# ReA4091_Rev4_2023-04-22_SCH.net
KiCad netlist of a schematic drawn in EasyEDA
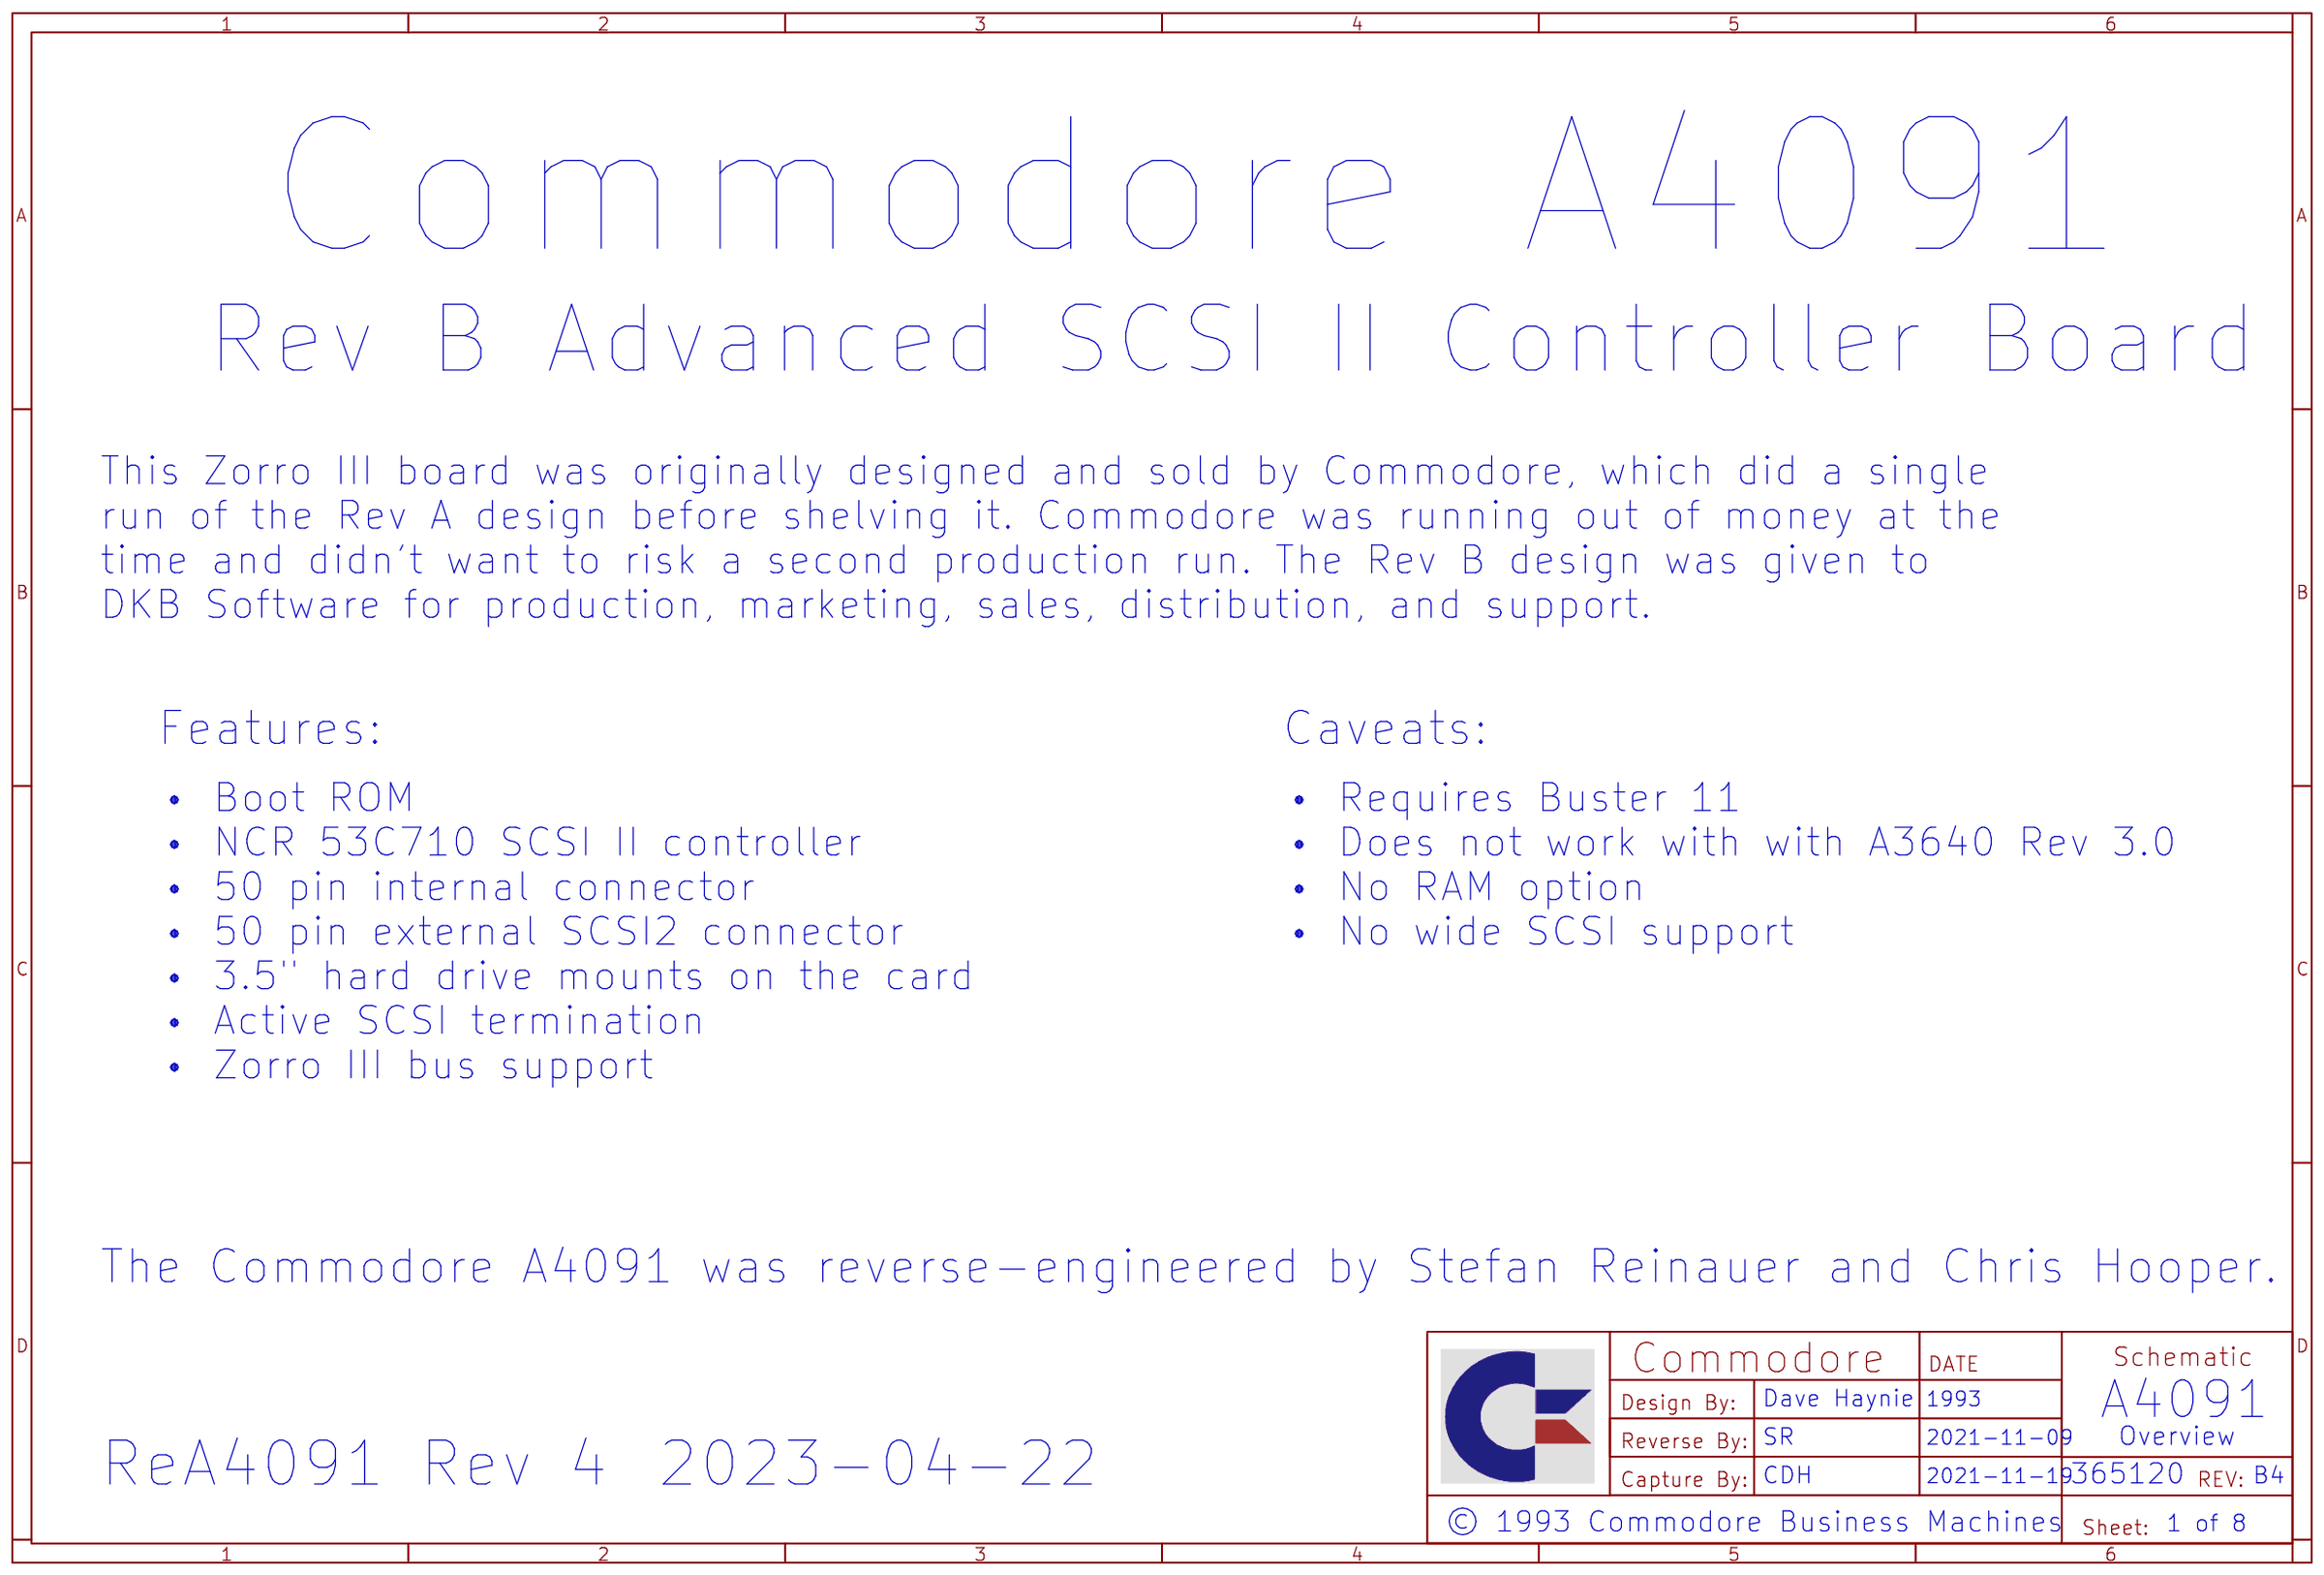
[diagram p0: Overview]
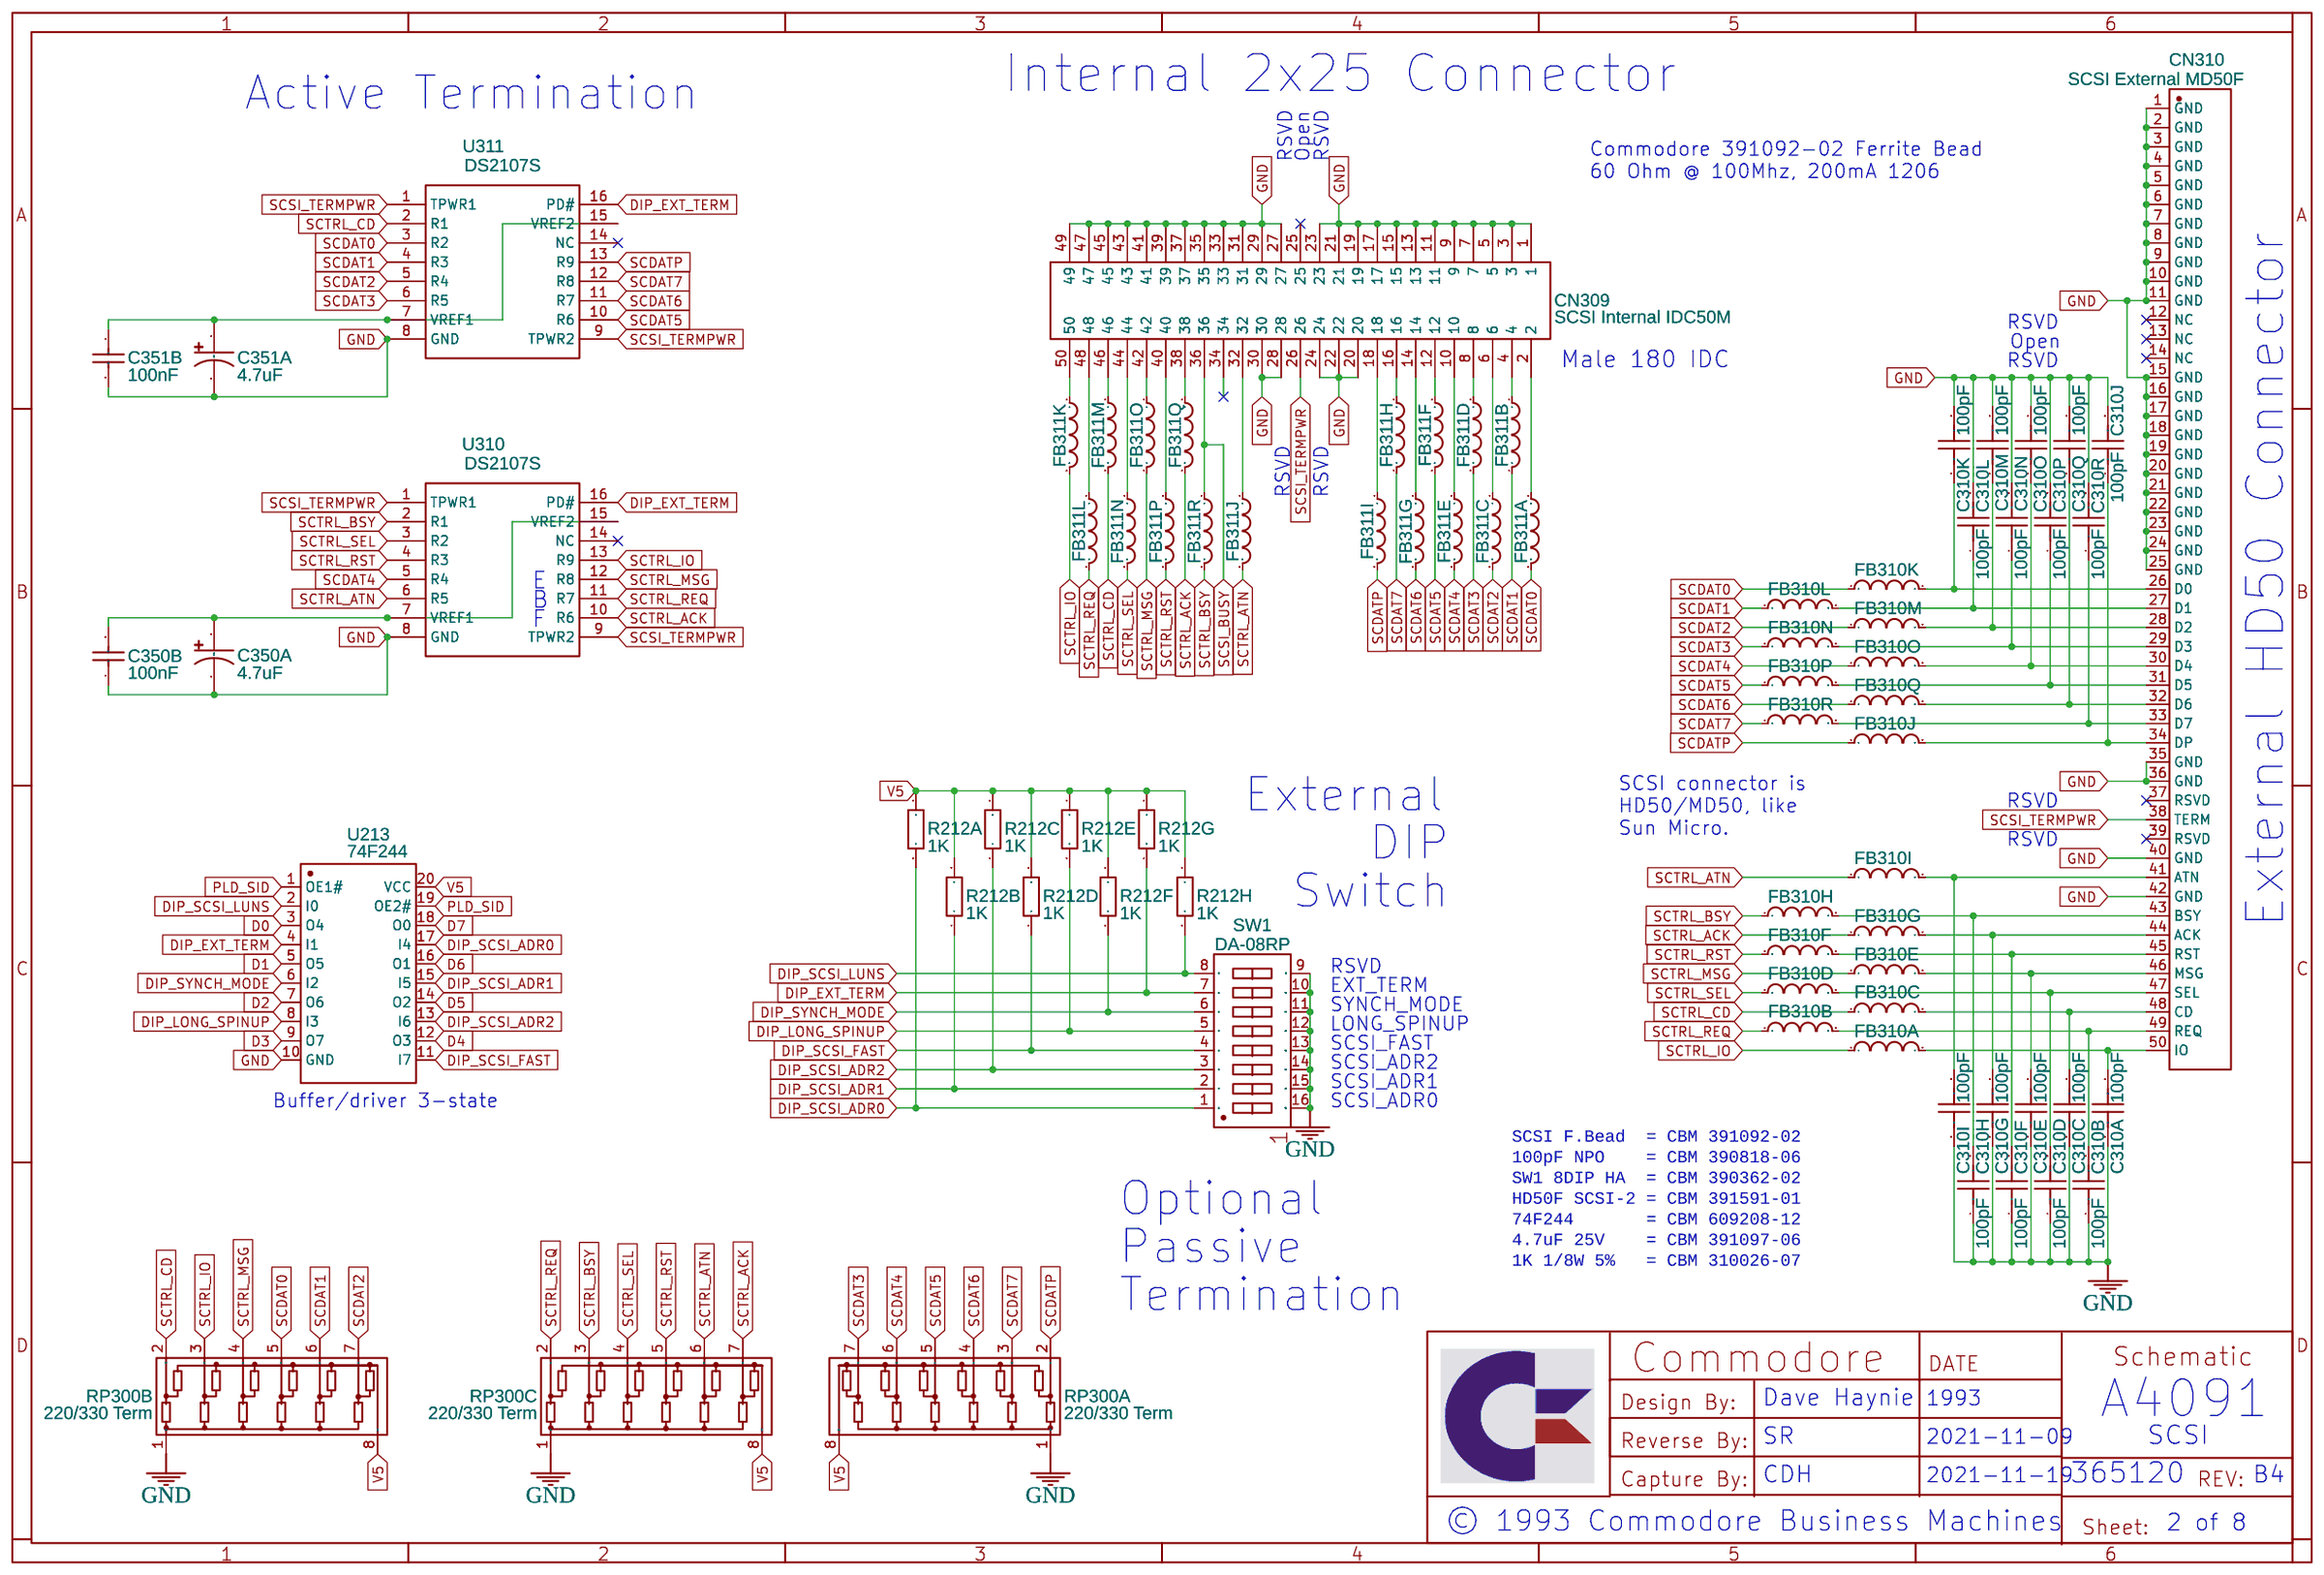
[diagram p1: SCSI]
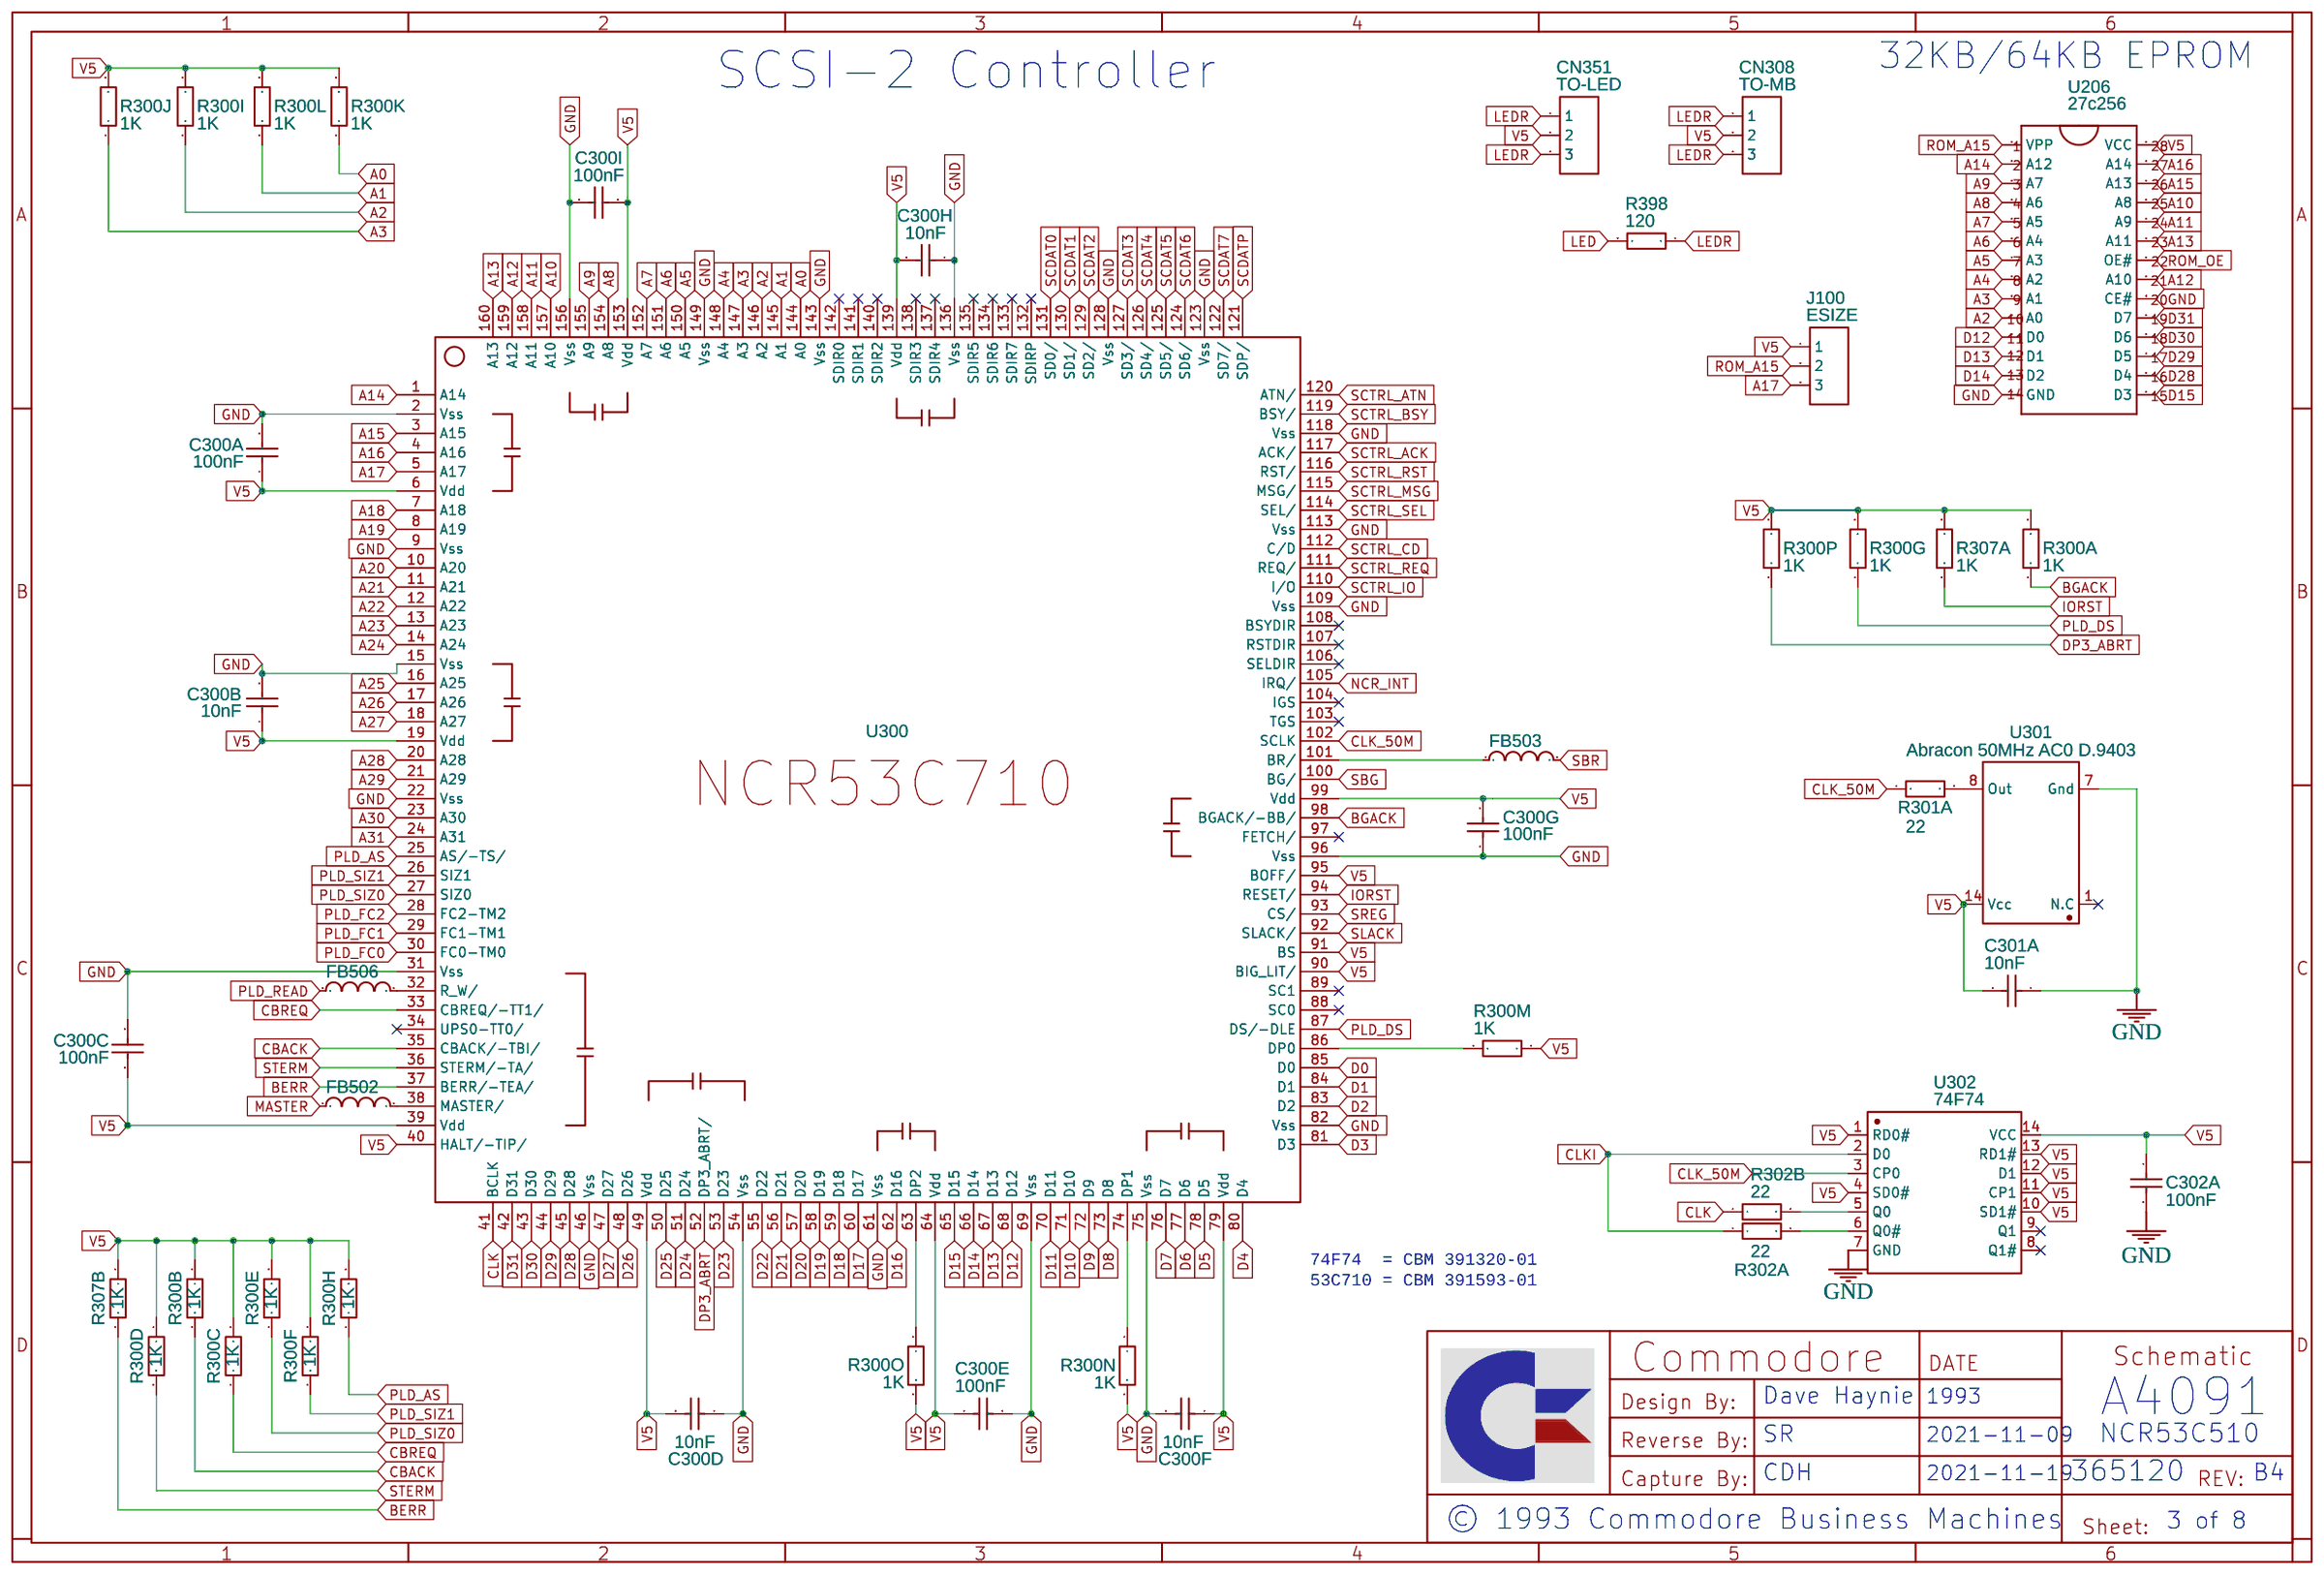
[diagram p2: NCR53C710]
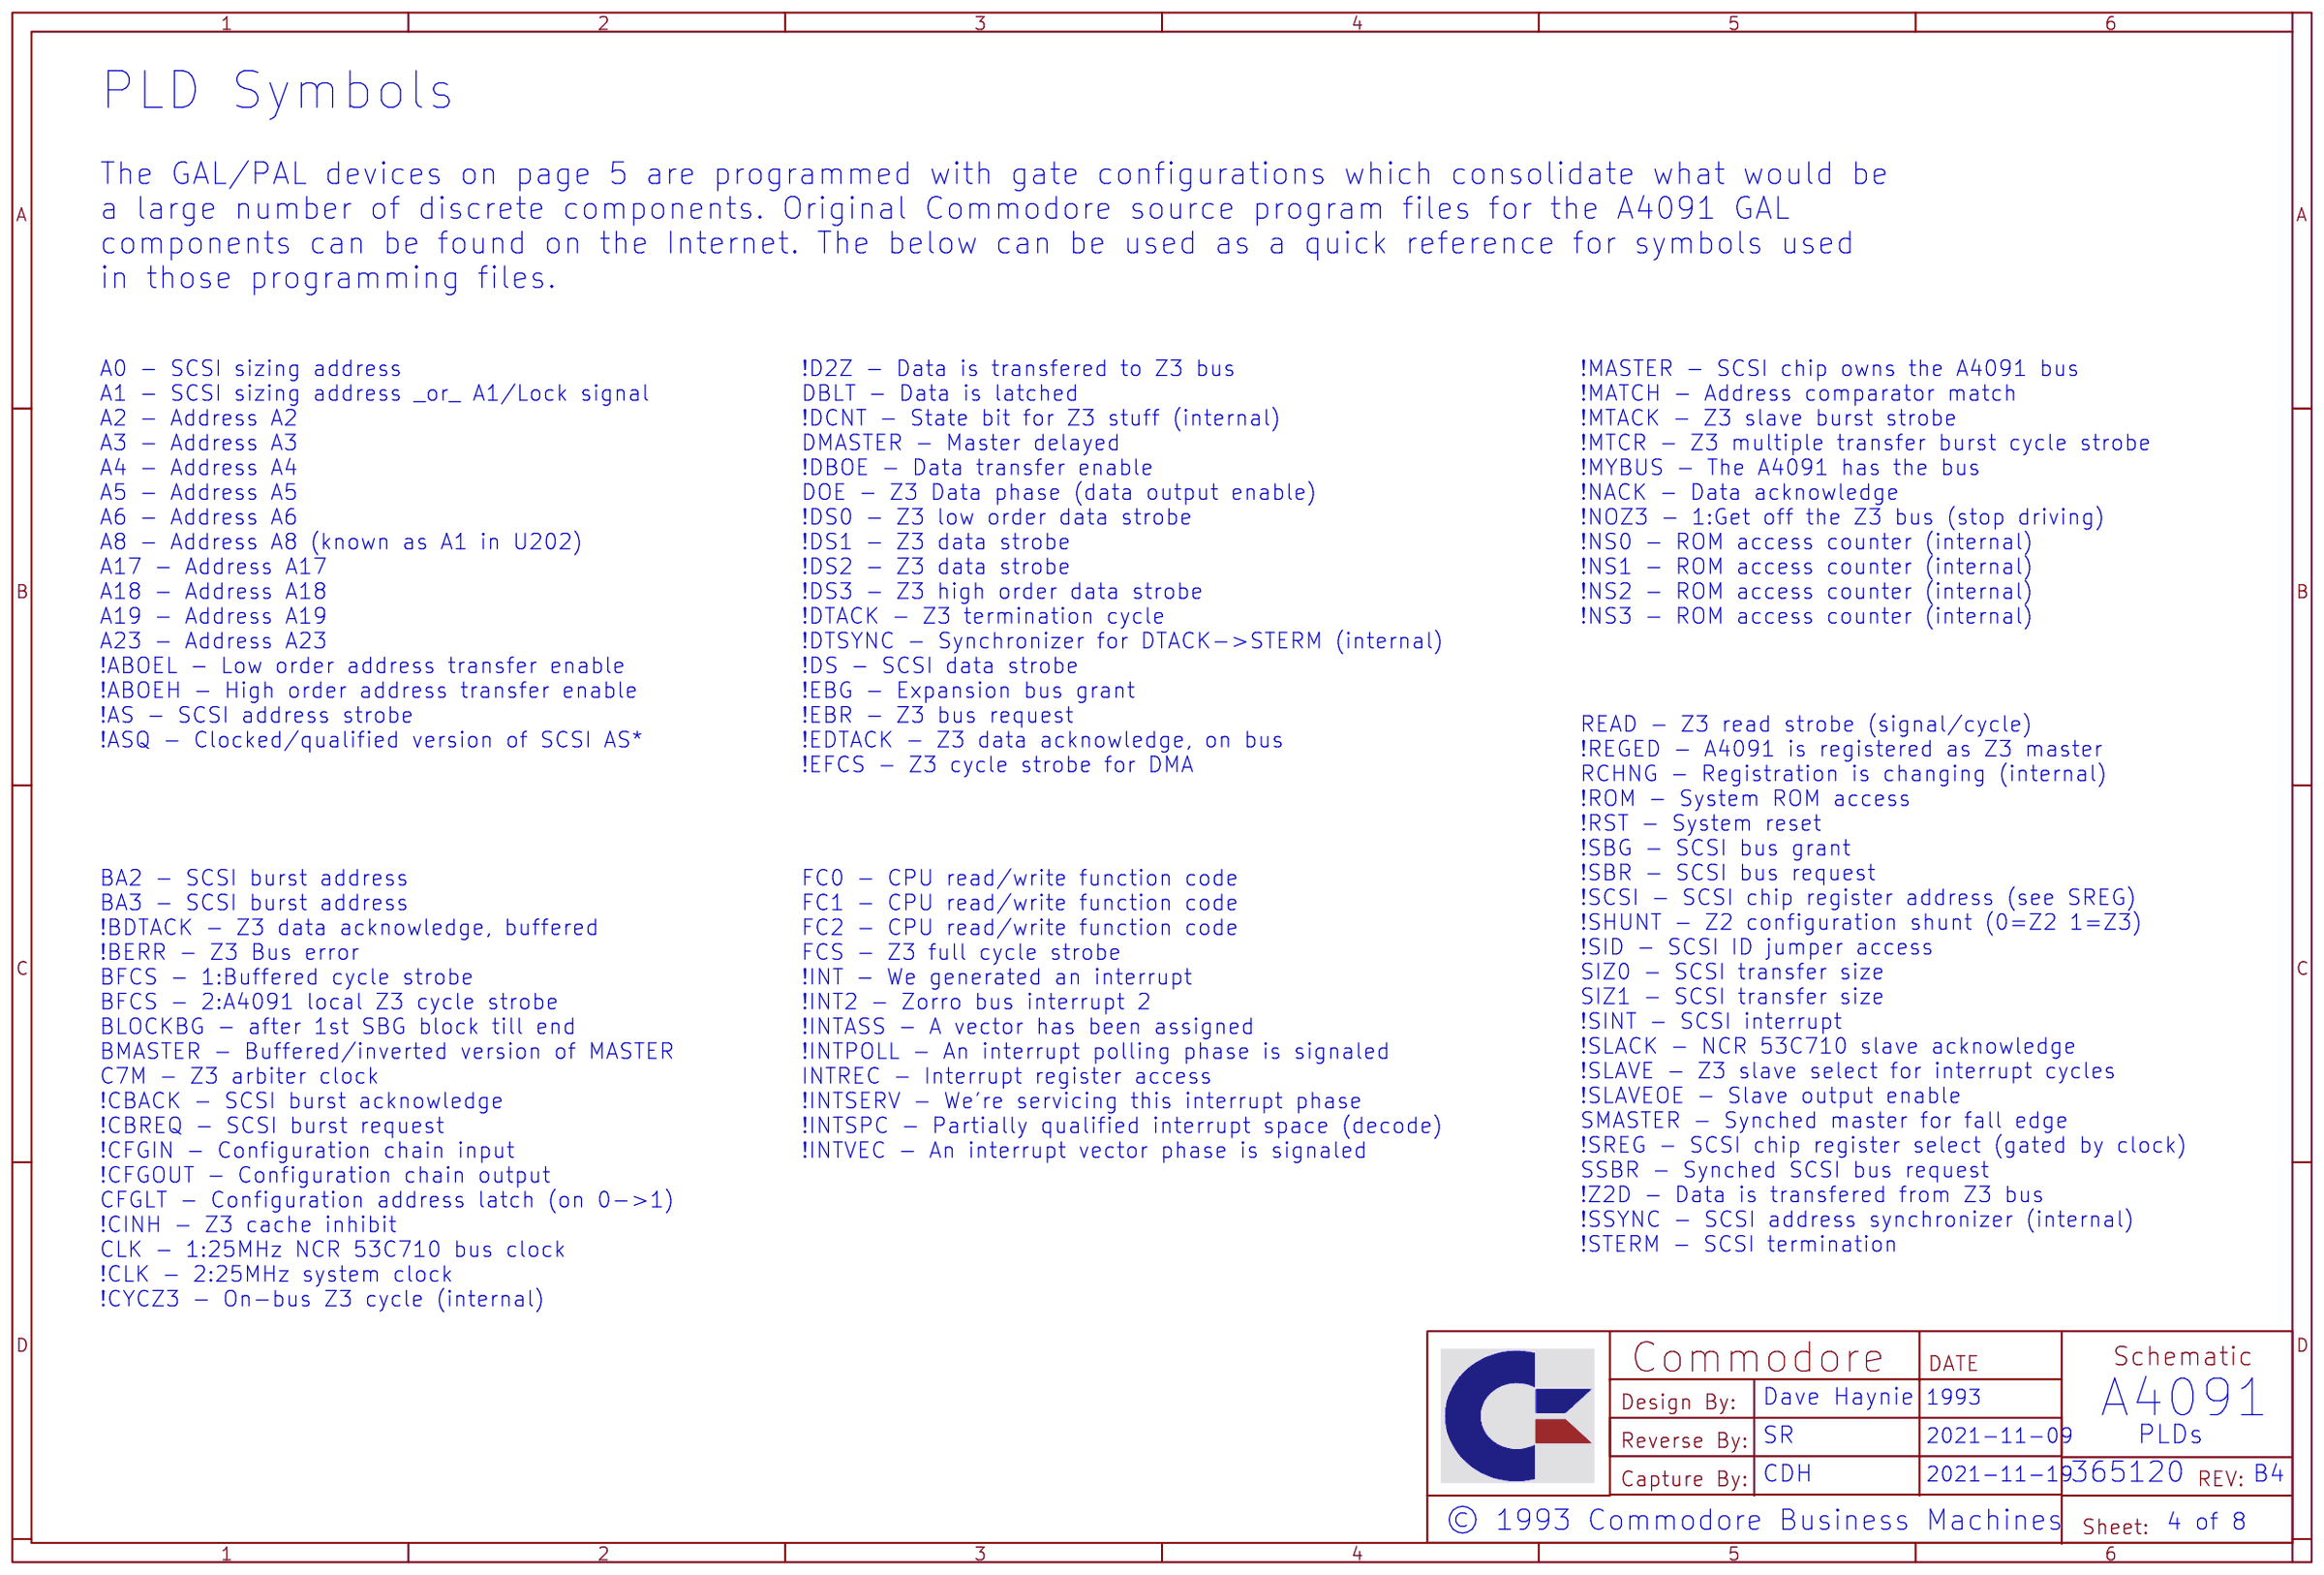
[diagram p3: PLD Symbols]
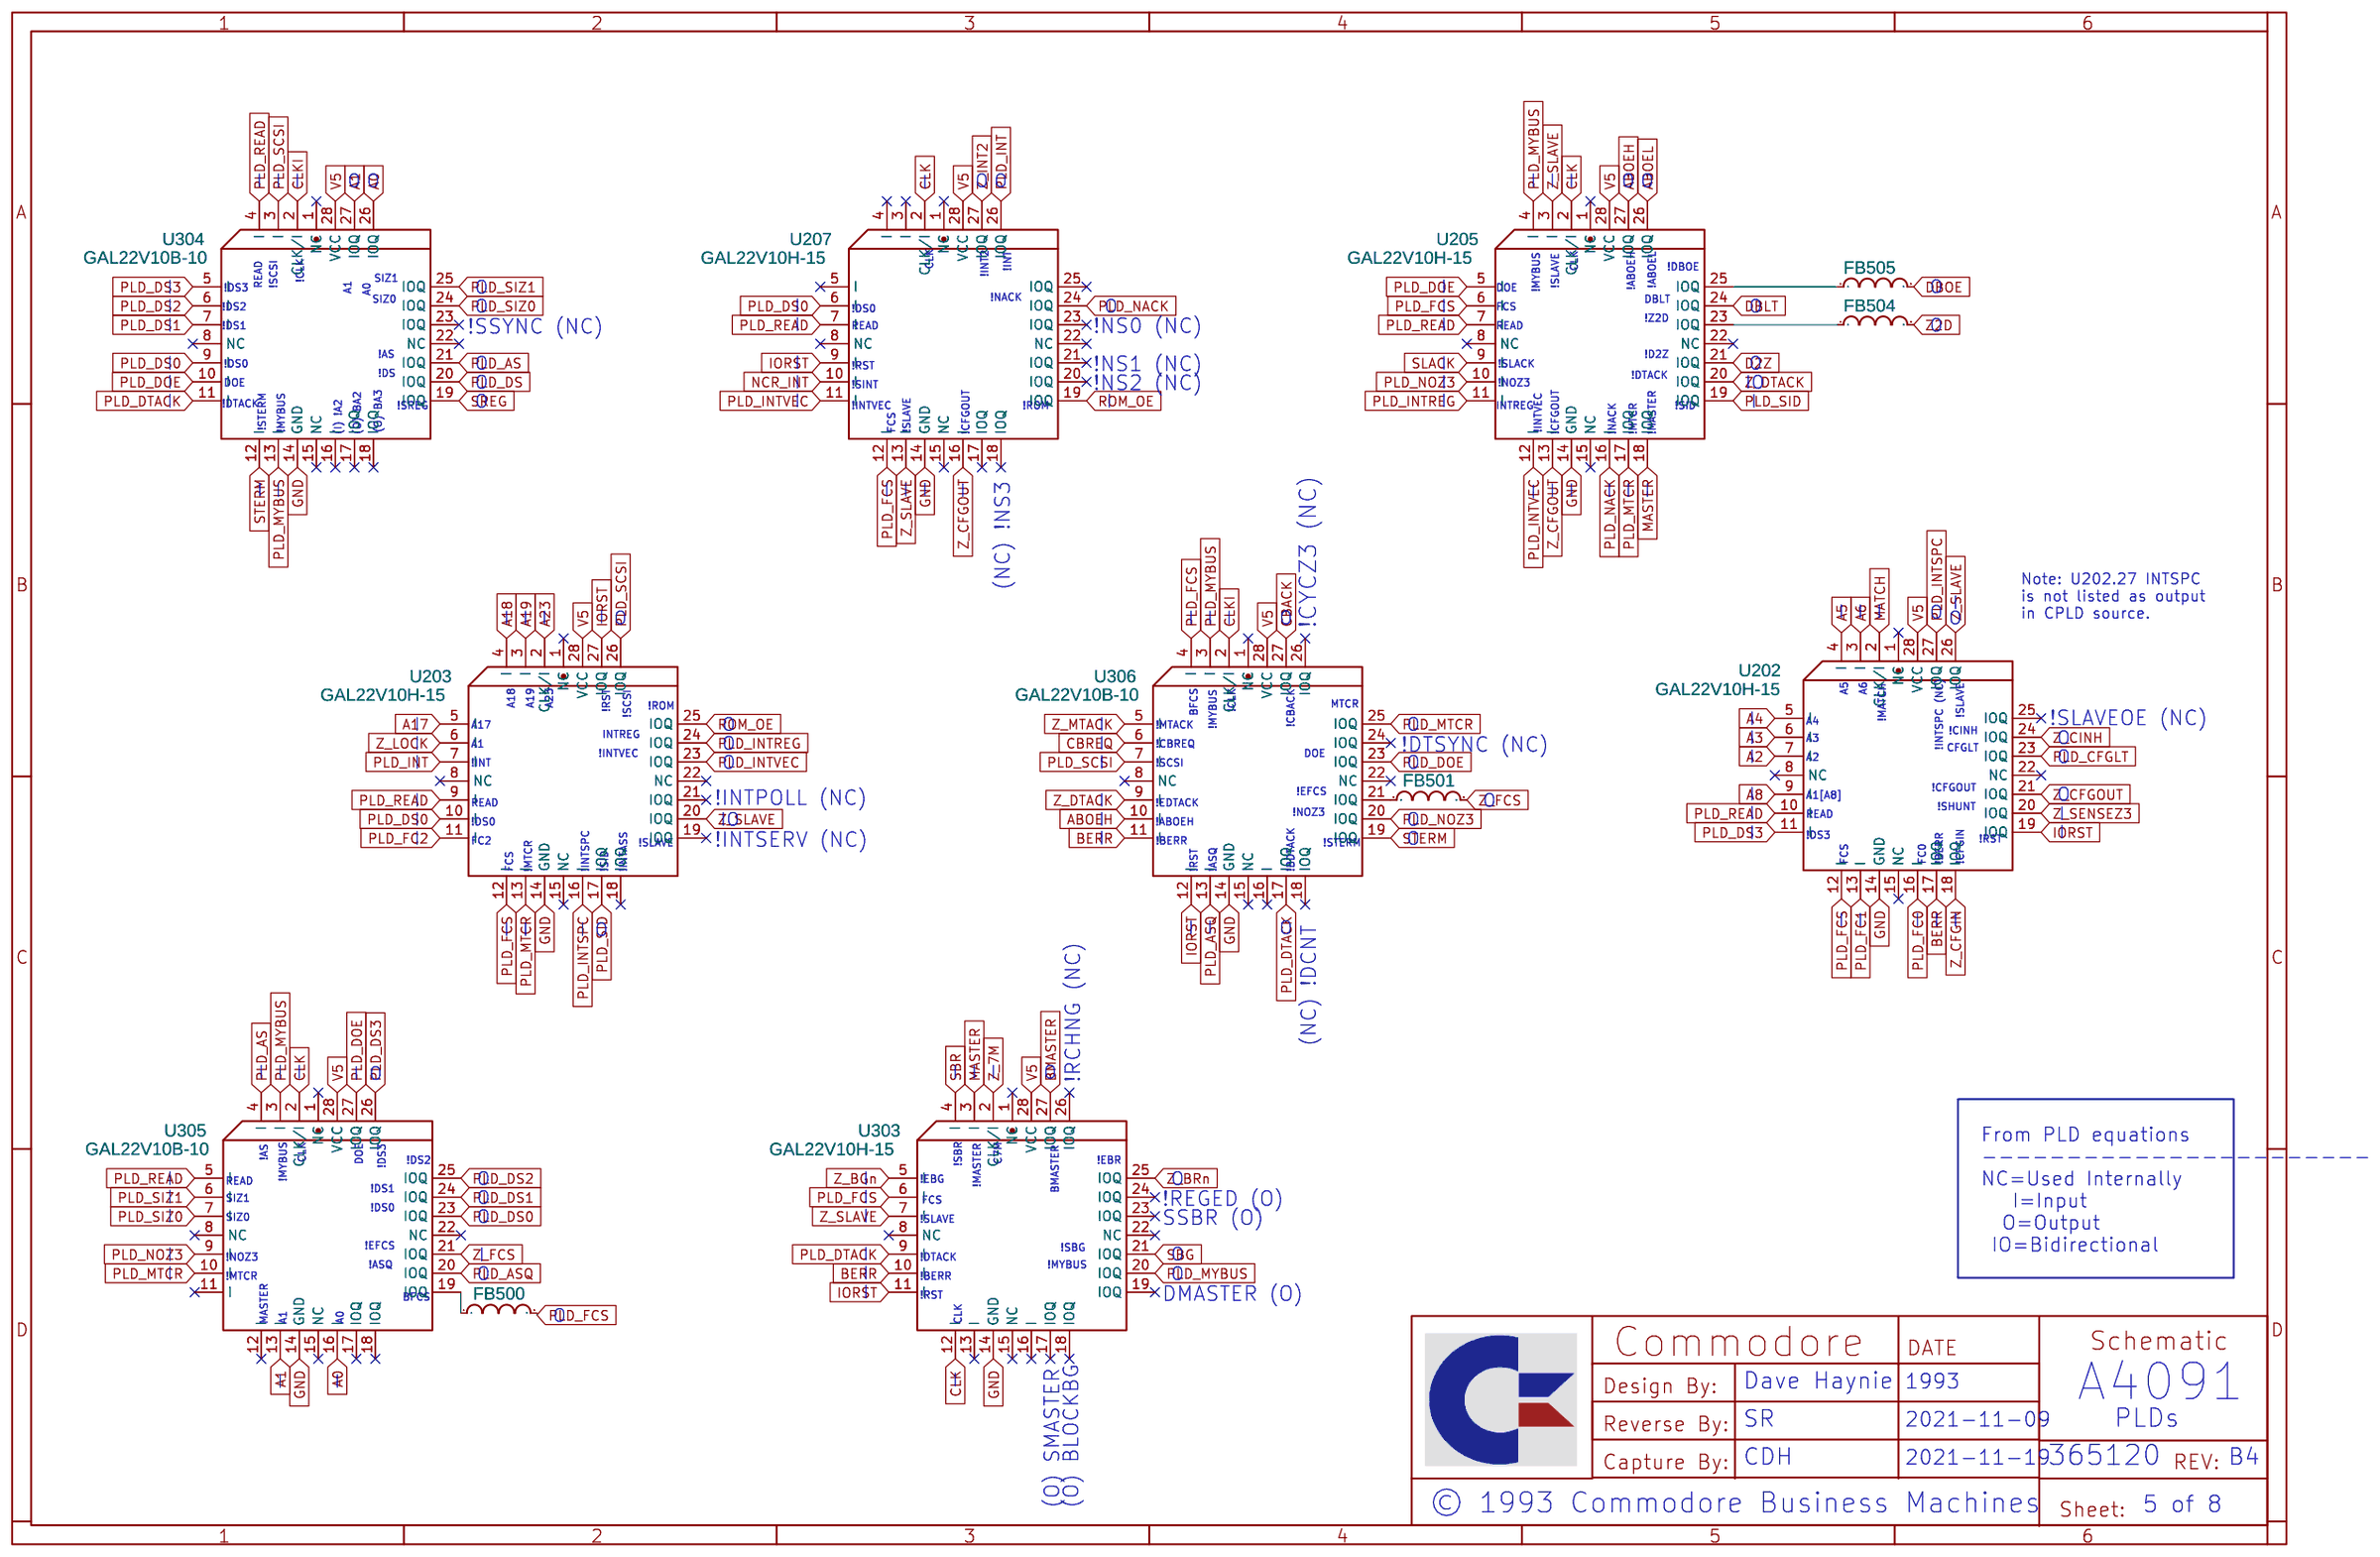
[diagram p4: PLDs]
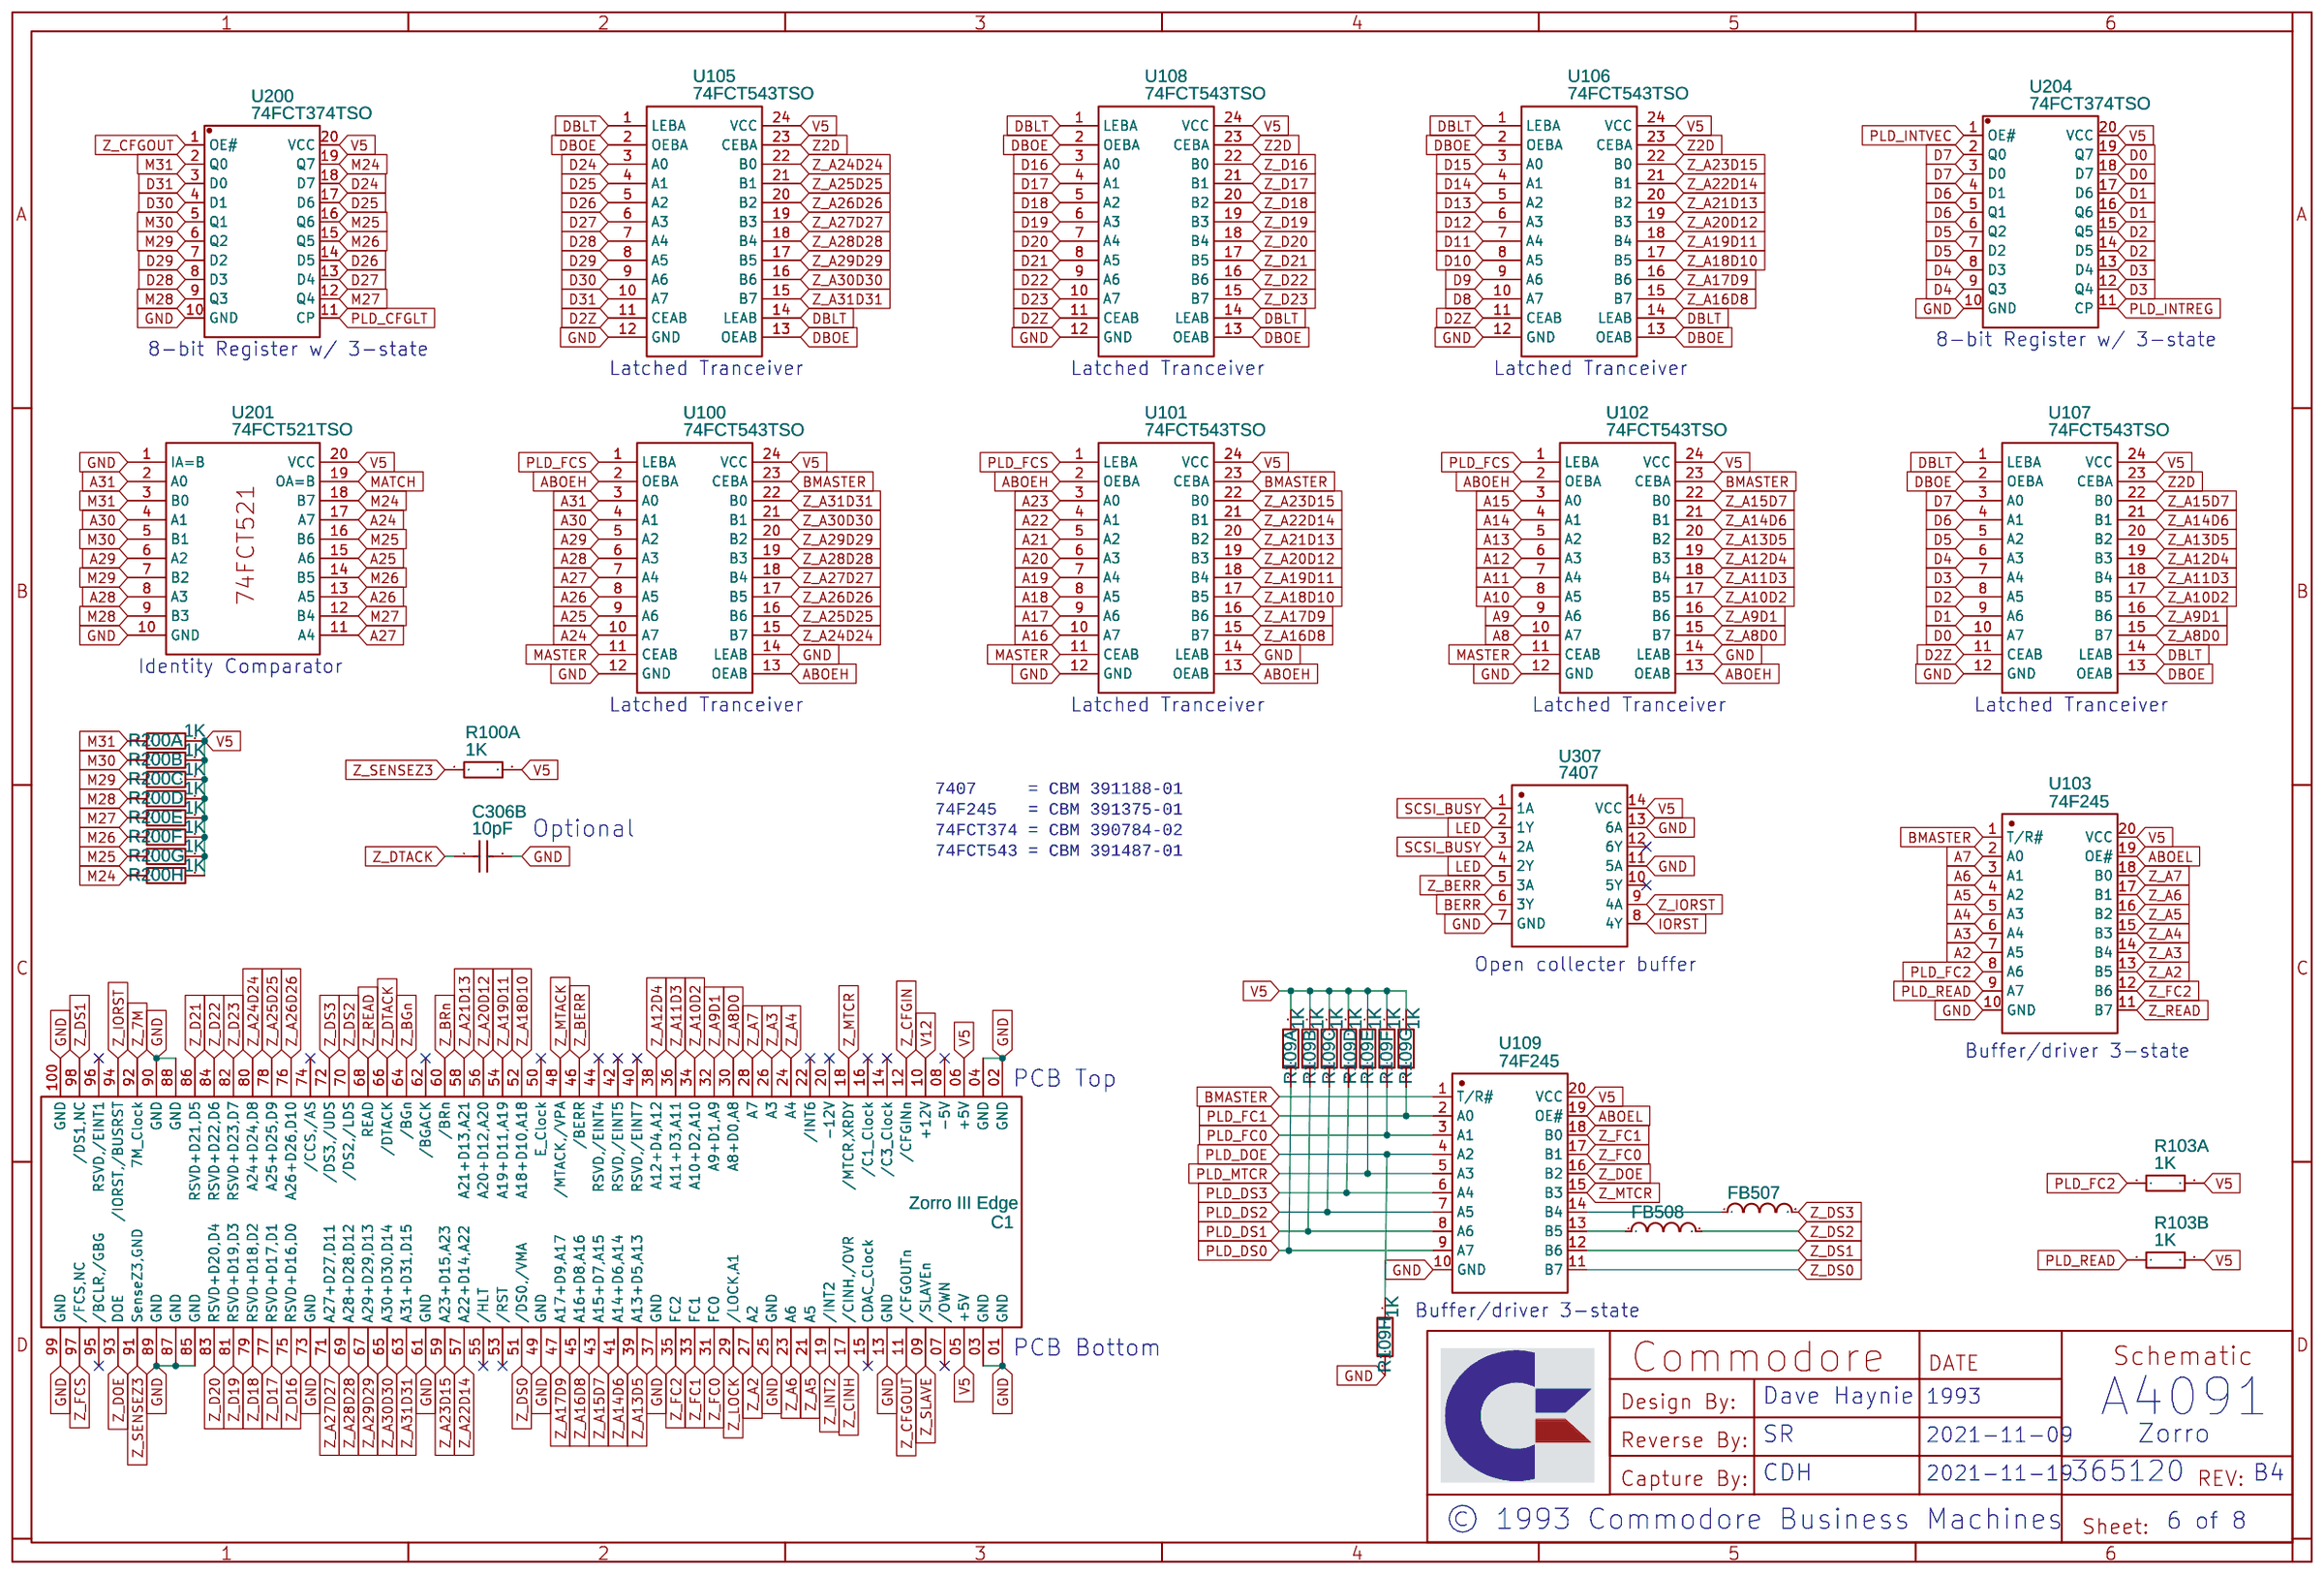
[diagram p5: Zorro]
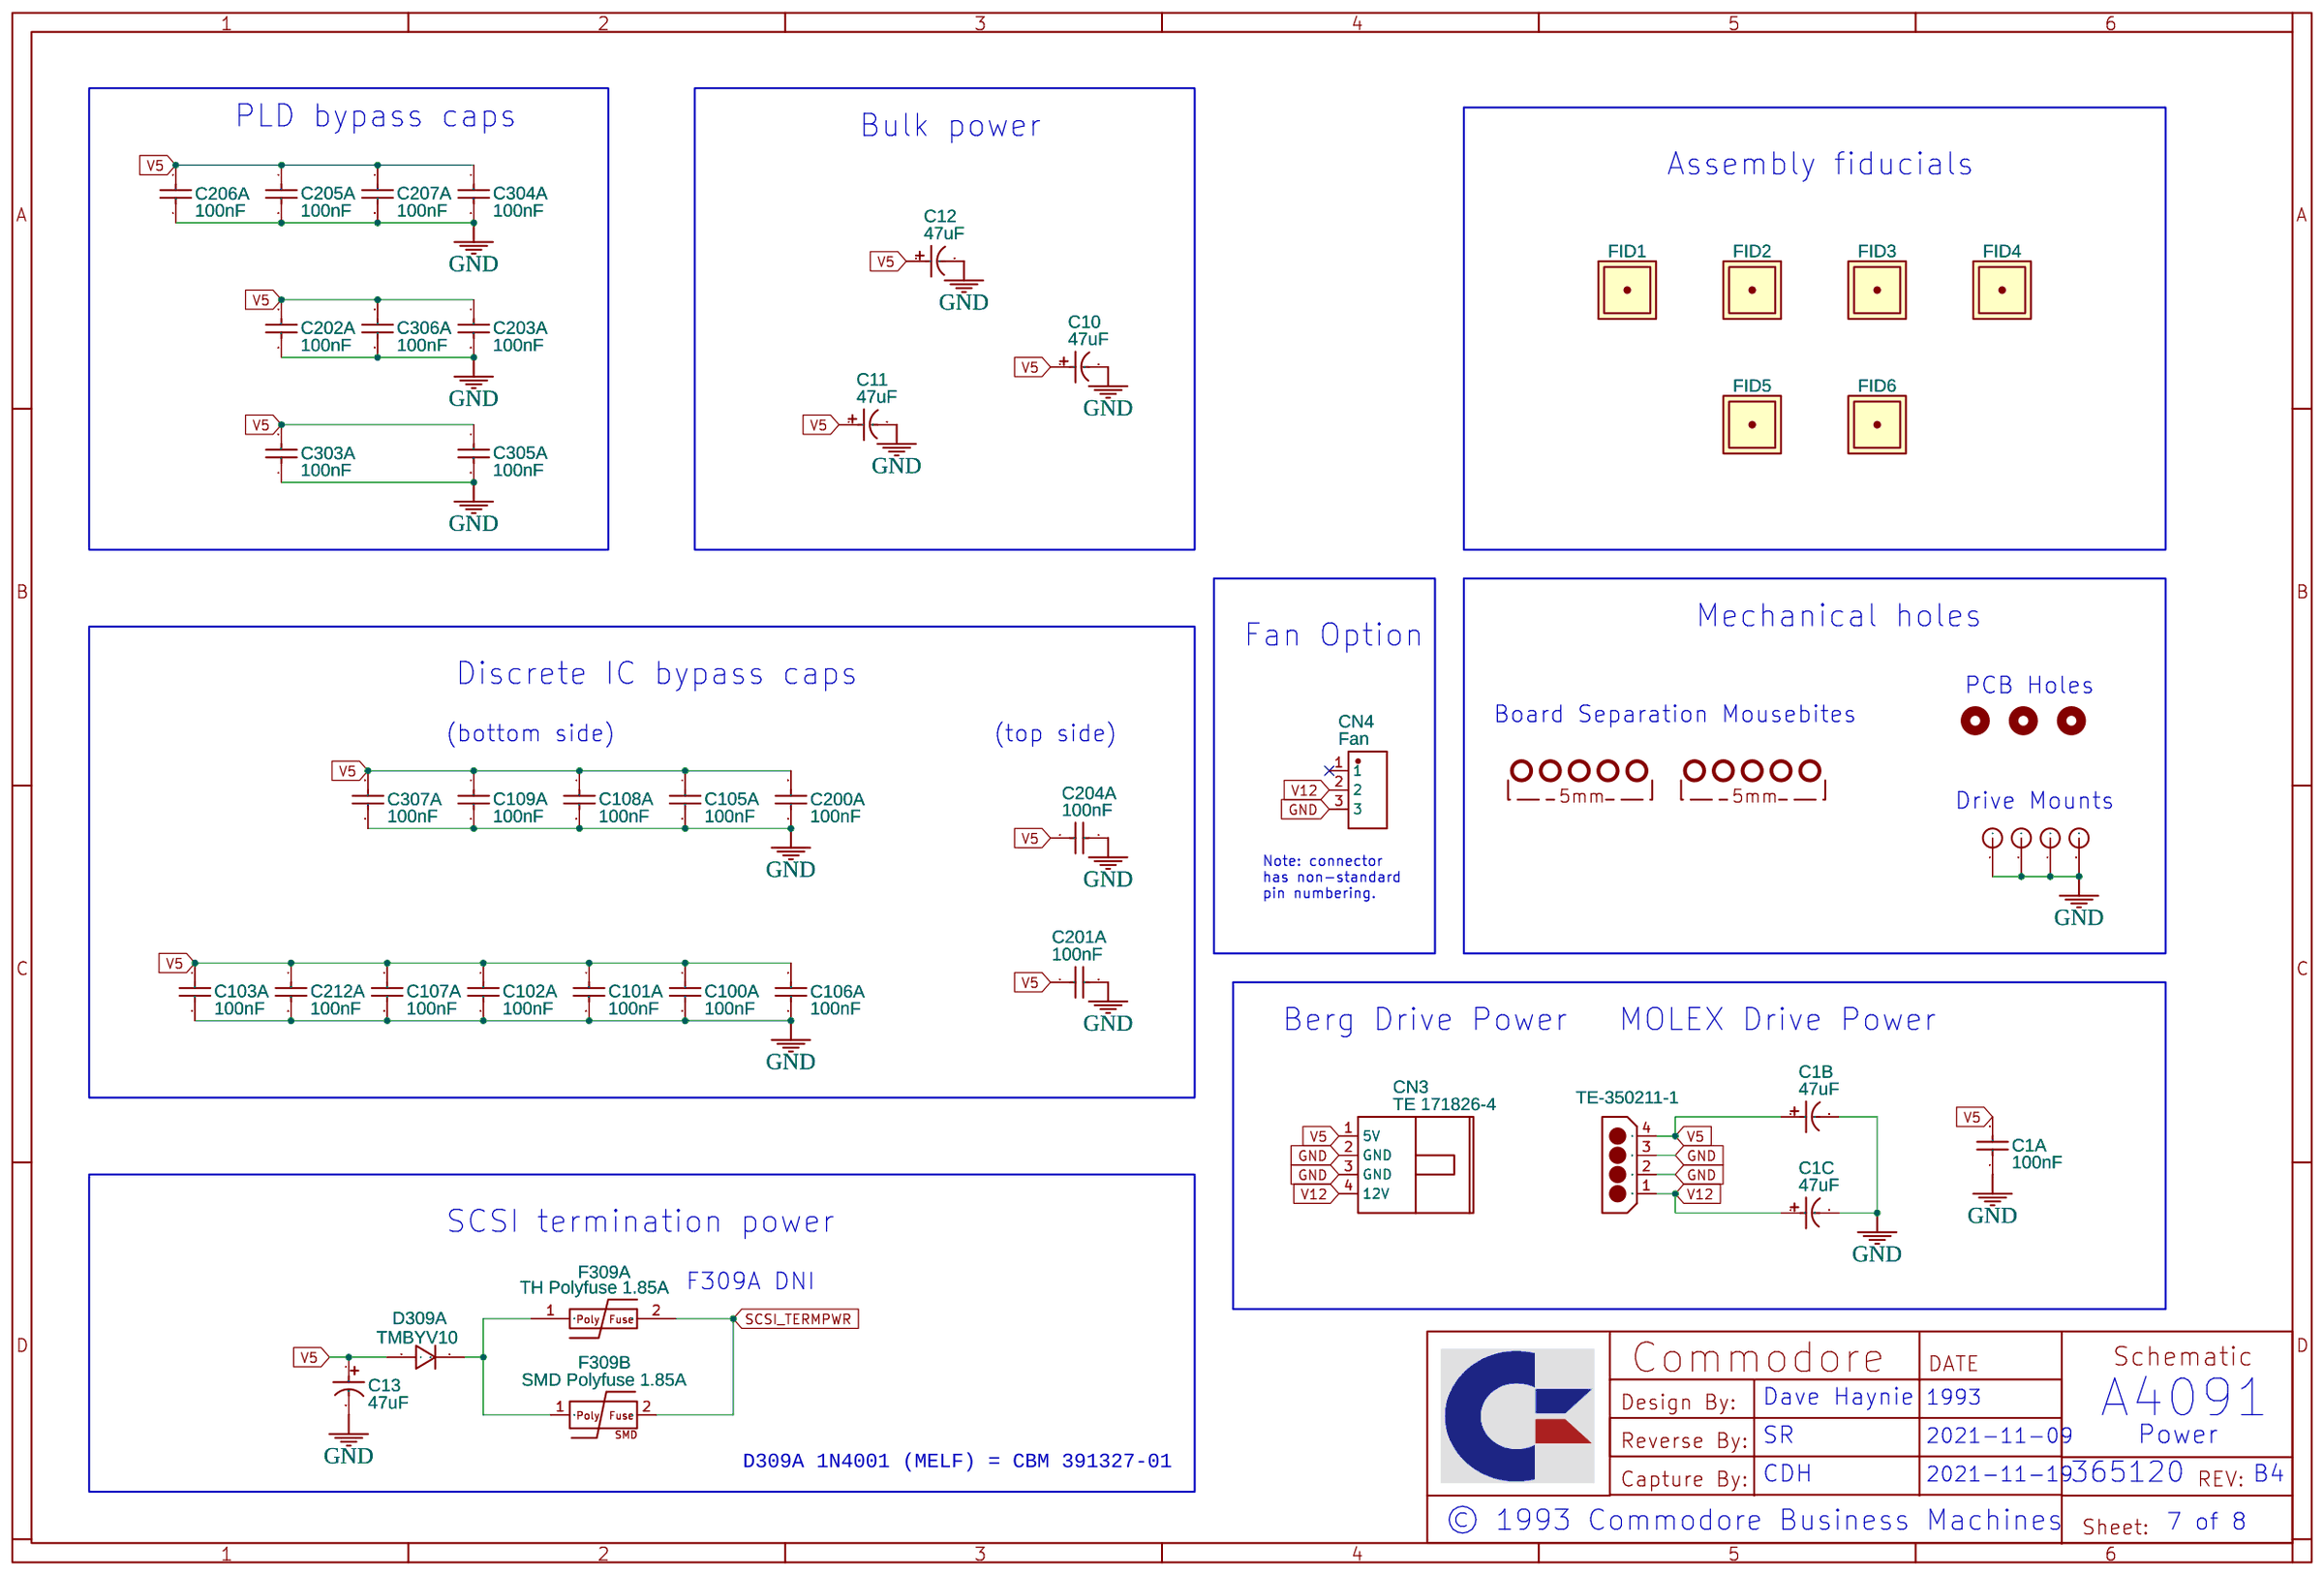
[diagram p6: Power]
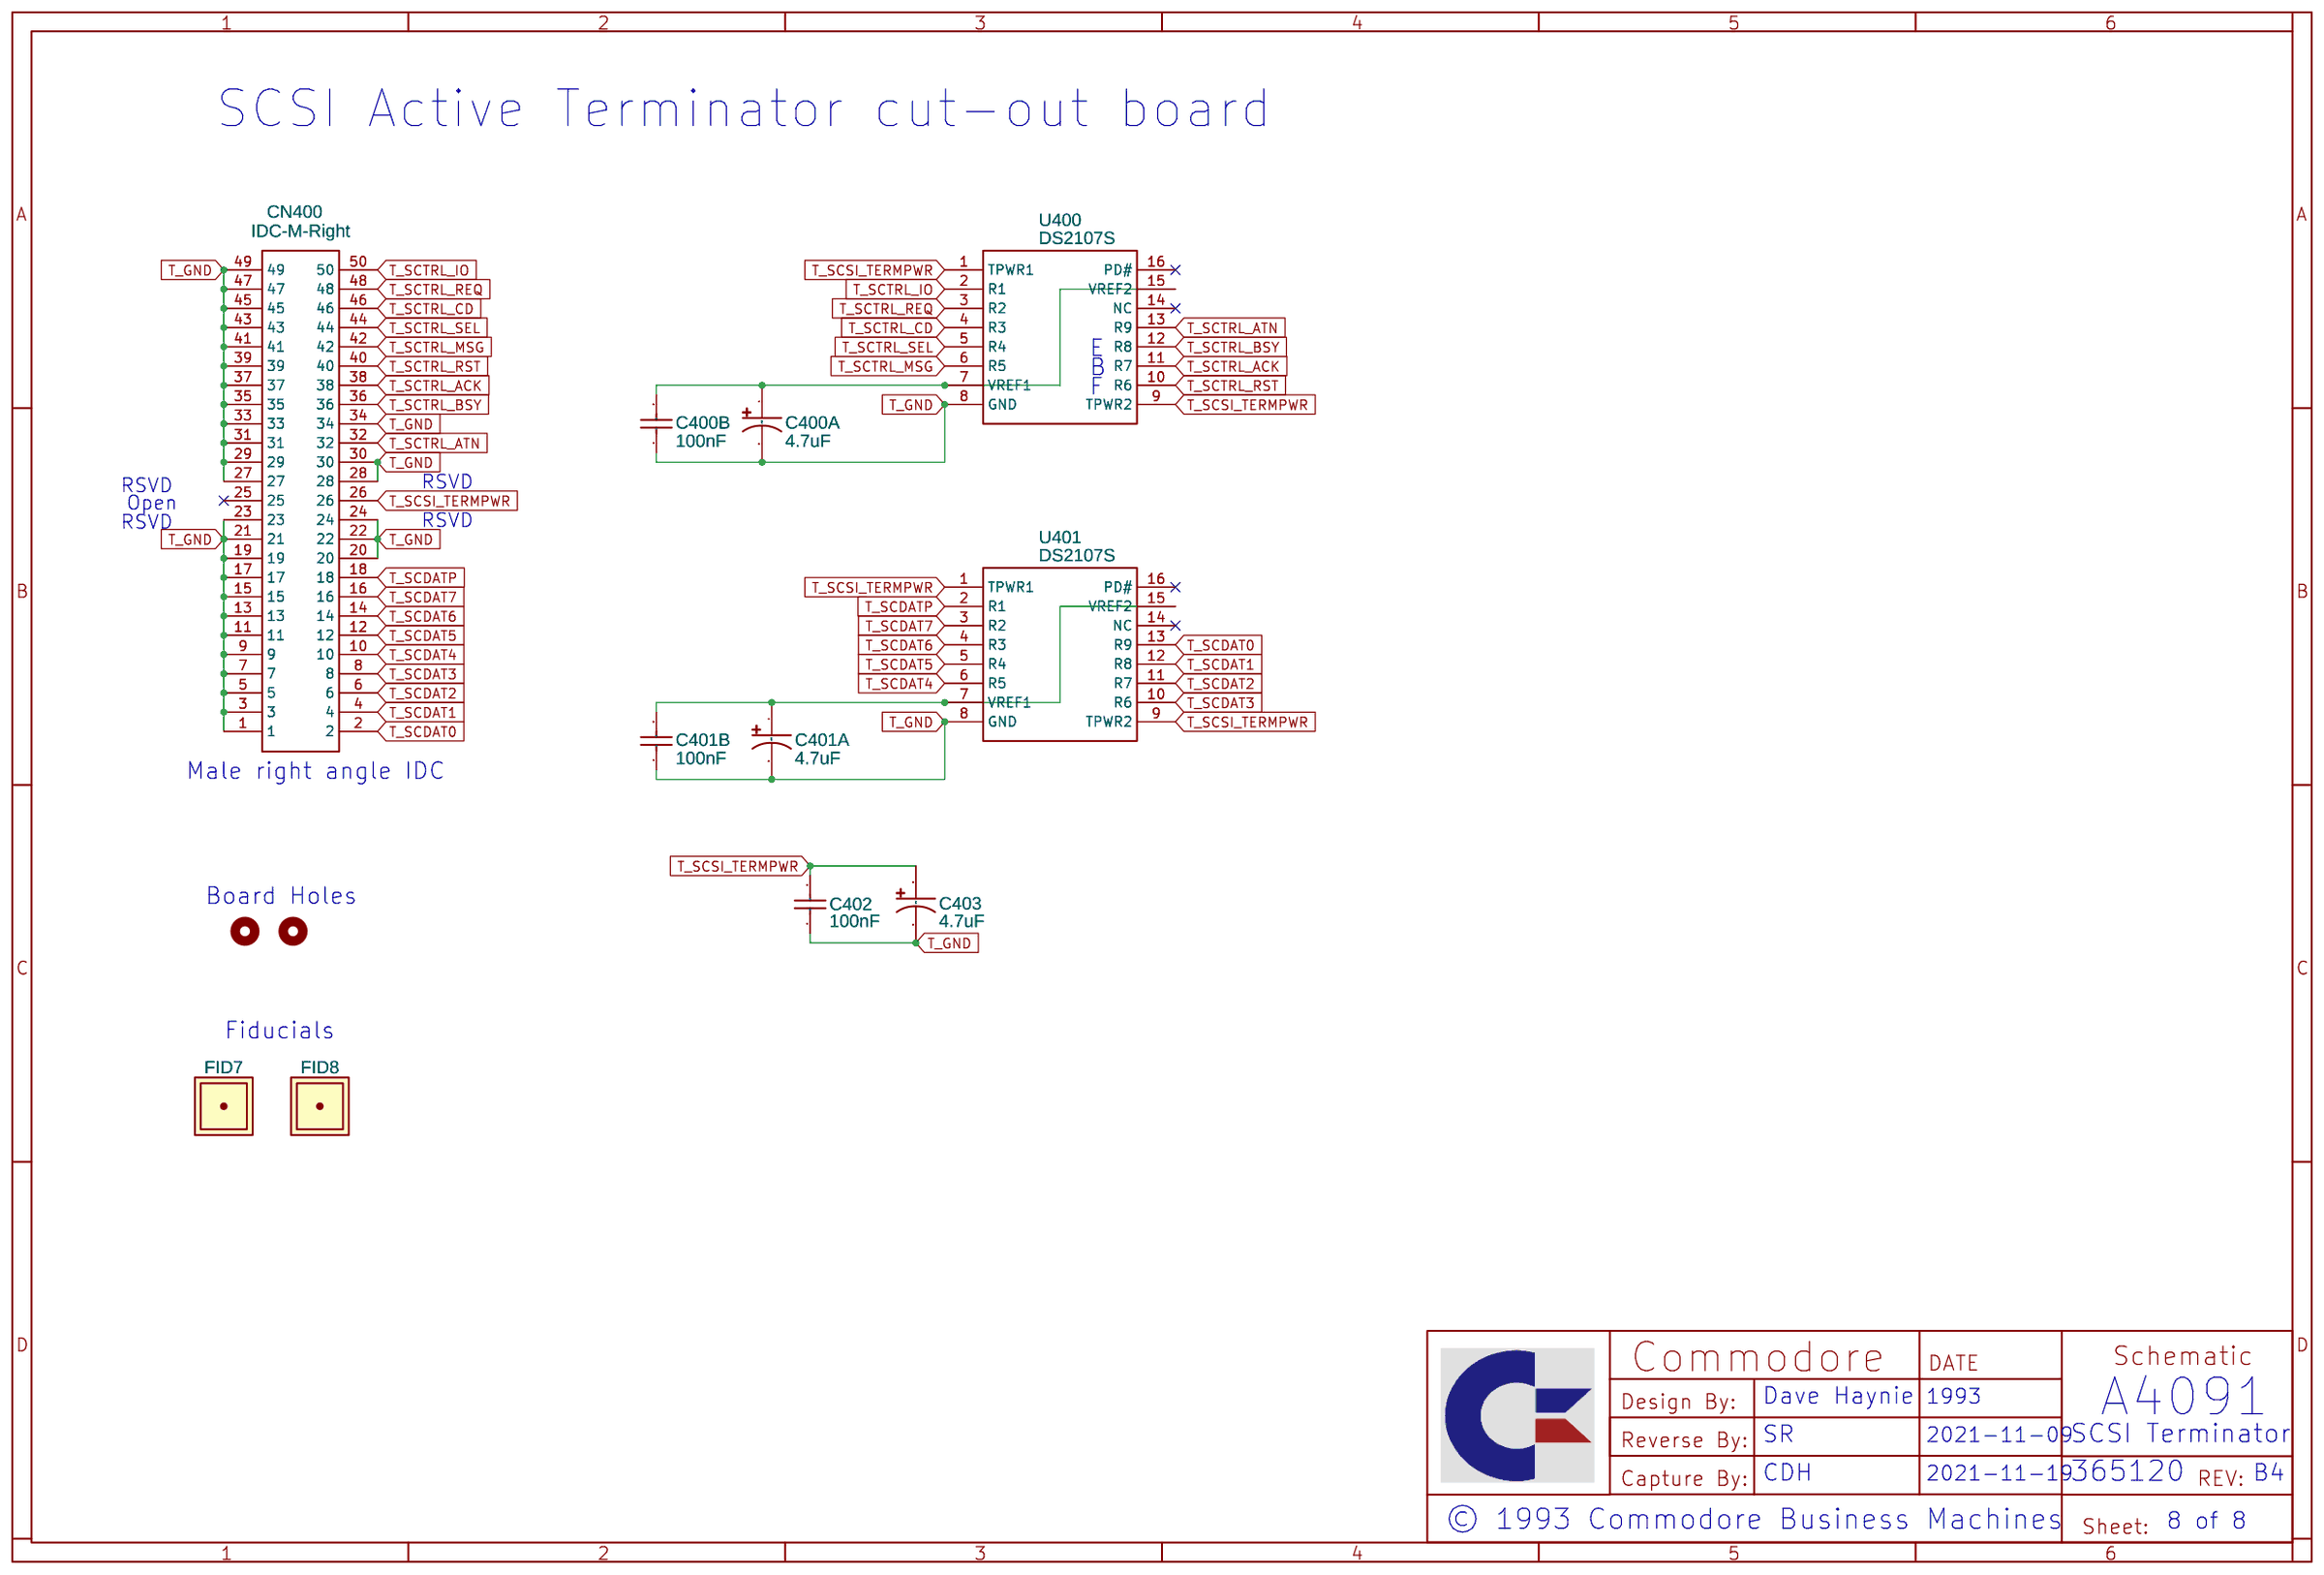
[diagram p7: SCSI Term]

(export (version "E")
  (design (tool "Eeschema 10.0.6"))
  (components
    (comp (ref "C310A")
      (value "100pF")
      (fields
        (field (name "BOM_Manufacturer Part") "TCC1206COG101J102ET")
        (field (name "BOM_Supplier Part") "C377018")
      )
      (libsource (lib "") (part "CL31C101JHFNNNE_17"))
    )
    (comp (ref "C310B")
      (value "100pF")
      (fields
        (field (name "BOM_Manufacturer Part") "TCC1206COG101J102ET")
        (field (name "BOM_Supplier Part") "C377018")
      )
      (libsource (lib "") (part "CL31C101JHFNNNE_9"))
    )
    (comp (ref "C310C")
      (value "100pF")
      (fields
        (field (name "BOM_Manufacturer Part") "TCC1206COG101J102ET")
        (field (name "BOM_Supplier Part") "C377018")
      )
      (libsource (lib "") (part "CL31C101JHFNNNE_15"))
    )
    (comp (ref "C310D")
      (value "100pF")
      (fields
        (field (name "BOM_Manufacturer Part") "TCC1206COG101J102ET")
        (field (name "BOM_Supplier Part") "C377018")
      )
      (libsource (lib "") (part "CL31C101JHFNNNE"))
    )
    (comp (ref "C310E")
      (value "100pF")
      (fields
        (field (name "BOM_Manufacturer Part") "TCC1206COG101J102ET")
        (field (name "BOM_Supplier Part") "C377018")
      )
      (libsource (lib "") (part "CL31C101JHFNNNE_8"))
    )
    (comp (ref "C310F")
      (value "100pF")
      (fields
        (field (name "BOM_Manufacturer Part") "TCC1206COG101J102ET")
        (field (name "BOM_Supplier Part") "C377018")
      )
      (libsource (lib "") (part "CL31C101JHFNNNE_5"))
    )
    (comp (ref "C310G")
      (value "100pF")
      (fields
        (field (name "BOM_Manufacturer Part") "TCC1206COG101J102ET")
        (field (name "BOM_Supplier Part") "C377018")
      )
      (libsource (lib "") (part "CL31C101JHFNNNE_1"))
    )
    (comp (ref "C310H")
      (value "100pF")
      (fields
        (field (name "BOM_Manufacturer Part") "TCC1206COG101J102ET")
        (field (name "BOM_Supplier Part") "C377018")
      )
      (libsource (lib "") (part "CL31C101JHFNNNE_16"))
    )
    (comp (ref "C310I")
      (value "100pF")
      (fields
        (field (name "BOM_Manufacturer Part") "TCC1206COG101J102ET")
        (field (name "BOM_Supplier Part") "C377018")
      )
      (libsource (lib "") (part "CL31C101JHFNNNE_6"))
    )
    (comp (ref "C310J")
      (value "100pF")
      (fields
        (field (name "BOM_Manufacturer Part") "TCC1206COG101J102ET")
        (field (name "BOM_Supplier Part") "C377018")
      )
      (libsource (lib "") (part "CL31C101JHFNNNE_3"))
    )
    (comp (ref "C310K")
      (value "100pF")
      (fields
        (field (name "BOM_Manufacturer Part") "TCC1206COG101J102ET")
        (field (name "BOM_Supplier Part") "C377018")
      )
      (libsource (lib "") (part "CL31C101JHFNNNE_12"))
    )
    (comp (ref "C310L")
      (value "100pF")
      (fields
        (field (name "BOM_Manufacturer Part") "TCC1206COG101J102ET")
        (field (name "BOM_Supplier Part") "C377018")
      )
      (libsource (lib "") (part "CL31C101JHFNNNE_13"))
    )
    (comp (ref "C310M")
      (value "100pF")
      (fields
        (field (name "BOM_Manufacturer Part") "TCC1206COG101J102ET")
        (field (name "BOM_Supplier Part") "C377018")
      )
      (libsource (lib "") (part "CL31C101JHFNNNE_14"))
    )
    (comp (ref "C310N")
      (value "100pF")
      (fields
        (field (name "BOM_Manufacturer Part") "TCC1206COG101J102ET")
        (field (name "BOM_Supplier Part") "C377018")
      )
      (libsource (lib "") (part "CL31C101JHFNNNE_4"))
    )
    (comp (ref "C310O")
      (value "100pF")
      (fields
        (field (name "BOM_Manufacturer Part") "TCC1206COG101J102ET")
        (field (name "BOM_Supplier Part") "C377018")
      )
      (libsource (lib "") (part "CL31C101JHFNNNE_2"))
    )
    (comp (ref "C310P")
      (value "100pF")
      (fields
        (field (name "BOM_Manufacturer Part") "TCC1206COG101J102ET")
        (field (name "BOM_Supplier Part") "C377018")
      )
      (libsource (lib "") (part "CL31C101JHFNNNE_10"))
    )
    (comp (ref "C310Q")
      (value "100pF")
      (fields
        (field (name "BOM_Manufacturer Part") "TCC1206COG101J102ET")
        (field (name "BOM_Supplier Part") "C377018")
      )
      (libsource (lib "") (part "CL31C101JHFNNNE_7"))
    )
    (comp (ref "C310R")
      (value "100pF")
      (fields
        (field (name "BOM_Manufacturer Part") "TCC1206COG101J102ET")
        (field (name "BOM_Supplier Part") "C377018")
      )
      (libsource (lib "") (part "CL31C101JHFNNNE_11"))
    )
    (comp (ref "C350A")
      (value "4.7uF")
      (fields
        (field (name "BOM_Manufacturer Part") "UWX1E4R7MCL1GB")
        (field (name "BOM_Supplier Part") "C445042")
      )
      (libsource (lib "") (part "VZH4R7M1HTR-0406_1"))
    )
    (comp (ref "C350B")
      (value "100nF")
      (fields
        (field (name "BOM_Manufacturer Part") "CL31B104KBCNNNC")
        (field (name "BOM_Supplier Part") "C24497")
      )
      (libsource (lib "") (part "CL31B104KBCNNNC"))
    )
    (comp (ref "C351A")
      (value "4.7uF")
      (fields
        (field (name "BOM_Manufacturer Part") "UWX1E4R7MCL1GB")
        (field (name "BOM_Supplier Part") "C445042")
      )
      (libsource (lib "") (part "VZH4R7M1HTR-0406"))
    )
    (comp (ref "C351B")
      (value "100nF")
      (fields
        (field (name "BOM_Manufacturer Part") "CL31B104KBCNNNC")
        (field (name "BOM_Supplier Part") "C24497")
      )
      (libsource (lib "") (part "CL31B104KBCNNNC_1"))
    )
    (comp (ref "CN309")
      (value "SCSI Internal IDC50M")
      (fields
        (field (name "BOM_Manufacturer Part") "B-3000S50P-0110")
        (field (name "BOM_Supplier Part") "C146633")
      )
      (libsource (lib "") (part "300S-50P"))
    )
    (comp (ref "CN310") (value "SCSI External MD50F") (libsource (lib "") (part "SCSI External MD50F")))
    (comp (ref "FB310A")
      (value "60Ω")
      (fields
        (field (name "BOM_Manufacturer Part") "CBG321609U600T")
        (field (name "BOM_Supplier Part") "C1020")
      )
      (libsource (lib "") (part "MLB3216-601(f)_20"))
    )
    (comp (ref "FB310B")
      (value "60Ω")
      (fields
        (field (name "BOM_Manufacturer Part") "CBG321609U600T")
        (field (name "BOM_Supplier Part") "C1020")
      )
      (libsource (lib "") (part "MLB3216-601(f)_21"))
    )
    (comp (ref "FB310C")
      (value "60Ω")
      (fields
        (field (name "BOM_Manufacturer Part") "CBG321609U600T")
        (field (name "BOM_Supplier Part") "C1020")
      )
      (libsource (lib "") (part "MLB3216-601(f)_25"))
    )
    (comp (ref "FB310D")
      (value "60Ω")
      (fields
        (field (name "BOM_Manufacturer Part") "CBG321609U600T")
        (field (name "BOM_Supplier Part") "C1020")
      )
      (libsource (lib "") (part "MLB3216-601(f)_18"))
    )
    (comp (ref "FB310E")
      (value "60Ω")
      (fields
        (field (name "BOM_Manufacturer Part") "CBG321609U600T")
        (field (name "BOM_Supplier Part") "C1020")
      )
      (libsource (lib "") (part "MLB3216-601(f)_6"))
    )
    (comp (ref "FB310F")
      (value "60Ω")
      (fields
        (field (name "BOM_Manufacturer Part") "CBG321609U600T")
        (field (name "BOM_Supplier Part") "C1020")
      )
      (libsource (lib "") (part "MLB3216-601(f)_5"))
    )
    (comp (ref "FB310G")
      (value "60Ω")
      (fields
        (field (name "BOM_Manufacturer Part") "CBG321609U600T")
        (field (name "BOM_Supplier Part") "C1020")
      )
      (libsource (lib "") (part "MLB3216-601(f)_23"))
    )
    (comp (ref "FB310H")
      (value "60Ω")
      (fields
        (field (name "BOM_Manufacturer Part") "CBG321609U600T")
        (field (name "BOM_Supplier Part") "C1020")
      )
      (libsource (lib "") (part "MLB3216-601(f)_2"))
    )
    (comp (ref "FB310I")
      (value "60Ω")
      (fields
        (field (name "BOM_Manufacturer Part") "CBG321609U600T")
        (field (name "BOM_Supplier Part") "C1020")
      )
      (libsource (lib "") (part "MLB3216-601(f)_19"))
    )
    (comp (ref "FB310J")
      (value "60Ω")
      (fields
        (field (name "BOM_Manufacturer Part") "CBG321609U600T")
        (field (name "BOM_Supplier Part") "C1020")
      )
      (libsource (lib "") (part "MLB3216-601(f)_17"))
    )
    (comp (ref "FB310K")
      (value "60Ω")
      (fields
        (field (name "BOM_Manufacturer Part") "CBG321609U600T")
        (field (name "BOM_Supplier Part") "C1020")
      )
      (libsource (lib "") (part "MLB3216-601(f)_14"))
    )
    (comp (ref "FB310L")
      (value "60Ω")
      (fields
        (field (name "BOM_Manufacturer Part") "CBG321609U600T")
        (field (name "BOM_Supplier Part") "C1020")
      )
      (libsource (lib "") (part "MLB3216-601(f)_3"))
    )
    (comp (ref "FB310M")
      (value "60Ω")
      (fields
        (field (name "BOM_Manufacturer Part") "CBG321609U600T")
        (field (name "BOM_Supplier Part") "C1020")
      )
      (libsource (lib "") (part "MLB3216-601(f)_26"))
    )
    (comp (ref "FB310N")
      (value "60Ω")
      (fields
        (field (name "BOM_Manufacturer Part") "CBG321609U600T")
        (field (name "BOM_Supplier Part") "C1020")
      )
      (libsource (lib "") (part "MLB3216-601(f)_1"))
    )
    (comp (ref "FB310O")
      (value "60Ω")
      (fields
        (field (name "BOM_Manufacturer Part") "CBG321609U600T")
        (field (name "BOM_Supplier Part") "C1020")
      )
      (libsource (lib "") (part "MLB3216-601(f)_30"))
    )
    (comp (ref "FB310P")
      (value "60Ω")
      (fields
        (field (name "BOM_Manufacturer Part") "CBG321609U600T")
        (field (name "BOM_Supplier Part") "C1020")
      )
      (libsource (lib "") (part "MLB3216-601(f)_33"))
    )
    (comp (ref "FB310Q")
      (value "60Ω")
      (fields
        (field (name "BOM_Manufacturer Part") "CBG321609U600T")
        (field (name "BOM_Supplier Part") "C1020")
      )
      (libsource (lib "") (part "MLB3216-601(f)"))
    )
    (comp (ref "FB310R")
      (value "60Ω")
      (fields
        (field (name "BOM_Manufacturer Part") "CBG321609U600T")
        (field (name "BOM_Supplier Part") "C1020")
      )
      (libsource (lib "") (part "MLB3216-601(f)_15"))
    )
    (comp (ref "FB311A")
      (value "60Ω")
      (fields
        (field (name "BOM_Manufacturer Part") "CBG321609U600T")
        (field (name "BOM_Supplier Part") "C1020")
      )
      (libsource (lib "") (part "MLB3216-601(f)_9"))
    )
    (comp (ref "FB311B")
      (value "60Ω")
      (fields
        (field (name "BOM_Manufacturer Part") "CBG321609U600T")
        (field (name "BOM_Supplier Part") "C1020")
      )
      (libsource (lib "") (part "MLB3216-601(f)_32"))
    )
    (comp (ref "FB311C")
      (value "60Ω")
      (fields
        (field (name "BOM_Manufacturer Part") "CBG321609U600T")
        (field (name "BOM_Supplier Part") "C1020")
      )
      (libsource (lib "") (part "MLB3216-601(f)_7"))
    )
    (comp (ref "FB311D")
      (value "60Ω")
      (fields
        (field (name "BOM_Manufacturer Part") "CBG321609U600T")
        (field (name "BOM_Supplier Part") "C1020")
      )
      (libsource (lib "") (part "MLB3216-601(f)_4"))
    )
    (comp (ref "FB311E")
      (value "60Ω")
      (fields
        (field (name "BOM_Manufacturer Part") "CBG321609U600T")
        (field (name "BOM_Supplier Part") "C1020")
      )
      (libsource (lib "") (part "MLB3216-601(f)_16"))
    )
    (comp (ref "FB311F")
      (value "60Ω")
      (fields
        (field (name "BOM_Manufacturer Part") "CBG321609U600T")
        (field (name "BOM_Supplier Part") "C1020")
      )
      (libsource (lib "") (part "MLB3216-601(f)_28"))
    )
    (comp (ref "FB311G")
      (value "60Ω")
      (fields
        (field (name "BOM_Manufacturer Part") "CBG321609U600T")
        (field (name "BOM_Supplier Part") "C1020")
      )
      (libsource (lib "") (part "MLB3216-601(f)_35"))
    )
    (comp (ref "FB311H")
      (value "60Ω")
      (fields
        (field (name "BOM_Manufacturer Part") "CBG321609U600T")
        (field (name "BOM_Supplier Part") "C1020")
      )
      (libsource (lib "") (part "MLB3216-601(f)_29"))
    )
    (comp (ref "FB311I")
      (value "60Ω")
      (fields
        (field (name "BOM_Manufacturer Part") "CBG321609U600T")
        (field (name "BOM_Supplier Part") "C1020")
      )
      (libsource (lib "") (part "MLB3216-601(f)_10"))
    )
    (comp (ref "FB311J")
      (value "60Ω")
      (fields
        (field (name "BOM_Manufacturer Part") "CBG321609U600T")
        (field (name "BOM_Supplier Part") "C1020")
      )
      (libsource (lib "") (part "MLB3216-601(f)_13"))
    )
    (comp (ref "FB311K")
      (value "60Ω")
      (fields
        (field (name "BOM_Manufacturer Part") "CBG321609U600T")
        (field (name "BOM_Supplier Part") "C1020")
      )
      (libsource (lib "") (part "MLB3216-601(f)_31"))
    )
    (comp (ref "FB311L")
      (value "60Ω")
      (fields
        (field (name "BOM_Manufacturer Part") "CBG321609U600T")
        (field (name "BOM_Supplier Part") "C1020")
      )
      (libsource (lib "") (part "MLB3216-601(f)_11"))
    )
    (comp (ref "FB311M")
      (value "60Ω")
      (fields
        (field (name "BOM_Manufacturer Part") "CBG321609U600T")
        (field (name "BOM_Supplier Part") "C1020")
      )
      (libsource (lib "") (part "MLB3216-601(f)_8"))
    )
    (comp (ref "FB311N")
      (value "60Ω")
      (fields
        (field (name "BOM_Manufacturer Part") "CBG321609U600T")
        (field (name "BOM_Supplier Part") "C1020")
      )
      (libsource (lib "") (part "MLB3216-601(f)_12"))
    )
    (comp (ref "FB311O")
      (value "60Ω")
      (fields
        (field (name "BOM_Manufacturer Part") "CBG321609U600T")
        (field (name "BOM_Supplier Part") "C1020")
      )
      (libsource (lib "") (part "MLB3216-601(f)_24"))
    )
    (comp (ref "FB311P")
      (value "60Ω")
      (fields
        (field (name "BOM_Manufacturer Part") "CBG321609U600T")
        (field (name "BOM_Supplier Part") "C1020")
      )
      (libsource (lib "") (part "MLB3216-601(f)_22"))
    )
    (comp (ref "FB311Q")
      (value "60Ω")
      (fields
        (field (name "BOM_Manufacturer Part") "CBG321609U600T")
        (field (name "BOM_Supplier Part") "C1020")
      )
      (libsource (lib "") (part "MLB3216-601(f)_27"))
    )
    (comp (ref "FB311R")
      (value "60Ω")
      (fields
        (field (name "BOM_Manufacturer Part") "CBG321609U600T")
        (field (name "BOM_Supplier Part") "C1020")
      )
      (libsource (lib "") (part "MLB3216-601(f)_34"))
    )
    (comp (ref "R212A")
      (value "1K")
      (fields
        (field (name "BOM_Manufacturer Part") "1206W4F1001T5E")
        (field (name "BOM_Supplier Part") "C4410")
      )
      (libsource (lib "") (part "1206W4F1001T5E_7"))
    )
    (comp (ref "R212B")
      (value "1K")
      (fields
        (field (name "BOM_Manufacturer Part") "1206W4F1001T5E")
        (field (name "BOM_Supplier Part") "C4410")
      )
      (libsource (lib "") (part "1206W4F1001T5E_2"))
    )
    (comp (ref "R212C")
      (value "1K")
      (fields
        (field (name "BOM_Manufacturer Part") "1206W4F1001T5E")
        (field (name "BOM_Supplier Part") "C4410")
      )
      (libsource (lib "") (part "1206W4F1001T5E_6"))
    )
    (comp (ref "R212D")
      (value "1K")
      (fields
        (field (name "BOM_Manufacturer Part") "1206W4F1001T5E")
        (field (name "BOM_Supplier Part") "C4410")
      )
      (libsource (lib "") (part "1206W4F1001T5E_4"))
    )
    (comp (ref "R212E")
      (value "1K")
      (fields
        (field (name "BOM_Manufacturer Part") "1206W4F1001T5E")
        (field (name "BOM_Supplier Part") "C4410")
      )
      (libsource (lib "") (part "1206W4F1001T5E_3"))
    )
    (comp (ref "R212F")
      (value "1K")
      (fields
        (field (name "BOM_Manufacturer Part") "1206W4F1001T5E")
        (field (name "BOM_Supplier Part") "C4410")
      )
      (libsource (lib "") (part "1206W4F1001T5E_5"))
    )
    (comp (ref "R212G")
      (value "1K")
      (fields
        (field (name "BOM_Manufacturer Part") "1206W4F1001T5E")
        (field (name "BOM_Supplier Part") "C4410")
      )
      (libsource (lib "") (part "1206W4F1001T5E_1"))
    )
    (comp (ref "R212H")
      (value "1K")
      (fields
        (field (name "BOM_Manufacturer Part") "1206W4F1001T5E")
        (field (name "BOM_Supplier Part") "C4410")
      )
      (libsource (lib "") (part "1206W4F1001T5E"))
    )
    (comp (ref "RP300A")
      (value "220/330 Term")
      (fields
        (field (name "BOM_Manufacturer Part") "4608X-104-331/221L")
        (field (name "BOM_Supplier Part") "652-4608X104331/221L")
      )
      (libsource (lib "") (part "SCSI Terminator sip-8_1"))
    )
    (comp (ref "RP300B")
      (value "220/330 Term")
      (fields
        (field (name "BOM_Manufacturer Part") "4608X-104-331/221L")
        (field (name "BOM_Supplier Part") "652-4608X104331/221L")
      )
      (libsource (lib "") (part "SCSI Terminator sip-8_2"))
    )
    (comp (ref "RP300C")
      (value "220/330 Term")
      (fields
        (field (name "BOM_Manufacturer Part") "4608X-104-331/221L")
        (field (name "BOM_Supplier Part") "652-4608X104331/221L")
      )
      (libsource (lib "") (part "SCSI Terminator sip-8"))
    )
    (comp (ref "SW1")
      (value "DA-08RP")
      (fields (field (name "BOM_Supplier Part") "C129027"))
      (libsource (lib "") (part "DA-08RP"))
    )
    (comp (ref "U213")
      (value "74F244")
      (fields (field (name "BOM_Manufacturer Part") "74F244SCX") (field (name "BOM_Supplier Part") "C5555"))
      (libsource (lib "") (part "74F244SCX"))
    )
    (comp (ref "U310") (value "DS2107S") (libsource (lib "") (part "DS2107S")))
    (comp (ref "U311") (value "DS2107S") (libsource (lib "") (part "DS2107S")))
    (comp (ref "C300A")
      (value "100nF")
      (fields
        (field (name "BOM_Manufacturer Part") "CL31B104KBCNNNC")
        (field (name "BOM_Supplier Part") "C24497")
      )
      (libsource (lib "") (part "CL31B104KBCNNNC_5"))
    )
    (comp (ref "C300B")
      (value "10nF")
      (fields
        (field (name "BOM_Manufacturer Part") "1206B103K500NT")
        (field (name "BOM_Supplier Part") "C1846")
      )
      (libsource (lib "") (part "1206B103K500NT_2"))
    )
    (comp (ref "C300C")
      (value "100nF")
      (fields
        (field (name "BOM_Manufacturer Part") "CL31B104KBCNNNC")
        (field (name "BOM_Supplier Part") "C24497")
      )
      (libsource (lib "") (part "CL31B104KBCNNNC_2"))
    )
    (comp (ref "C300D")
      (value "10nF")
      (fields
        (field (name "BOM_Manufacturer Part") "1206B103K500NT")
        (field (name "BOM_Supplier Part") "C1846")
      )
      (libsource (lib "") (part "1206B103K500NT_4"))
    )
    (comp (ref "C300E")
      (value "100nF")
      (fields
        (field (name "BOM_Manufacturer Part") "CL31B104KBCNNNC")
        (field (name "BOM_Supplier Part") "C24497")
      )
      (libsource (lib "") (part "CL31B104KBCNNNC"))
    )
    (comp (ref "C300F")
      (value "10nF")
      (fields
        (field (name "BOM_Manufacturer Part") "1206B103K500NT")
        (field (name "BOM_Supplier Part") "C1846")
      )
      (libsource (lib "") (part "1206B103K500NT_3"))
    )
    (comp (ref "C300G")
      (value "100nF")
      (fields
        (field (name "BOM_Manufacturer Part") "CL31B104KBCNNNC")
        (field (name "BOM_Supplier Part") "C24497")
      )
      (libsource (lib "") (part "CL31B104KBCNNNC_4"))
    )
    (comp (ref "C300H")
      (value "10nF")
      (fields
        (field (name "BOM_Manufacturer Part") "1206B103K500NT")
        (field (name "BOM_Supplier Part") "C1846")
      )
      (libsource (lib "") (part "1206B103K500NT_1"))
    )
    (comp (ref "C300I")
      (value "100nF")
      (fields
        (field (name "BOM_Manufacturer Part") "CL31B104KBCNNNC")
        (field (name "BOM_Supplier Part") "C24497")
      )
      (libsource (lib "") (part "CL31B104KBCNNNC_1"))
    )
    (comp (ref "C301A")
      (value "10nF")
      (fields
        (field (name "BOM_Manufacturer Part") "1206B103K500NT")
        (field (name "BOM_Supplier Part") "C1846")
      )
      (libsource (lib "") (part "1206B103K500NT"))
    )
    (comp (ref "C302A")
      (value "100nF")
      (fields
        (field (name "BOM_Manufacturer Part") "CL31B104KBCNNNC")
        (field (name "BOM_Supplier Part") "C24497")
      )
      (libsource (lib "") (part "CL31B104KBCNNNC_3"))
    )
    (comp (ref "CN308")
      (value "TO-MB")
      (fields
        (field (name "BOM_Manufacturer Part") "Header2.54mm 1*3P")
        (field (name "BOM_Supplier Part") "C49257")
      )
      (libsource (lib "") (part "Header-Male-2.54_1x3_1"))
    )
    (comp (ref "CN351")
      (value "TO-LED")
      (fields
        (field (name "BOM_Manufacturer Part") "Header2.54mm 1*3P")
        (field (name "BOM_Supplier Part") "C49257")
      )
      (libsource (lib "") (part "Header-Male-2.54_1x3_1"))
    )
    (comp (ref "FB502")
      (value "60Ω")
      (fields
        (field (name "BOM_Manufacturer Part") "CBG321609U600T")
        (field (name "BOM_Supplier Part") "C1020")
      )
      (libsource (lib "") (part "MLB3216-601(f)_1"))
    )
    (comp (ref "FB503")
      (value "60Ω")
      (fields
        (field (name "BOM_Manufacturer Part") "CBG321609U600T")
        (field (name "BOM_Supplier Part") "C1020")
      )
      (libsource (lib "") (part "MLB3216-601(f)"))
    )
    (comp (ref "FB506")
      (value "60Ω")
      (fields
        (field (name "BOM_Manufacturer Part") "CBG321609U600T")
        (field (name "BOM_Supplier Part") "C1020")
      )
      (libsource (lib "") (part "MLB3216-601(f)_1"))
    )
    (comp (ref "J100")
      (value "ESIZE")
      (fields
        (field (name "BOM_Manufacturer Part") "Header2.54mm 1*3P")
        (field (name "BOM_Supplier Part") "C49257")
      )
      (libsource (lib "") (part "Header-Male-2.54_1x3"))
    )
    (comp (ref "R300A")
      (value "1K")
      (fields
        (field (name "BOM_Manufacturer Part") "1206W4F1001T5E")
        (field (name "BOM_Supplier Part") "C4410")
      )
      (libsource (lib "") (part "1206W4F1001T5E_8"))
    )
    (comp (ref "R300B")
      (value "1K")
      (fields
        (field (name "BOM_Manufacturer Part") "1206W4F1001T5E")
        (field (name "BOM_Supplier Part") "C4410")
      )
      (libsource (lib "") (part "1206W4F1001T5E_1"))
    )
    (comp (ref "R300C")
      (value "1K")
      (fields
        (field (name "BOM_Manufacturer Part") "1206W4F1001T5E")
        (field (name "BOM_Supplier Part") "C4410")
      )
      (libsource (lib "") (part "1206W4F1001T5E_5"))
    )
    (comp (ref "R300D")
      (value "1K")
      (fields
        (field (name "BOM_Manufacturer Part") "1206W4F1001T5E")
        (field (name "BOM_Supplier Part") "C4410")
      )
      (libsource (lib "") (part "1206W4F1001T5E_7"))
    )
    (comp (ref "R300E")
      (value "1K")
      (fields
        (field (name "BOM_Manufacturer Part") "1206W4F1001T5E")
        (field (name "BOM_Supplier Part") "C4410")
      )
      (libsource (lib "") (part "1206W4F1001T5E_9"))
    )
    (comp (ref "R300F")
      (value "1K")
      (fields
        (field (name "BOM_Manufacturer Part") "1206W4F1001T5E")
        (field (name "BOM_Supplier Part") "C4410")
      )
      (libsource (lib "") (part "1206W4F1001T5E_2"))
    )
    (comp (ref "R300G")
      (value "1K")
      (fields
        (field (name "BOM_Manufacturer Part") "1206W4F1001T5E")
        (field (name "BOM_Supplier Part") "C4410")
      )
      (libsource (lib "") (part "1206W4F1001T5E"))
    )
    (comp (ref "R300H")
      (value "1K")
      (fields
        (field (name "BOM_Manufacturer Part") "1206W4F1001T5E")
        (field (name "BOM_Supplier Part") "C4410")
      )
      (libsource (lib "") (part "1206W4F1001T5E_3"))
    )
    (comp (ref "R300I")
      (value "1K")
      (fields
        (field (name "BOM_Manufacturer Part") "1206W4F1001T5E")
        (field (name "BOM_Supplier Part") "C4410")
      )
      (libsource (lib "") (part "1206W4F1001T5E_16"))
    )
    (comp (ref "R300J")
      (value "1K")
      (fields
        (field (name "BOM_Manufacturer Part") "1206W4F1001T5E")
        (field (name "BOM_Supplier Part") "C4410")
      )
      (libsource (lib "") (part "1206W4F1001T5E_13"))
    )
    (comp (ref "R300K")
      (value "1K")
      (fields
        (field (name "BOM_Manufacturer Part") "1206W4F1001T5E")
        (field (name "BOM_Supplier Part") "C4410")
      )
      (libsource (lib "") (part "1206W4F1001T5E_6"))
    )
    (comp (ref "R300L")
      (value "1K")
      (fields
        (field (name "BOM_Manufacturer Part") "1206W4F1001T5E")
        (field (name "BOM_Supplier Part") "C4410")
      )
      (libsource (lib "") (part "1206W4F1001T5E_12"))
    )
    (comp (ref "R300M")
      (value "1K")
      (fields
        (field (name "BOM_Manufacturer Part") "1206W4F1001T5E")
        (field (name "BOM_Supplier Part") "C4410")
      )
      (libsource (lib "") (part "1206W4F1001T5E_4"))
    )
    (comp (ref "R300N")
      (value "1K")
      (fields
        (field (name "BOM_Manufacturer Part") "1206W4F1001T5E")
        (field (name "BOM_Supplier Part") "C4410")
      )
      (libsource (lib "") (part "1206W4F1001T5E_15"))
    )
    (comp (ref "R300O")
      (value "1K")
      (fields
        (field (name "BOM_Manufacturer Part") "1206W4F1001T5E")
        (field (name "BOM_Supplier Part") "C4410")
      )
      (libsource (lib "") (part "1206W4F1001T5E_14"))
    )
    (comp (ref "R300P")
      (value "1K")
      (fields
        (field (name "BOM_Manufacturer Part") "1206W4F1001T5E")
        (field (name "BOM_Supplier Part") "C4410")
      )
      (libsource (lib "") (part "1206W4F1001T5E_17"))
    )
    (comp (ref "R301A")
      (value "22")
      (fields
        (field (name "BOM_Manufacturer Part") "1206W4F220JT5E")
        (field (name "BOM_Supplier Part") "C17958")
      )
      (libsource (lib "") (part "RS-06K22R0FT_1"))
    )
    (comp (ref "R302A")
      (value "22")
      (fields
        (field (name "BOM_Manufacturer Part") "1206W4F220JT5E")
        (field (name "BOM_Supplier Part") "C17958")
      )
      (libsource (lib "") (part "RS-06K22R0FT_2"))
    )
    (comp (ref "R302B")
      (value "22")
      (fields
        (field (name "BOM_Manufacturer Part") "1206W4F220JT5E")
        (field (name "BOM_Supplier Part") "C17958")
      )
      (libsource (lib "") (part "RS-06K22R0FT"))
    )
    (comp (ref "R307A")
      (value "1K")
      (fields
        (field (name "BOM_Manufacturer Part") "1206W4F1001T5E")
        (field (name "BOM_Supplier Part") "C4410")
      )
      (libsource (lib "") (part "1206W4F1001T5E_10"))
    )
    (comp (ref "R307B")
      (value "1K")
      (fields
        (field (name "BOM_Manufacturer Part") "1206W4F1001T5E")
        (field (name "BOM_Supplier Part") "C4410")
      )
      (libsource (lib "") (part "1206W4F1001T5E_11"))
    )
    (comp (ref "R398")
      (value "120")
      (fields
        (field (name "BOM_Manufacturer Part") "1206W4F1200T5E")
        (field (name "BOM_Supplier Part") "C17909")
      )
      (libsource (lib "") (part "RTT061200FTP"))
    )
    (comp (ref "U206")
      (value "27c256")
      (fields
        (field (name "BOM_Manufacturer Part") "IC254V-12-28-0743-P1524")
        (field (name "BOM_Supplier Part") "C2874016")
      )
      (libsource (lib "") (part "27c256"))
    )
    (comp (ref "U300") (value "NCR53C710") (libsource (lib "") (part "NCR53C710")))
    (comp (ref "U301")
      (value "Abracon 50MHz AC0 D.9403")
      (fields
        (field (name "BOM_Manufacturer Part") "MXO45T-3C-50M000000")
        (field (name "BOM_Supplier Part") "C1138655")
      )
      (libsource (lib "") (part "Osc"))
    )
    (comp (ref "U302")
      (value "74F74")
      (fields (field (name "BOM_Manufacturer Part") "74F74D") (field (name "BOM_Supplier Part") "C5573"))
      (libsource (lib "") (part "74F74D"))
    )
    (comp (ref "FB500")
      (value "60Ω")
      (fields
        (field (name "BOM_Manufacturer Part") "CBG321609U600T")
        (field (name "BOM_Supplier Part") "C1020")
      )
      (libsource (lib "") (part "MLB3216-601(f)_1"))
    )
    (comp (ref "FB501")
      (value "60Ω")
      (fields
        (field (name "BOM_Manufacturer Part") "CBG321609U600T")
        (field (name "BOM_Supplier Part") "C1020")
      )
      (libsource (lib "") (part "MLB3216-601(f)"))
    )
    (comp (ref "FB504")
      (value "60Ω")
      (fields
        (field (name "BOM_Manufacturer Part") "CBG321609U600T")
        (field (name "BOM_Supplier Part") "C1020")
      )
      (libsource (lib "") (part "MLB3216-601(f)"))
    )
    (comp (ref "FB505")
      (value "60Ω")
      (fields
        (field (name "BOM_Manufacturer Part") "CBG321609U600T")
        (field (name "BOM_Supplier Part") "C1020")
      )
      (libsource (lib "") (part "MLB3216-601(f)"))
    )
    (comp (ref "U202")
      (value "GAL22V10H-15")
      (fields (field (name "BOM_Manufacturer Part") "GAL220V10"))
      (libsource (lib "") (part "GAL22V10"))
    )
    (comp (ref "U203")
      (value "GAL22V10H-15")
      (fields (field (name "BOM_Manufacturer Part") "GAL220V10"))
      (libsource (lib "") (part "GAL22V10"))
    )
    (comp (ref "U205")
      (value "GAL22V10H-15")
      (fields (field (name "BOM_Manufacturer Part") "GAL220V10"))
      (libsource (lib "") (part "GAL22V10"))
    )
    (comp (ref "U207")
      (value "GAL22V10H-15")
      (fields (field (name "BOM_Manufacturer Part") "GAL220V10"))
      (libsource (lib "") (part "GAL22V10"))
    )
    (comp (ref "U303")
      (value "GAL22V10H-15")
      (fields (field (name "BOM_Manufacturer Part") "GAL220V10"))
      (libsource (lib "") (part "GAL22V10"))
    )
    (comp (ref "U304")
      (value "GAL22V10B-10")
      (fields (field (name "BOM_Manufacturer Part") "GAL220V10"))
      (libsource (lib "") (part "GAL22V10"))
    )
    (comp (ref "U305")
      (value "GAL22V10B-10")
      (fields (field (name "BOM_Manufacturer Part") "GAL220V10"))
      (libsource (lib "") (part "GAL22V10"))
    )
    (comp (ref "U306")
      (value "GAL22V10B-10")
      (fields (field (name "BOM_Manufacturer Part") "GAL220V10"))
      (libsource (lib "") (part "GAL22V10"))
    )
    (comp (ref "C1") (value "Zorro III Edge") (libsource (lib "") (part "Zorro III Edge")))
    (comp (ref "C306B")
      (value "10pF")
      (fields
        (field (name "BOM_Manufacturer Part") "CL21C100JBANNNC")
        (field (name "BOM_Supplier Part") "C1785")
      )
      (libsource (lib "") (part "CL21C100JBANNNC"))
    )
    (comp (ref "FB507")
      (value "60Ω")
      (fields
        (field (name "BOM_Manufacturer Part") "CBG321609U600T")
        (field (name "BOM_Supplier Part") "C1020")
      )
      (libsource (lib "") (part "MLB3216-601(f)"))
    )
    (comp (ref "FB508")
      (value "60Ω")
      (fields
        (field (name "BOM_Manufacturer Part") "CBG321609U600T")
        (field (name "BOM_Supplier Part") "C1020")
      )
      (libsource (lib "") (part "MLB3216-601(f)"))
    )
    (comp (ref "R100A")
      (value "1K")
      (fields
        (field (name "BOM_Manufacturer Part") "1206W4F1001T5E")
        (field (name "BOM_Supplier Part") "C4410")
      )
      (libsource (lib "") (part "1206W4F1001T5E_3"))
    )
    (comp (ref "R103A")
      (value "1K")
      (fields
        (field (name "BOM_Manufacturer Part") "1206W4F1001T5E")
        (field (name "BOM_Supplier Part") "C4410")
      )
      (libsource (lib "") (part "1206W4F1001T5E_17"))
    )
    (comp (ref "R103B")
      (value "1K")
      (fields
        (field (name "BOM_Manufacturer Part") "1206W4F1001T5E")
        (field (name "BOM_Supplier Part") "C4410")
      )
      (libsource (lib "") (part "1206W4F1001T5E_6"))
    )
    (comp (ref "R109A")
      (value "1K")
      (fields
        (field (name "BOM_Manufacturer Part") "1206W4F1001T5E")
        (field (name "BOM_Supplier Part") "C4410")
      )
      (libsource (lib "") (part "1206W4F1001T5E_7"))
    )
    (comp (ref "R109B")
      (value "1K")
      (fields
        (field (name "BOM_Manufacturer Part") "1206W4F1001T5E")
        (field (name "BOM_Supplier Part") "C4410")
      )
      (libsource (lib "") (part "1206W4F1001T5E"))
    )
    (comp (ref "R109C")
      (value "1K")
      (fields
        (field (name "BOM_Manufacturer Part") "1206W4F1001T5E")
        (field (name "BOM_Supplier Part") "C4410")
      )
      (libsource (lib "") (part "1206W4F1001T5E_1"))
    )
    (comp (ref "R109D")
      (value "1K")
      (fields
        (field (name "BOM_Manufacturer Part") "1206W4F1001T5E")
        (field (name "BOM_Supplier Part") "C4410")
      )
      (libsource (lib "") (part "1206W4F1001T5E_16"))
    )
    (comp (ref "R109E")
      (value "1K")
      (fields
        (field (name "BOM_Manufacturer Part") "1206W4F1001T5E")
        (field (name "BOM_Supplier Part") "C4410")
      )
      (libsource (lib "") (part "1206W4F1001T5E_10"))
    )
    (comp (ref "R109F")
      (value "1K")
      (fields
        (field (name "BOM_Manufacturer Part") "1206W4F1001T5E")
        (field (name "BOM_Supplier Part") "C4410")
      )
      (libsource (lib "") (part "1206W4F1001T5E_2"))
    )
    (comp (ref "R109G")
      (value "1K")
      (fields
        (field (name "BOM_Manufacturer Part") "1206W4F1001T5E")
        (field (name "BOM_Supplier Part") "C4410")
      )
      (libsource (lib "") (part "1206W4F1001T5E_8"))
    )
    (comp (ref "R109H")
      (value "1K")
      (fields
        (field (name "BOM_Manufacturer Part") "1206W4F1001T5E")
        (field (name "BOM_Supplier Part") "C4410")
      )
      (libsource (lib "") (part "1206W4F1001T5E_9"))
    )
    (comp (ref "R200A")
      (value "1K")
      (fields
        (field (name "BOM_Manufacturer Part") "1206W4F1001T5E")
        (field (name "BOM_Supplier Part") "C4410")
      )
      (libsource (lib "") (part "1206W4F1001T5E_12"))
    )
    (comp (ref "R200B")
      (value "1K")
      (fields
        (field (name "BOM_Manufacturer Part") "1206W4F1001T5E")
        (field (name "BOM_Supplier Part") "C4410")
      )
      (libsource (lib "") (part "1206W4F1001T5E_5"))
    )
    (comp (ref "R200C")
      (value "1K")
      (fields
        (field (name "BOM_Manufacturer Part") "1206W4F1001T5E")
        (field (name "BOM_Supplier Part") "C4410")
      )
      (libsource (lib "") (part "1206W4F1001T5E_18"))
    )
    (comp (ref "R200D")
      (value "1K")
      (fields
        (field (name "BOM_Manufacturer Part") "1206W4F1001T5E")
        (field (name "BOM_Supplier Part") "C4410")
      )
      (libsource (lib "") (part "1206W4F1001T5E_13"))
    )
    (comp (ref "R200E")
      (value "1K")
      (fields
        (field (name "BOM_Manufacturer Part") "1206W4F1001T5E")
        (field (name "BOM_Supplier Part") "C4410")
      )
      (libsource (lib "") (part "1206W4F1001T5E_14"))
    )
    (comp (ref "R200F")
      (value "1K")
      (fields
        (field (name "BOM_Manufacturer Part") "1206W4F1001T5E")
        (field (name "BOM_Supplier Part") "C4410")
      )
      (libsource (lib "") (part "1206W4F1001T5E_11"))
    )
    (comp (ref "R200G")
      (value "1K")
      (fields
        (field (name "BOM_Manufacturer Part") "1206W4F1001T5E")
        (field (name "BOM_Supplier Part") "C4410")
      )
      (libsource (lib "") (part "1206W4F1001T5E_4"))
    )
    (comp (ref "R200H")
      (value "1K")
      (fields
        (field (name "BOM_Manufacturer Part") "1206W4F1001T5E")
        (field (name "BOM_Supplier Part") "C4410")
      )
      (libsource (lib "") (part "1206W4F1001T5E_15"))
    )
    (comp (ref "U100")
      (value "74FCT543TSO")
      (fields (field (name "BOM_Manufacturer Part") "CY74FCT543TSOC"))
      (libsource (lib "") (part "74FCT543TSO"))
    )
    (comp (ref "U101")
      (value "74FCT543TSO")
      (fields (field (name "BOM_Manufacturer Part") "CY74FCT543TSOC"))
      (libsource (lib "") (part "74FCT543TSO"))
    )
    (comp (ref "U102")
      (value "74FCT543TSO")
      (fields (field (name "BOM_Manufacturer Part") "CY74FCT543TSOC"))
      (libsource (lib "") (part "74FCT543TSO"))
    )
    (comp (ref "U103")
      (value "74F245")
      (fields (field (name "BOM_Manufacturer Part") "74F245D") (field (name "BOM_Supplier Part") "C5557"))
      (libsource (lib "") (part "74F245D"))
    )
    (comp (ref "U105")
      (value "74FCT543TSO")
      (fields (field (name "BOM_Manufacturer Part") "CY74FCT543TSOC"))
      (libsource (lib "") (part "74FCT543TSO"))
    )
    (comp (ref "U106")
      (value "74FCT543TSO")
      (fields (field (name "BOM_Manufacturer Part") "CY74FCT543TSOC"))
      (libsource (lib "") (part "74FCT543TSO"))
    )
    (comp (ref "U107")
      (value "74FCT543TSO")
      (fields (field (name "BOM_Manufacturer Part") "CY74FCT543TSOC"))
      (libsource (lib "") (part "74FCT543TSO"))
    )
    (comp (ref "U108")
      (value "74FCT543TSO")
      (fields (field (name "BOM_Manufacturer Part") "CY74FCT543TSOC"))
      (libsource (lib "") (part "74FCT543TSO"))
    )
    (comp (ref "U109")
      (value "74F245")
      (fields (field (name "BOM_Manufacturer Part") "74F245D") (field (name "BOM_Supplier Part") "C5557"))
      (libsource (lib "") (part "74F245D"))
    )
    (comp (ref "U200")
      (value "74FCT374TSO")
      (fields (field (name "BOM_Manufacturer Part") "74F374D") (field (name "BOM_Supplier Part") "C5564"))
      (libsource (lib "") (part "74F374D"))
    )
    (comp (ref "U201")
      (value "74FCT521TSO")
      (fields
        (field (name "BOM_Manufacturer Part") "74FCT521CTSOG8")
        (field (name "BOM_Supplier Part") "972-74FCT521CTSOG8")
      )
      (libsource (lib "") (part "74FCT521TSO"))
    )
    (comp (ref "U204")
      (value "74FCT374TSO")
      (fields (field (name "BOM_Manufacturer Part") "74F374D") (field (name "BOM_Supplier Part") "C5564"))
      (libsource (lib "") (part "74F374D"))
    )
    (comp (ref "U307")
      (value "7407")
      (fields (field (name "BOM_Manufacturer Part") "SN7407DR") (field (name "BOM_Supplier Part") "C40481"))
      (libsource (lib "") (part "SN7407DR"))
    )
    (comp (ref "C1A")
      (value "100nF")
      (fields
        (field (name "BOM_Manufacturer Part") "CL31B104KBCNNNC")
        (field (name "BOM_Supplier Part") "C24497")
      )
      (libsource (lib "") (part "CL31B104KBCNNNC_14"))
    )
    (comp (ref "C1B")
      (value "47uF")
      (fields
        (field (name "BOM_Manufacturer Part") "RVT1V470M0605")
        (field (name "BOM_Supplier Part") "C3344")
      )
      (libsource (lib "") (part "RVT1V470M0605_3"))
    )
    (comp (ref "C1C")
      (value "47uF")
      (fields
        (field (name "BOM_Manufacturer Part") "RVT1V470M0605")
        (field (name "BOM_Supplier Part") "C3344")
      )
      (libsource (lib "") (part "RVT1V470M0605_2"))
    )
    (comp (ref "C10")
      (value "47uF")
      (fields
        (field (name "BOM_Manufacturer Part") "RVT1V470M0605")
        (field (name "BOM_Supplier Part") "C3344")
      )
      (libsource (lib "") (part "RVT1V470M0605_1"))
    )
    (comp (ref "C11")
      (value "47uF")
      (fields
        (field (name "BOM_Manufacturer Part") "RVT1V470M0605")
        (field (name "BOM_Supplier Part") "C3344")
      )
      (libsource (lib "") (part "RVT1V470M0605_1"))
    )
    (comp (ref "C12")
      (value "47uF")
      (fields
        (field (name "BOM_Manufacturer Part") "RVT1V470M0605")
        (field (name "BOM_Supplier Part") "C3344")
      )
      (libsource (lib "") (part "RVT1V470M0605_1"))
    )
    (comp (ref "C13")
      (value "47uF")
      (fields
        (field (name "BOM_Manufacturer Part") "RVT1V470M0605")
        (field (name "BOM_Supplier Part") "C3344")
      )
      (libsource (lib "") (part "RVT1V470M0605"))
    )
    (comp (ref "C100A")
      (value "100nF")
      (fields
        (field (name "BOM_Manufacturer Part") "CL31B104KBCNNNC")
        (field (name "BOM_Supplier Part") "C24497")
      )
      (libsource (lib "") (part "CL31B104KBCNNNC_19"))
    )
    (comp (ref "C101A")
      (value "100nF")
      (fields
        (field (name "BOM_Manufacturer Part") "CL31B104KBCNNNC")
        (field (name "BOM_Supplier Part") "C24497")
      )
      (libsource (lib "") (part "CL31B104KBCNNNC_22"))
    )
    (comp (ref "C102A")
      (value "100nF")
      (fields
        (field (name "BOM_Manufacturer Part") "CL31B104KBCNNNC")
        (field (name "BOM_Supplier Part") "C24497")
      )
      (libsource (lib "") (part "CL31B104KBCNNNC_5"))
    )
    (comp (ref "C103A")
      (value "100nF")
      (fields
        (field (name "BOM_Manufacturer Part") "CL31B104KBCNNNC")
        (field (name "BOM_Supplier Part") "C24497")
      )
      (libsource (lib "") (part "CL31B104KBCNNNC_15"))
    )
    (comp (ref "C105A")
      (value "100nF")
      (fields
        (field (name "BOM_Manufacturer Part") "CL31B104KBCNNNC")
        (field (name "BOM_Supplier Part") "C24497")
      )
      (libsource (lib "") (part "CL31B104KBCNNNC_13"))
    )
    (comp (ref "C106A")
      (value "100nF")
      (fields
        (field (name "BOM_Manufacturer Part") "CL31B104KBCNNNC")
        (field (name "BOM_Supplier Part") "C24497")
      )
      (libsource (lib "") (part "CL31B104KBCNNNC_8"))
    )
    (comp (ref "C107A")
      (value "100nF")
      (fields
        (field (name "BOM_Manufacturer Part") "CL31B104KBCNNNC")
        (field (name "BOM_Supplier Part") "C24497")
      )
      (libsource (lib "") (part "CL31B104KBCNNNC_9"))
    )
    (comp (ref "C108A")
      (value "100nF")
      (fields
        (field (name "BOM_Manufacturer Part") "CL31B104KBCNNNC")
        (field (name "BOM_Supplier Part") "C24497")
      )
      (libsource (lib "") (part "CL31B104KBCNNNC_10"))
    )
    (comp (ref "C109A")
      (value "100nF")
      (fields
        (field (name "BOM_Manufacturer Part") "CL31B104KBCNNNC")
        (field (name "BOM_Supplier Part") "C24497")
      )
      (libsource (lib "") (part "CL31B104KBCNNNC_12"))
    )
    (comp (ref "C200A")
      (value "100nF")
      (fields
        (field (name "BOM_Manufacturer Part") "CL31B104KBCNNNC")
        (field (name "BOM_Supplier Part") "C24497")
      )
      (libsource (lib "") (part "CL31B104KBCNNNC_17"))
    )
    (comp (ref "C201A")
      (value "100nF")
      (fields
        (field (name "BOM_Manufacturer Part") "CL31B104KBCNNNC")
        (field (name "BOM_Supplier Part") "C24497")
      )
      (libsource (lib "") (part "CL31B104KBCNNNC_2"))
    )
    (comp (ref "C202A")
      (value "100nF")
      (fields
        (field (name "BOM_Manufacturer Part") "CL31B104KBCNNNC")
        (field (name "BOM_Supplier Part") "C24497")
      )
      (libsource (lib "") (part "CL31B104KBCNNNC_3"))
    )
    (comp (ref "C203A")
      (value "100nF")
      (fields
        (field (name "BOM_Manufacturer Part") "CL31B104KBCNNNC")
        (field (name "BOM_Supplier Part") "C24497")
      )
      (libsource (lib "") (part "CL31B104KBCNNNC_7"))
    )
    (comp (ref "C204A")
      (value "100nF")
      (fields
        (field (name "BOM_Manufacturer Part") "CL31B104KBCNNNC")
        (field (name "BOM_Supplier Part") "C24497")
      )
      (libsource (lib "") (part "CL31B104KBCNNNC_16"))
    )
    (comp (ref "C205A")
      (value "100nF")
      (fields
        (field (name "BOM_Manufacturer Part") "CL31B104KBCNNNC")
        (field (name "BOM_Supplier Part") "C24497")
      )
      (libsource (lib "") (part "CL31B104KBCNNNC_23"))
    )
    (comp (ref "C206A")
      (value "100nF")
      (fields
        (field (name "BOM_Manufacturer Part") "CL31B104KBCNNNC")
        (field (name "BOM_Supplier Part") "C24497")
      )
      (libsource (lib "") (part "CL31B104KBCNNNC_21"))
    )
    (comp (ref "C207A")
      (value "100nF")
      (fields
        (field (name "BOM_Manufacturer Part") "CL31B104KBCNNNC")
        (field (name "BOM_Supplier Part") "C24497")
      )
      (libsource (lib "") (part "CL31B104KBCNNNC_20"))
    )
    (comp (ref "C212A")
      (value "100nF")
      (fields
        (field (name "BOM_Manufacturer Part") "CL31B104KBCNNNC")
        (field (name "BOM_Supplier Part") "C24497")
      )
      (libsource (lib "") (part "CL31B104KBCNNNC"))
    )
    (comp (ref "C303A")
      (value "100nF")
      (fields
        (field (name "BOM_Manufacturer Part") "CL31B104KBCNNNC")
        (field (name "BOM_Supplier Part") "C24497")
      )
      (libsource (lib "") (part "CL31B104KBCNNNC_11"))
    )
    (comp (ref "C304A")
      (value "100nF")
      (fields
        (field (name "BOM_Manufacturer Part") "CL31B104KBCNNNC")
        (field (name "BOM_Supplier Part") "C24497")
      )
      (libsource (lib "") (part "CL31B104KBCNNNC_1"))
    )
    (comp (ref "C305A")
      (value "100nF")
      (fields
        (field (name "BOM_Manufacturer Part") "CL31B104KBCNNNC")
        (field (name "BOM_Supplier Part") "C24497")
      )
      (libsource (lib "") (part "CL31B104KBCNNNC_18"))
    )
    (comp (ref "C306A")
      (value "100nF")
      (fields
        (field (name "BOM_Manufacturer Part") "CL31B104KBCNNNC")
        (field (name "BOM_Supplier Part") "C24497")
      )
      (libsource (lib "") (part "CL31B104KBCNNNC_4"))
    )
    (comp (ref "C307A")
      (value "100nF")
      (fields
        (field (name "BOM_Manufacturer Part") "CL31B104KBCNNNC")
        (field (name "BOM_Supplier Part") "C24497")
      )
      (libsource (lib "") (part "CL31B104KBCNNNC_6"))
    )
    (comp (ref "CN2")
      (value "TE-350211-1")
      (fields
        (field (name "BOM_Manufacturer Part") "350211-1")
        (field (name "BOM_Supplier Part") "AN1212-ND")
      )
      (libsource (lib "") (part "TE-350211-1-Simple"))
    )
    (comp (ref "CN3")
      (value "TE 171826-4")
      (fields
        (field (name "BOM_Manufacturer Part") "171826-4")
        (field (name "BOM_Supplier Part") "A112643-ND")
      )
      (libsource (lib "") (part "FLOPPY PWR TE 171826-4"))
    )
    (comp (ref "CN4")
      (value "Fan")
      (fields
        (field (name "BOM_Manufacturer Part") "KF2510-3AGW")
        (field (name "BOM_Supplier Part") "C722745")
      )
      (libsource (lib "") (part "KF2510-3AGW_C722745"))
    )
    (comp (ref "D309A")
      (value "TMBYV10")
      (fields
        (field (name "BOM_Manufacturer Part") "TMBYV10-40FILM")
        (field (name "BOM_Supplier Part") "C283270")
      )
      (libsource (lib "") (part "LL4007G L0"))
    )
    (comp (ref "F309A")
      (value "TH Polyfuse 1.85A")
      (fields (field (name "BOM_Manufacturer Part") "A72-185") (field (name "BOM_Supplier Part") "C135432"))
      (libsource (lib "") (part "A72-185 POLYFUSE"))
    )
    (comp (ref "F309B")
      (value "SMD Polyfuse 1.85A")
      (fields
        (field (name "BOM_Manufacturer Part") "SMD2920B185TF")
        (field (name "BOM_Supplier Part") "C269182")
      )
      (libsource (lib "") (part "A72-185-POLYFUSE-SMD"))
    )
    (comp (ref "FID1")
      (value "FIDUCIAL_SQUARE_DOT_128_100")
      (libsource (lib "") (part "FIDUCIAL_SQUARE_DOT_128_100"))
    )
    (comp (ref "FID2")
      (value "FIDUCIAL_SQUARE_DOT_128_100")
      (libsource (lib "") (part "FIDUCIAL_SQUARE_DOT_128_100"))
    )
    (comp (ref "FID3")
      (value "FIDUCIAL_SQUARE_DOT_128_100")
      (libsource (lib "") (part "FIDUCIAL_SQUARE_DOT_128_100"))
    )
    (comp (ref "FID4")
      (value "FIDUCIAL_SQUARE_DOT_128_100")
      (libsource (lib "") (part "FIDUCIAL_SQUARE_DOT_128_100"))
    )
    (comp (ref "FID5")
      (value "FIDUCIAL_SQUARE_DOT_128_100")
      (libsource (lib "") (part "FIDUCIAL_SQUARE_DOT_128_100"))
    )
    (comp (ref "FID6")
      (value "FIDUCIAL_SQUARE_DOT_128_100")
      (libsource (lib "") (part "FIDUCIAL_SQUARE_DOT_128_100"))
    )
    (comp (ref "MB1") (value "Mousebites") (libsource (lib "") (part "Mousebites")))
    (comp (ref "MB2") (value "Mousebites") (libsource (lib "") (part "Mousebites")))
    (comp (ref "MH1")
      (value "MOUNTINGHOLE_4MM")
      (fields (field (name "BOM_Manufacturer Part") "Mounting hole"))
      (libsource (lib "") (part "MOUNTINGHOLE_4MM"))
    )
    (comp (ref "MH2")
      (value "MOUNTINGHOLE_4MM")
      (fields (field (name "BOM_Manufacturer Part") "Mounting hole"))
      (libsource (lib "") (part "MOUNTINGHOLE_4MM"))
    )
    (comp (ref "MH3")
      (value "MOUNTINGHOLE_4MM")
      (fields (field (name "BOM_Manufacturer Part") "Mounting hole"))
      (libsource (lib "") (part "MOUNTINGHOLE_4MM"))
    )
    (comp (ref "MH4")
      (value "MOUNTINGHOLE_4MM")
      (fields (field (name "BOM_Manufacturer Part") "Mounting hole"))
      (libsource (lib "") (part "MOUNTINGHOLE_4MM"))
    )
    (comp (ref "MK5") (value "Mounting_Hole") (libsource (lib "") (part "Mounting_Hole")))
    (comp (ref "MK6") (value "Mounting_Hole") (libsource (lib "") (part "Mounting_Hole")))
    (comp (ref "MK7") (value "Mounting_Hole") (libsource (lib "") (part "Mounting_Hole")))
    (comp (ref "C400A")
      (value "4.7uF")
      (fields
        (field (name "BOM_Manufacturer Part") "UWX1E4R7MCL1GB")
        (field (name "BOM_Supplier Part") "C445042")
      )
      (libsource (lib "") (part "VZH4R7M1HTR-0406_2"))
    )
    (comp (ref "C400B")
      (value "100nF")
      (fields
        (field (name "BOM_Manufacturer Part") "CL31B104KBCNNNC")
        (field (name "BOM_Supplier Part") "C24497")
      )
      (libsource (lib "") (part "CL31B104KBCNNNC_1"))
    )
    (comp (ref "C401A")
      (value "4.7uF")
      (fields
        (field (name "BOM_Manufacturer Part") "UWX1E4R7MCL1GB")
        (field (name "BOM_Supplier Part") "C445042")
      )
      (libsource (lib "") (part "VZH4R7M1HTR-0406_1"))
    )
    (comp (ref "C401B")
      (value "100nF")
      (fields
        (field (name "BOM_Manufacturer Part") "CL31B104KBCNNNC")
        (field (name "BOM_Supplier Part") "C24497")
      )
      (libsource (lib "") (part "CL31B104KBCNNNC"))
    )
    (comp (ref "C402")
      (value "100nF")
      (fields
        (field (name "BOM_Manufacturer Part") "CL31B104KBCNNNC")
        (field (name "BOM_Supplier Part") "C24497")
      )
      (libsource (lib "") (part "CL31B104KBCNNNC_2"))
    )
    (comp (ref "C403")
      (value "4.7uF")
      (fields
        (field (name "BOM_Manufacturer Part") "UWX1E4R7MCL1GB")
        (field (name "BOM_Supplier Part") "C445042")
      )
      (libsource (lib "") (part "VZH4R7M1HTR-0406"))
    )
    (comp (ref "CN400")
      (value "IDC-M-Right")
      (fields
        (field (name "BOM_Manufacturer Part") "Z-231012050106")
        (field (name "BOM_Supplier Part") "C221060")
      )
      (libsource (lib "") (part "Z-231012050106"))
    )
    (comp (ref "FID7")
      (value "FIDUCIAL_SQUARE_DOT_128_100")
      (libsource (lib "") (part "FIDUCIAL_SQUARE_DOT_128_100"))
    )
    (comp (ref "FID8")
      (value "FIDUCIAL_SQUARE_DOT_128_100")
      (libsource (lib "") (part "FIDUCIAL_SQUARE_DOT_128_100"))
    )
    (comp (ref "MK1") (value "Mounting_Hole") (libsource (lib "") (part "Mounting_Hole")))
    (comp (ref "MK2") (value "Mounting_Hole") (libsource (lib "") (part "Mounting_Hole")))
    (comp (ref "U400") (value "DS2107S") (libsource (lib "") (part "DS2107S")))
    (comp (ref "U401") (value "DS2107S") (libsource (lib "") (part "DS2107S")))
  )
  (nets
    (net (code "1") (name "A0") (class "Default")
      (node (ref "R300K") (pin "1") (pinfunction "1_1") (pintype "input"))
      (node (ref "U300") (pin "144") (pinfunction "A0_144") (pintype "unspecified"))
      (node (ref "U304") (pin "26") (pinfunction "IOQ_26") (pintype "unspecified"))
      (node (ref "U305") (pin "16") (pinfunction "I_16") (pintype "unspecified"))
    )
    (net (code "2") (name "A1") (class "Default")
      (node (ref "R300L") (pin "1") (pinfunction "1_1") (pintype "input"))
      (node (ref "U300") (pin "145") (pinfunction "A1_145") (pintype "unspecified"))
      (node (ref "U304") (pin "27") (pinfunction "IOQ_27") (pintype "unspecified"))
      (node (ref "U305") (pin "13") (pinfunction "I_13") (pintype "unspecified"))
    )
    (net (code "3") (name "A2") (class "Default")
      (node (ref "R300I") (pin "1") (pinfunction "1_1") (pintype "input"))
      (node (ref "U103") (pin "7") (pinfunction "A5_7") (pintype "unspecified"))
      (node (ref "U202") (pin "7") (pinfunction "I_7") (pintype "unspecified"))
      (node (ref "U206") (pin "10") (pinfunction "A0_10") (pintype "input"))
      (node (ref "U300") (pin "146") (pinfunction "A2_146") (pintype "unspecified"))
    )
    (net (code "4") (name "A3") (class "Default")
      (node (ref "R300J") (pin "1") (pinfunction "1_1") (pintype "input"))
      (node (ref "U103") (pin "6") (pinfunction "A4_6") (pintype "unspecified"))
      (node (ref "U202") (pin "6") (pinfunction "I_6") (pintype "unspecified"))
      (node (ref "U206") (pin "9") (pinfunction "A1_9") (pintype "input"))
      (node (ref "U300") (pin "147") (pinfunction "A3_147") (pintype "unspecified"))
    )
    (net (code "5") (name "A4") (class "Default")
      (node (ref "U103") (pin "5") (pinfunction "A3_5") (pintype "unspecified"))
      (node (ref "U202") (pin "5") (pinfunction "I_5") (pintype "unspecified"))
      (node (ref "U206") (pin "8") (pinfunction "A2_8") (pintype "input"))
      (node (ref "U300") (pin "148") (pinfunction "A4_148") (pintype "unspecified"))
    )
    (net (code "6") (name "A5") (class "Default")
      (node (ref "U103") (pin "4") (pinfunction "A2_4") (pintype "unspecified"))
      (node (ref "U202") (pin "4") (pinfunction "I_4") (pintype "unspecified"))
      (node (ref "U206") (pin "7") (pinfunction "A3_7") (pintype "input"))
      (node (ref "U300") (pin "150") (pinfunction "A5_150") (pintype "unspecified"))
    )
    (net (code "7") (name "A6") (class "Default")
      (node (ref "U103") (pin "3") (pinfunction "A1_3") (pintype "unspecified"))
      (node (ref "U202") (pin "3") (pinfunction "I_3") (pintype "unspecified"))
      (node (ref "U206") (pin "6") (pinfunction "A4_6") (pintype "input"))
      (node (ref "U300") (pin "151") (pinfunction "A6_151") (pintype "unspecified"))
    )
    (net (code "8") (name "A7") (class "Default")
      (node (ref "U103") (pin "2") (pinfunction "A0_2") (pintype "unspecified"))
      (node (ref "U206") (pin "5") (pinfunction "A5_5") (pintype "input"))
      (node (ref "U300") (pin "152") (pinfunction "A7_152") (pintype "unspecified"))
    )
    (net (code "9") (name "A8") (class "Default")
      (node (ref "U102") (pin "10") (pinfunction "A7_10") (pintype "bidirectional"))
      (node (ref "U202") (pin "9") (pinfunction "I_9") (pintype "unspecified"))
      (node (ref "U206") (pin "4") (pinfunction "A6_4") (pintype "input"))
      (node (ref "U300") (pin "154") (pinfunction "A8_154") (pintype "unspecified"))
    )
    (net (code "10") (name "A9") (class "Default")
      (node (ref "U102") (pin "9") (pinfunction "A6_9") (pintype "bidirectional"))
      (node (ref "U206") (pin "3") (pinfunction "A7_3") (pintype "input"))
      (node (ref "U300") (pin "155") (pinfunction "A9_155") (pintype "unspecified"))
    )
    (net (code "11") (name "A10") (class "Default")
      (node (ref "U102") (pin "8") (pinfunction "A5_8") (pintype "bidirectional"))
      (node (ref "U206") (pin "25") (pinfunction "A8_25") (pintype "output"))
      (node (ref "U300") (pin "157") (pinfunction "A10_157") (pintype "unspecified"))
    )
    (net (code "12") (name "A11") (class "Default")
      (node (ref "U102") (pin "7") (pinfunction "A4_7") (pintype "bidirectional"))
      (node (ref "U206") (pin "24") (pinfunction "A9_24") (pintype "output"))
      (node (ref "U300") (pin "158") (pinfunction "A11_158") (pintype "unspecified"))
    )
    (net (code "13") (name "A12") (class "Default")
      (node (ref "U102") (pin "6") (pinfunction "A3_6") (pintype "bidirectional"))
      (node (ref "U206") (pin "21") (pinfunction "A10_21") (pintype "output"))
      (node (ref "U300") (pin "159") (pinfunction "A12_159") (pintype "unspecified"))
    )
    (net (code "14") (name "A13") (class "Default")
      (node (ref "U102") (pin "5") (pinfunction "A2_5") (pintype "bidirectional"))
      (node (ref "U206") (pin "23") (pinfunction "A11_23") (pintype "output"))
      (node (ref "U300") (pin "160") (pinfunction "A13_160") (pintype "unspecified"))
    )
    (net (code "15") (name "A14") (class "Default")
      (node (ref "U102") (pin "4") (pinfunction "A1_4") (pintype "bidirectional"))
      (node (ref "U206") (pin "2") (pinfunction "A12_2") (pintype "input"))
      (node (ref "U300") (pin "1") (pinfunction "A14_1") (pintype "unspecified"))
    )
    (net (code "16") (name "A15") (class "Default")
      (node (ref "U102") (pin "3") (pinfunction "A0_3") (pintype "bidirectional"))
      (node (ref "U206") (pin "26") (pinfunction "A13_26") (pintype "output"))
      (node (ref "U300") (pin "3") (pinfunction "A15_3") (pintype "unspecified"))
    )
    (net (code "17") (name "A16") (class "Default")
      (node (ref "U101") (pin "10") (pinfunction "A7_10") (pintype "bidirectional"))
      (node (ref "U206") (pin "27") (pinfunction "A14_27") (pintype "output"))
      (node (ref "U300") (pin "4") (pinfunction "A16_4") (pintype "unspecified"))
    )
    (net (code "18") (name "A17") (class "Default")
      (node (ref "J100") (pin "3") (pinfunction "3_3") (pintype "input"))
      (node (ref "U101") (pin "9") (pinfunction "A6_9") (pintype "bidirectional"))
      (node (ref "U203") (pin "5") (pinfunction "I_5") (pintype "unspecified"))
      (node (ref "U300") (pin "5") (pinfunction "A17_5") (pintype "unspecified"))
    )
    (net (code "19") (name "A18") (class "Default")
      (node (ref "U101") (pin "8") (pinfunction "A5_8") (pintype "bidirectional"))
      (node (ref "U203") (pin "4") (pinfunction "I_4") (pintype "unspecified"))
      (node (ref "U300") (pin "7") (pinfunction "A18_7") (pintype "unspecified"))
    )
    (net (code "20") (name "A19") (class "Default")
      (node (ref "U101") (pin "7") (pinfunction "A4_7") (pintype "bidirectional"))
      (node (ref "U203") (pin "3") (pinfunction "I_3") (pintype "unspecified"))
      (node (ref "U300") (pin "8") (pinfunction "A19_8") (pintype "unspecified"))
    )
    (net (code "21") (name "A20") (class "Default")
      (node (ref "U101") (pin "6") (pinfunction "A3_6") (pintype "bidirectional"))
      (node (ref "U300") (pin "10") (pinfunction "A20_10") (pintype "unspecified"))
    )
    (net (code "22") (name "A21") (class "Default")
      (node (ref "U101") (pin "5") (pinfunction "A2_5") (pintype "bidirectional"))
      (node (ref "U300") (pin "11") (pinfunction "A21_11") (pintype "unspecified"))
    )
    (net (code "23") (name "A22") (class "Default")
      (node (ref "U101") (pin "4") (pinfunction "A1_4") (pintype "bidirectional"))
      (node (ref "U300") (pin "12") (pinfunction "A22_12") (pintype "unspecified"))
    )
    (net (code "24") (name "A23") (class "Default")
      (node (ref "U101") (pin "3") (pinfunction "A0_3") (pintype "bidirectional"))
      (node (ref "U203") (pin "2") (pinfunction "CLK/I_2") (pintype "unspecified"))
      (node (ref "U300") (pin "13") (pinfunction "A23_13") (pintype "unspecified"))
    )
    (net (code "25") (name "A24") (class "Default")
      (node (ref "U100") (pin "10") (pinfunction "A7_10") (pintype "bidirectional"))
      (node (ref "U201") (pin "17") (pinfunction "A7_17") (pintype "unspecified"))
      (node (ref "U300") (pin "14") (pinfunction "A24_14") (pintype "unspecified"))
    )
    (net (code "26") (name "A25") (class "Default")
      (node (ref "U100") (pin "9") (pinfunction "A6_9") (pintype "bidirectional"))
      (node (ref "U201") (pin "15") (pinfunction "A6_15") (pintype "unspecified"))
      (node (ref "U300") (pin "16") (pinfunction "A25_16") (pintype "unspecified"))
    )
    (net (code "27") (name "A26") (class "Default")
      (node (ref "U100") (pin "8") (pinfunction "A5_8") (pintype "bidirectional"))
      (node (ref "U201") (pin "13") (pinfunction "A5_13") (pintype "unspecified"))
      (node (ref "U300") (pin "17") (pinfunction "A26_17") (pintype "unspecified"))
    )
    (net (code "28") (name "A27") (class "Default")
      (node (ref "U100") (pin "7") (pinfunction "A4_7") (pintype "bidirectional"))
      (node (ref "U201") (pin "11") (pinfunction "A4_11") (pintype "unspecified"))
      (node (ref "U300") (pin "18") (pinfunction "A27_18") (pintype "unspecified"))
    )
    (net (code "29") (name "A28") (class "Default")
      (node (ref "U100") (pin "6") (pinfunction "A3_6") (pintype "bidirectional"))
      (node (ref "U201") (pin "8") (pinfunction "A3_8") (pintype "unspecified"))
      (node (ref "U300") (pin "20") (pinfunction "A28_20") (pintype "unspecified"))
    )
    (net (code "30") (name "A29") (class "Default")
      (node (ref "U100") (pin "5") (pinfunction "A2_5") (pintype "bidirectional"))
      (node (ref "U201") (pin "6") (pinfunction "A2_6") (pintype "unspecified"))
      (node (ref "U300") (pin "21") (pinfunction "A29_21") (pintype "unspecified"))
    )
    (net (code "31") (name "A30") (class "Default")
      (node (ref "U100") (pin "4") (pinfunction "A1_4") (pintype "bidirectional"))
      (node (ref "U201") (pin "4") (pinfunction "A1_4") (pintype "unspecified"))
      (node (ref "U300") (pin "23") (pinfunction "A30_23") (pintype "unspecified"))
    )
    (net (code "32") (name "A31") (class "Default")
      (node (ref "U100") (pin "3") (pinfunction "A0_3") (pintype "bidirectional"))
      (node (ref "U201") (pin "2") (pinfunction "A0_2") (pintype "unspecified"))
      (node (ref "U300") (pin "24") (pinfunction "A31_24") (pintype "unspecified"))
    )
    (net (code "33") (name "ABOEH") (class "Default")
      (node (ref "U100") (pin "13") (pinfunction "OEAB_13") (pintype "unspecified"))
      (node (ref "U100") (pin "2") (pinfunction "OEBA_2") (pintype "unspecified"))
      (node (ref "U101") (pin "13") (pinfunction "OEAB_13") (pintype "unspecified"))
      (node (ref "U101") (pin "2") (pinfunction "OEBA_2") (pintype "unspecified"))
      (node (ref "U102") (pin "13") (pinfunction "OEAB_13") (pintype "unspecified"))
      (node (ref "U102") (pin "2") (pinfunction "OEBA_2") (pintype "unspecified"))
      (node (ref "U205") (pin "27") (pinfunction "IOQ_27") (pintype "unspecified"))
      (node (ref "U306") (pin "10") (pinfunction "I_10") (pintype "unspecified"))
    )
    (net (code "34") (name "ABOEL") (class "Default")
      (node (ref "U103") (pin "19") (pinfunction "OE#_19") (pintype "unspecified"))
      (node (ref "U109") (pin "19") (pinfunction "OE#_19") (pintype "unspecified"))
      (node (ref "U205") (pin "26") (pinfunction "IOQ_26") (pintype "unspecified"))
    )
    (net (code "35") (name "BERR") (class "Default")
      (node (ref "R307B") (pin "2") (pinfunction "2_2") (pintype "input"))
      (node (ref "U202") (pin "17") (pinfunction "IOQ_17") (pintype "unspecified"))
      (node (ref "U300") (pin "37") (pinfunction "BERR/-TEA/_37") (pintype "unspecified"))
      (node (ref "U303") (pin "10") (pinfunction "I_10") (pintype "unspecified"))
      (node (ref "U306") (pin "11") (pinfunction "I_11") (pintype "unspecified"))
      (node (ref "U307") (pin "6") (pinfunction "3Y_6") (pintype "unspecified"))
    )
    (net (code "36") (name "BGACK") (class "Default")
      (node (ref "R300A") (pin "1") (pinfunction "1_1") (pintype "input"))
      (node (ref "U300") (pin "98") (pinfunction "BGACK/-BB/_98") (pintype "unspecified"))
    )
    (net (code "37") (name "BMASTER") (class "Default")
      (node (ref "U100") (pin "23") (pinfunction "CEBA_23") (pintype "unspecified"))
      (node (ref "U101") (pin "23") (pinfunction "CEBA_23") (pintype "unspecified"))
      (node (ref "U102") (pin "23") (pinfunction "CEBA_23") (pintype "unspecified"))
      (node (ref "U103") (pin "1") (pinfunction "T/R#_1") (pintype "unspecified"))
      (node (ref "U109") (pin "1") (pinfunction "T/R#_1") (pintype "unspecified"))
      (node (ref "U303") (pin "27") (pinfunction "IOQ_27") (pintype "unspecified"))
    )
    (net (code "38") (name "CBACK") (class "Default")
      (node (ref "R300B") (pin "2") (pinfunction "2_2") (pintype "input"))
      (node (ref "U300") (pin "35") (pinfunction "CBACK/-TBI/_35") (pintype "unspecified"))
      (node (ref "U306") (pin "27") (pinfunction "IOQ_27") (pintype "unspecified"))
    )
    (net (code "39") (name "CBREQ") (class "Default")
      (node (ref "R300C") (pin "1") (pinfunction "1_1") (pintype "input"))
      (node (ref "U300") (pin "33") (pinfunction "CBREQ/-TT1/_33") (pintype "unspecified"))
      (node (ref "U306") (pin "6") (pinfunction "I_6") (pintype "unspecified"))
    )
    (net (code "40") (name "CLK") (class "Default")
      (node (ref "R302B") (pin "1") (pinfunction "1_1") (pintype "input"))
      (node (ref "U205") (pin "2") (pinfunction "CLK/I_2") (pintype "unspecified"))
      (node (ref "U207") (pin "2") (pinfunction "CLK/I_2") (pintype "unspecified"))
      (node (ref "U300") (pin "41") (pinfunction "BCLK_41") (pintype "unspecified"))
      (node (ref "U303") (pin "12") (pinfunction "I_12") (pintype "unspecified"))
      (node (ref "U305") (pin "2") (pinfunction "CLK/I_2") (pintype "unspecified"))
    )
    (net (code "41") (name "CLKI") (class "Default")
      (node (ref "R302A") (pin "1") (pinfunction "1_1") (pintype "input"))
      (node (ref "U302") (pin "2") (pinfunction "D0_2") (pintype "unspecified"))
      (node (ref "U304") (pin "2") (pinfunction "CLK/I_2") (pintype "unspecified"))
      (node (ref "U306") (pin "2") (pinfunction "CLK/I_2") (pintype "unspecified"))
    )
    (net (code "42") (name "CLK_50M") (class "Default")
      (node (ref "R301A") (pin "1") (pinfunction "1_1") (pintype "input"))
      (node (ref "U300") (pin "102") (pinfunction "SCLK_102") (pintype "unspecified"))
      (node (ref "U302") (pin "3") (pinfunction "CP0_3") (pintype "unspecified"))
    )
    (net (code "43") (name "D0") (class "Default")
      (node (ref "U107") (pin "10") (pinfunction "A7_10") (pintype "bidirectional"))
      (node (ref "U204") (pin "18") (pinfunction "D7_18") (pintype "unspecified"))
      (node (ref "U204") (pin "19") (pinfunction "Q7_19") (pintype "unspecified"))
      (node (ref "U213") (pin "3") (pinfunction "O4_3") (pintype "unspecified"))
      (node (ref "U300") (pin "85") (pinfunction "D0_85") (pintype "unspecified"))
    )
    (net (code "44") (name "D1") (class "Default")
      (node (ref "U107") (pin "9") (pinfunction "A6_9") (pintype "bidirectional"))
      (node (ref "U204") (pin "16") (pinfunction "Q6_16") (pintype "unspecified"))
      (node (ref "U204") (pin "17") (pinfunction "D6_17") (pintype "unspecified"))
      (node (ref "U213") (pin "5") (pinfunction "O5_5") (pintype "unspecified"))
      (node (ref "U300") (pin "84") (pinfunction "D1_84") (pintype "unspecified"))
    )
    (net (code "45") (name "D2") (class "Default")
      (node (ref "U107") (pin "8") (pinfunction "A5_8") (pintype "bidirectional"))
      (node (ref "U204") (pin "14") (pinfunction "D5_14") (pintype "unspecified"))
      (node (ref "U204") (pin "15") (pinfunction "Q5_15") (pintype "unspecified"))
      (node (ref "U213") (pin "7") (pinfunction "O6_7") (pintype "unspecified"))
      (node (ref "U300") (pin "83") (pinfunction "D2_83") (pintype "unspecified"))
    )
    (net (code "46") (name "D2Z") (class "Default")
      (node (ref "U105") (pin "11") (pinfunction "CEAB_11") (pintype "unspecified"))
      (node (ref "U106") (pin "11") (pinfunction "CEAB_11") (pintype "unspecified"))
      (node (ref "U107") (pin "11") (pinfunction "CEAB_11") (pintype "unspecified"))
      (node (ref "U108") (pin "11") (pinfunction "CEAB_11") (pintype "unspecified"))
      (node (ref "U205") (pin "21") (pinfunction "IOQ_21") (pintype "unspecified"))
    )
    (net (code "47") (name "D3") (class "Default")
      (node (ref "U107") (pin "7") (pinfunction "A4_7") (pintype "bidirectional"))
      (node (ref "U204") (pin "12") (pinfunction "Q4_12") (pintype "unspecified"))
      (node (ref "U204") (pin "13") (pinfunction "D4_13") (pintype "unspecified"))
      (node (ref "U213") (pin "9") (pinfunction "O7_9") (pintype "unspecified"))
      (node (ref "U300") (pin "81") (pinfunction "D3_81") (pintype "unspecified"))
    )
    (net (code "48") (name "D4") (class "Default")
      (node (ref "U107") (pin "6") (pinfunction "A3_6") (pintype "bidirectional"))
      (node (ref "U204") (pin "8") (pinfunction "D3_8") (pintype "unspecified"))
      (node (ref "U204") (pin "9") (pinfunction "Q3_9") (pintype "unspecified"))
      (node (ref "U213") (pin "12") (pinfunction "O3_12") (pintype "unspecified"))
      (node (ref "U300") (pin "80") (pinfunction "D4_80") (pintype "unspecified"))
    )
    (net (code "49") (name "D5") (class "Default")
      (node (ref "U107") (pin "5") (pinfunction "A2_5") (pintype "bidirectional"))
      (node (ref "U204") (pin "6") (pinfunction "Q2_6") (pintype "unspecified"))
      (node (ref "U204") (pin "7") (pinfunction "D2_7") (pintype "unspecified"))
      (node (ref "U213") (pin "14") (pinfunction "O2_14") (pintype "unspecified"))
      (node (ref "U300") (pin "78") (pinfunction "D5_78") (pintype "unspecified"))
    )
    (net (code "50") (name "D6") (class "Default")
      (node (ref "U107") (pin "4") (pinfunction "A1_4") (pintype "bidirectional"))
      (node (ref "U204") (pin "4") (pinfunction "D1_4") (pintype "unspecified"))
      (node (ref "U204") (pin "5") (pinfunction "Q1_5") (pintype "unspecified"))
      (node (ref "U213") (pin "16") (pinfunction "O1_16") (pintype "unspecified"))
      (node (ref "U300") (pin "77") (pinfunction "D6_77") (pintype "unspecified"))
    )
    (net (code "51") (name "D7") (class "Default")
      (node (ref "U107") (pin "3") (pinfunction "A0_3") (pintype "bidirectional"))
      (node (ref "U204") (pin "2") (pinfunction "Q0_2") (pintype "unspecified"))
      (node (ref "U204") (pin "3") (pinfunction "D0_3") (pintype "unspecified"))
      (node (ref "U213") (pin "18") (pinfunction "O0_18") (pintype "unspecified"))
      (node (ref "U300") (pin "76") (pinfunction "D7_76") (pintype "unspecified"))
    )
    (net (code "52") (name "D8") (class "Default")
      (node (ref "U106") (pin "10") (pinfunction "A7_10") (pintype "bidirectional"))
      (node (ref "U300") (pin "73") (pinfunction "D8_73") (pintype "unspecified"))
    )
    (net (code "53") (name "D9") (class "Default")
      (node (ref "U106") (pin "9") (pinfunction "A6_9") (pintype "bidirectional"))
      (node (ref "U300") (pin "72") (pinfunction "D9_72") (pintype "unspecified"))
    )
    (net (code "54") (name "D10") (class "Default")
      (node (ref "U106") (pin "8") (pinfunction "A5_8") (pintype "bidirectional"))
      (node (ref "U300") (pin "71") (pinfunction "D10_71") (pintype "unspecified"))
    )
    (net (code "55") (name "D11") (class "Default")
      (node (ref "U106") (pin "7") (pinfunction "A4_7") (pintype "bidirectional"))
      (node (ref "U300") (pin "70") (pinfunction "D11_70") (pintype "unspecified"))
    )
    (net (code "56") (name "D12") (class "Default")
      (node (ref "U106") (pin "6") (pinfunction "A3_6") (pintype "bidirectional"))
      (node (ref "U206") (pin "11") (pinfunction "D0_11") (pintype "input"))
      (node (ref "U300") (pin "68") (pinfunction "D12_68") (pintype "unspecified"))
    )
    (net (code "57") (name "D13") (class "Default")
      (node (ref "U106") (pin "5") (pinfunction "A2_5") (pintype "bidirectional"))
      (node (ref "U206") (pin "12") (pinfunction "D1_12") (pintype "passive"))
      (node (ref "U300") (pin "67") (pinfunction "D13_67") (pintype "unspecified"))
    )
    (net (code "58") (name "D14") (class "Default")
      (node (ref "U106") (pin "4") (pinfunction "A1_4") (pintype "bidirectional"))
      (node (ref "U206") (pin "13") (pinfunction "D2_13") (pintype "input"))
      (node (ref "U300") (pin "66") (pinfunction "D14_66") (pintype "unspecified"))
    )
    (net (code "59") (name "D15") (class "Default")
      (node (ref "U106") (pin "3") (pinfunction "A0_3") (pintype "bidirectional"))
      (node (ref "U206") (pin "15") (pinfunction "D3_15") (pintype "output"))
      (node (ref "U300") (pin "65") (pinfunction "D15_65") (pintype "unspecified"))
    )
    (net (code "60") (name "D16") (class "Default")
      (node (ref "U108") (pin "3") (pinfunction "A0_3") (pintype "bidirectional"))
      (node (ref "U300") (pin "62") (pinfunction "D16_62") (pintype "unspecified"))
    )
    (net (code "61") (name "D17") (class "Default")
      (node (ref "U108") (pin "4") (pinfunction "A1_4") (pintype "bidirectional"))
      (node (ref "U300") (pin "60") (pinfunction "D17_60") (pintype "unspecified"))
    )
    (net (code "62") (name "D18") (class "Default")
      (node (ref "U108") (pin "5") (pinfunction "A2_5") (pintype "bidirectional"))
      (node (ref "U300") (pin "59") (pinfunction "D18_59") (pintype "unspecified"))
    )
    (net (code "63") (name "D19") (class "Default")
      (node (ref "U108") (pin "6") (pinfunction "A3_6") (pintype "bidirectional"))
      (node (ref "U300") (pin "58") (pinfunction "D19_58") (pintype "unspecified"))
    )
    (net (code "64") (name "D20") (class "Default")
      (node (ref "U108") (pin "7") (pinfunction "A4_7") (pintype "bidirectional"))
      (node (ref "U300") (pin "57") (pinfunction "D20_57") (pintype "unspecified"))
    )
    (net (code "65") (name "D21") (class "Default")
      (node (ref "U108") (pin "8") (pinfunction "A5_8") (pintype "bidirectional"))
      (node (ref "U300") (pin "56") (pinfunction "D21_56") (pintype "unspecified"))
    )
    (net (code "66") (name "D22") (class "Default")
      (node (ref "U108") (pin "9") (pinfunction "A6_9") (pintype "bidirectional"))
      (node (ref "U300") (pin "55") (pinfunction "D22_55") (pintype "unspecified"))
    )
    (net (code "67") (name "D23") (class "Default")
      (node (ref "U108") (pin "10") (pinfunction "A7_10") (pintype "bidirectional"))
      (node (ref "U300") (pin "53") (pinfunction "D23_53") (pintype "unspecified"))
    )
    (net (code "68") (name "D24") (class "Default")
      (node (ref "U105") (pin "3") (pinfunction "A0_3") (pintype "bidirectional"))
      (node (ref "U200") (pin "18") (pinfunction "D7_18") (pintype "unspecified"))
      (node (ref "U300") (pin "51") (pinfunction "D24_51") (pintype "unspecified"))
    )
    (net (code "69") (name "D25") (class "Default")
      (node (ref "U105") (pin "4") (pinfunction "A1_4") (pintype "bidirectional"))
      (node (ref "U200") (pin "17") (pinfunction "D6_17") (pintype "unspecified"))
      (node (ref "U300") (pin "50") (pinfunction "D25_50") (pintype "unspecified"))
    )
    (net (code "70") (name "D26") (class "Default")
      (node (ref "U105") (pin "5") (pinfunction "A2_5") (pintype "bidirectional"))
      (node (ref "U200") (pin "14") (pinfunction "D5_14") (pintype "unspecified"))
      (node (ref "U300") (pin "48") (pinfunction "D26_48") (pintype "unspecified"))
    )
    (net (code "71") (name "D27") (class "Default")
      (node (ref "U105") (pin "6") (pinfunction "A3_6") (pintype "bidirectional"))
      (node (ref "U200") (pin "13") (pinfunction "D4_13") (pintype "unspecified"))
      (node (ref "U300") (pin "47") (pinfunction "D27_47") (pintype "unspecified"))
    )
    (net (code "72") (name "D28") (class "Default")
      (node (ref "U105") (pin "7") (pinfunction "A4_7") (pintype "bidirectional"))
      (node (ref "U200") (pin "8") (pinfunction "D3_8") (pintype "unspecified"))
      (node (ref "U206") (pin "16") (pinfunction "D4_16") (pintype "output"))
      (node (ref "U300") (pin "45") (pinfunction "D28_45") (pintype "unspecified"))
    )
    (net (code "73") (name "D29") (class "Default")
      (node (ref "U105") (pin "8") (pinfunction "A5_8") (pintype "bidirectional"))
      (node (ref "U200") (pin "7") (pinfunction "D2_7") (pintype "unspecified"))
      (node (ref "U206") (pin "17") (pinfunction "D5_17") (pintype "output"))
      (node (ref "U300") (pin "44") (pinfunction "D29_44") (pintype "unspecified"))
    )
    (net (code "74") (name "D30") (class "Default")
      (node (ref "U105") (pin "9") (pinfunction "A6_9") (pintype "bidirectional"))
      (node (ref "U200") (pin "4") (pinfunction "D1_4") (pintype "unspecified"))
      (node (ref "U206") (pin "18") (pinfunction "D6_18") (pintype "output"))
      (node (ref "U300") (pin "43") (pinfunction "D30_43") (pintype "unspecified"))
    )
    (net (code "75") (name "D31") (class "Default")
      (node (ref "U105") (pin "10") (pinfunction "A7_10") (pintype "bidirectional"))
      (node (ref "U200") (pin "3") (pinfunction "D0_3") (pintype "unspecified"))
      (node (ref "U206") (pin "19") (pinfunction "D7_19") (pintype "output"))
      (node (ref "U300") (pin "42") (pinfunction "D31_42") (pintype "unspecified"))
    )
    (net (code "76") (name "DBLT") (class "Default")
      (node (ref "U105") (pin "1") (pinfunction "LEBA_1") (pintype "unspecified"))
      (node (ref "U105") (pin "14") (pinfunction "LEAB_14") (pintype "unspecified"))
      (node (ref "U106") (pin "1") (pinfunction "LEBA_1") (pintype "unspecified"))
      (node (ref "U106") (pin "14") (pinfunction "LEAB_14") (pintype "unspecified"))
      (node (ref "U107") (pin "1") (pinfunction "LEBA_1") (pintype "unspecified"))
      (node (ref "U107") (pin "14") (pinfunction "LEAB_14") (pintype "unspecified"))
      (node (ref "U108") (pin "1") (pinfunction "LEBA_1") (pintype "unspecified"))
      (node (ref "U108") (pin "14") (pinfunction "LEAB_14") (pintype "unspecified"))
      (node (ref "U205") (pin "24") (pinfunction "IOQ_24") (pintype "unspecified"))
    )
    (net (code "77") (name "DBOE") (class "Default")
      (node (ref "FB505") (pin "2") (pinfunction "2_2") (pintype "unspecified"))
      (node (ref "U105") (pin "13") (pinfunction "OEAB_13") (pintype "unspecified"))
      (node (ref "U105") (pin "2") (pinfunction "OEBA_2") (pintype "unspecified"))
      (node (ref "U106") (pin "13") (pinfunction "OEAB_13") (pintype "unspecified"))
      (node (ref "U106") (pin "2") (pinfunction "OEBA_2") (pintype "unspecified"))
      (node (ref "U107") (pin "13") (pinfunction "OEAB_13") (pintype "unspecified"))
      (node (ref "U107") (pin "2") (pinfunction "OEBA_2") (pintype "unspecified"))
      (node (ref "U108") (pin "13") (pinfunction "OEAB_13") (pintype "unspecified"))
      (node (ref "U108") (pin "2") (pinfunction "OEBA_2") (pintype "unspecified"))
    )
    (net (code "78") (name "DIP_EXT_TERM") (class "Default")
      (node (ref "R212G") (pin "2") (pinfunction "2_2") (pintype "input"))
      (node (ref "SW1") (pin "7") (pinfunction "PIN7_7") (pintype "unspecified"))
      (node (ref "U213") (pin "4") (pinfunction "I1_4") (pintype "unspecified"))
      (node (ref "U310") (pin "16") (pinfunction "PD#_16") (pintype "unspecified"))
      (node (ref "U311") (pin "16") (pinfunction "PD#_16") (pintype "unspecified"))
    )
    (net (code "79") (name "DIP_LONG_SPINUP") (class "Default")
      (node (ref "R212E") (pin "2") (pinfunction "2_2") (pintype "input"))
      (node (ref "SW1") (pin "5") (pinfunction "PIN5_5") (pintype "unspecified"))
      (node (ref "U213") (pin "8") (pinfunction "I3_8") (pintype "unspecified"))
    )
    (net (code "80") (name "DIP_SCSI_ADR0") (class "Default")
      (node (ref "R212A") (pin "2") (pinfunction "2_2") (pintype "input"))
      (node (ref "SW1") (pin "1") (pinfunction "PIN1_1") (pintype "unspecified"))
      (node (ref "U213") (pin "17") (pinfunction "I4_17") (pintype "unspecified"))
    )
    (net (code "81") (name "DIP_SCSI_ADR1") (class "Default")
      (node (ref "R212B") (pin "1") (pinfunction "1_1") (pintype "input"))
      (node (ref "SW1") (pin "2") (pinfunction "PIN2_2") (pintype "unspecified"))
      (node (ref "U213") (pin "15") (pinfunction "I5_15") (pintype "unspecified"))
    )
    (net (code "82") (name "DIP_SCSI_ADR2") (class "Default")
      (node (ref "R212C") (pin "1") (pinfunction "1_1") (pintype "input"))
      (node (ref "SW1") (pin "3") (pinfunction "PIN3_3") (pintype "unspecified"))
      (node (ref "U213") (pin "13") (pinfunction "I6_13") (pintype "unspecified"))
    )
    (net (code "83") (name "DIP_SCSI_FAST") (class "Default")
      (node (ref "R212D") (pin "1") (pinfunction "1_1") (pintype "input"))
      (node (ref "SW1") (pin "4") (pinfunction "PIN4_4") (pintype "unspecified"))
      (node (ref "U213") (pin "11") (pinfunction "I7_11") (pintype "unspecified"))
    )
    (net (code "84") (name "DIP_SCSI_LUNS") (class "Default")
      (node (ref "R212H") (pin "2") (pinfunction "2_2") (pintype "input"))
      (node (ref "SW1") (pin "8") (pinfunction "PIN8_8") (pintype "unspecified"))
      (node (ref "U213") (pin "2") (pinfunction "I0_2") (pintype "unspecified"))
    )
    (net (code "85") (name "DIP_SYNCH_MODE") (class "Default")
      (node (ref "R212F") (pin "2") (pinfunction "2_2") (pintype "input"))
      (node (ref "SW1") (pin "6") (pinfunction "PIN6_6") (pintype "unspecified"))
      (node (ref "U213") (pin "6") (pinfunction "I2_6") (pintype "unspecified"))
    )
    (net (code "86") (name "DP3_ABRT") (class "Default")
      (node (ref "R300P") (pin "1") (pinfunction "1_1") (pintype "input"))
      (node (ref "U300") (pin "52") (pinfunction "DP3_ABRT/_52") (pintype "unspecified"))
    )
    (net (code "87") (name "GND") (class "Default")
      (node (ref "C1") (pin "01") (pinfunction "GND_01") (pintype "bidirectional"))
      (node (ref "C1") (pin "02") (pinfunction "GND_02") (pintype "unspecified"))
      (node (ref "C1") (pin "03") (pinfunction "GND_03") (pintype "output"))
      (node (ref "C1") (pin "04") (pinfunction "GND_04") (pintype "bidirectional"))
      (node (ref "C1") (pin "100") (pinfunction "GND_100") (pintype "bidirectional"))
      (node (ref "C1") (pin "13") (pinfunction "GND_13") (pintype "bidirectional"))
      (node (ref "C1") (pin "25") (pinfunction "GND_25") (pintype "output"))
      (node (ref "C1") (pin "37") (pinfunction "GND_37") (pintype "unspecified"))
      (node (ref "C1") (pin "49") (pinfunction "GND_49") (pintype "unspecified"))
      (node (ref "C1") (pin "61") (pinfunction "GND_61") (pintype "bidirectional"))
      (node (ref "C1") (pin "73") (pinfunction "GND_73") (pintype "unspecified"))
      (node (ref "C1") (pin "85") (pinfunction "GND_85") (pintype "unspecified"))
      (node (ref "C1") (pin "87") (pinfunction "GND_87") (pintype "output"))
      (node (ref "C1") (pin "88") (pinfunction "GND_88") (pintype "bidirectional"))
      (node (ref "C1") (pin "89") (pinfunction "GND_89") (pintype "unspecified"))
      (node (ref "C1") (pin "90") (pinfunction "GND_90") (pintype "bidirectional"))
      (node (ref "C1") (pin "99") (pinfunction "GND_99") (pintype "bidirectional"))
      (node (ref "C10") (pin "2") (pinfunction "2_2") (pintype "input"))
      (node (ref "C100A") (pin "2") (pinfunction "2_2") (pintype "input"))
      (node (ref "C101A") (pin "2") (pinfunction "2_2") (pintype "input"))
      (node (ref "C102A") (pin "2") (pinfunction "2_2") (pintype "input"))
      (node (ref "C103A") (pin "2") (pinfunction "2_2") (pintype "input"))
      (node (ref "C105A") (pin "2") (pinfunction "2_2") (pintype "input"))
      (node (ref "C106A") (pin "1") (pinfunction "1_1") (pintype "input"))
      (node (ref "C107A") (pin "2") (pinfunction "2_2") (pintype "input"))
      (node (ref "C108A") (pin "2") (pinfunction "2_2") (pintype "input"))
      (node (ref "C109A") (pin "2") (pinfunction "2_2") (pintype "input"))
      (node (ref "C11") (pin "2") (pinfunction "2_2") (pintype "input"))
      (node (ref "C12") (pin "2") (pinfunction "2_2") (pintype "input"))
      (node (ref "C13") (pin "2") (pinfunction "2_2") (pintype "input"))
      (node (ref "C1A") (pin "1") (pinfunction "1_1") (pintype "input"))
      (node (ref "C1B") (pin "2") (pinfunction "2_2") (pintype "input"))
      (node (ref "C1C") (pin "2") (pinfunction "2_2") (pintype "input"))
      (node (ref "C200A") (pin "1") (pinfunction "1_1") (pintype "input"))
      (node (ref "C201A") (pin "2") (pinfunction "2_2") (pintype "input"))
      (node (ref "C202A") (pin "2") (pinfunction "2_2") (pintype "input"))
      (node (ref "C203A") (pin "2") (pinfunction "2_2") (pintype "input"))
      (node (ref "C204A") (pin "1") (pinfunction "1_1") (pintype "input"))
      (node (ref "C205A") (pin "2") (pinfunction "2_2") (pintype "input"))
      (node (ref "C206A") (pin "1") (pinfunction "1_1") (pintype "input"))
      (node (ref "C207A") (pin "2") (pinfunction "2_2") (pintype "input"))
      (node (ref "C212A") (pin "2") (pinfunction "2_2") (pintype "input"))
      (node (ref "C300A") (pin "2") (pinfunction "2_2") (pintype "input"))
      (node (ref "C300B") (pin "2") (pinfunction "2_2") (pintype "input"))
      (node (ref "C300C") (pin "2") (pinfunction "2_2") (pintype "input"))
      (node (ref "C300D") (pin "1") (pinfunction "1_1") (pintype "input"))
      (node (ref "C300E") (pin "2") (pinfunction "2_2") (pintype "input"))
      (node (ref "C300F") (pin "2") (pinfunction "2_2") (pintype "input"))
      (node (ref "C300G") (pin "2") (pinfunction "2_2") (pintype "input"))
      (node (ref "C300H") (pin "1") (pinfunction "1_1") (pintype "input"))
      (node (ref "C300I") (pin "2") (pinfunction "2_2") (pintype "input"))
      (node (ref "C301A") (pin "1") (pinfunction "1_1") (pintype "input"))
      (node (ref "C302A") (pin "2") (pinfunction "2_2") (pintype "input"))
      (node (ref "C303A") (pin "1") (pinfunction "1_1") (pintype "input"))
      (node (ref "C304A") (pin "2") (pinfunction "2_2") (pintype "input"))
      (node (ref "C305A") (pin "2") (pinfunction "2_2") (pintype "input"))
      (node (ref "C306A") (pin "2") (pinfunction "2_2") (pintype "input"))
      (node (ref "C306B") (pin "2") (pinfunction "2_2") (pintype "input"))
      (node (ref "C307A") (pin "1") (pinfunction "1_1") (pintype "input"))
      (node (ref "C310A") (pin "1") (pinfunction "1_1") (pintype "unspecified"))
      (node (ref "C310B") (pin "1") (pinfunction "1_1") (pintype "unspecified"))
      (node (ref "C310C") (pin "1") (pinfunction "1_1") (pintype "unspecified"))
      (node (ref "C310D") (pin "1") (pinfunction "1_1") (pintype "unspecified"))
      (node (ref "C310E") (pin "1") (pinfunction "1_1") (pintype "unspecified"))
      (node (ref "C310F") (pin "1") (pinfunction "1_1") (pintype "unspecified"))
      (node (ref "C310G") (pin "1") (pinfunction "1_1") (pintype "unspecified"))
      (node (ref "C310H") (pin "1") (pinfunction "1_1") (pintype "unspecified"))
      (node (ref "C310I") (pin "1") (pinfunction "1_1") (pintype "unspecified"))
      (node (ref "C310J") (pin "2") (pinfunction "2_2") (pintype "unspecified"))
      (node (ref "C310K") (pin "2") (pinfunction "2_2") (pintype "unspecified"))
      (node (ref "C310L") (pin "2") (pinfunction "2_2") (pintype "unspecified"))
      (node (ref "C310M") (pin "2") (pinfunction "2_2") (pintype "unspecified"))
      (node (ref "C310N") (pin "2") (pinfunction "2_2") (pintype "unspecified"))
      (node (ref "C310O") (pin "2") (pinfunction "2_2") (pintype "unspecified"))
      (node (ref "C310P") (pin "2") (pinfunction "2_2") (pintype "unspecified"))
      (node (ref "C310Q") (pin "2") (pinfunction "2_2") (pintype "unspecified"))
      (node (ref "C310R") (pin "2") (pinfunction "2_2") (pintype "unspecified"))
      (node (ref "C350A") (pin "2") (pinfunction "2_2") (pintype "unspecified"))
      (node (ref "C350B") (pin "1") (pinfunction "1_1") (pintype "input"))
      (node (ref "C351A") (pin "2") (pinfunction "2_2") (pintype "unspecified"))
      (node (ref "C351B") (pin "2") (pinfunction "2_2") (pintype "input"))
      (node (ref "CN2") (pin "2") (pinfunction "2_2") (pintype "unspecified"))
      (node (ref "CN2") (pin "3") (pinfunction "3_3") (pintype "unspecified"))
      (node (ref "CN3") (pin "2") (pinfunction "GND_2") (pintype "unspecified"))
      (node (ref "CN3") (pin "3") (pinfunction "GND_3") (pintype "unspecified"))
      (node (ref "CN309") (pin "1") (pinfunction "1_1") (pintype "unspecified"))
      (node (ref "CN309") (pin "11") (pinfunction "11_11") (pintype "unspecified"))
      (node (ref "CN309") (pin "13") (pinfunction "13_13") (pintype "unspecified"))
      (node (ref "CN309") (pin "15") (pinfunction "15_15") (pintype "unspecified"))
      (node (ref "CN309") (pin "17") (pinfunction "17_17") (pintype "unspecified"))
      (node (ref "CN309") (pin "19") (pinfunction "19_19") (pintype "unspecified"))
      (node (ref "CN309") (pin "20") (pinfunction "20_20") (pintype "unspecified"))
      (node (ref "CN309") (pin "21") (pinfunction "21_21") (pintype "unspecified"))
      (node (ref "CN309") (pin "22") (pinfunction "22_22") (pintype "unspecified"))
      (node (ref "CN309") (pin "23") (pinfunction "23_23") (pintype "unspecified"))
      (node (ref "CN309") (pin "24") (pinfunction "24_24") (pintype "unspecified"))
      (node (ref "CN309") (pin "27") (pinfunction "27_27") (pintype "unspecified"))
      (node (ref "CN309") (pin "28") (pinfunction "28_28") (pintype "unspecified"))
      (node (ref "CN309") (pin "29") (pinfunction "29_29") (pintype "unspecified"))
      (node (ref "CN309") (pin "3") (pinfunction "3_3") (pintype "unspecified"))
      (node (ref "CN309") (pin "30") (pinfunction "30_30") (pintype "unspecified"))
      (node (ref "CN309") (pin "31") (pinfunction "31_31") (pintype "unspecified"))
      (node (ref "CN309") (pin "33") (pinfunction "33_33") (pintype "unspecified"))
      (node (ref "CN309") (pin "35") (pinfunction "35_35") (pintype "unspecified"))
      (node (ref "CN309") (pin "37") (pinfunction "37_37") (pintype "unspecified"))
      (node (ref "CN309") (pin "39") (pinfunction "39_39") (pintype "unspecified"))
      (node (ref "CN309") (pin "41") (pinfunction "41_41") (pintype "unspecified"))
      (node (ref "CN309") (pin "43") (pinfunction "43_43") (pintype "unspecified"))
      (node (ref "CN309") (pin "45") (pinfunction "45_45") (pintype "unspecified"))
      (node (ref "CN309") (pin "47") (pinfunction "47_47") (pintype "unspecified"))
      (node (ref "CN309") (pin "49") (pinfunction "49_49") (pintype "unspecified"))
      (node (ref "CN309") (pin "5") (pinfunction "5_5") (pintype "unspecified"))
      (node (ref "CN309") (pin "7") (pinfunction "7_7") (pintype "unspecified"))
      (node (ref "CN309") (pin "9") (pinfunction "9_9") (pintype "unspecified"))
      (node (ref "CN310") (pin "1") (pinfunction "GND_1") (pintype "unspecified"))
      (node (ref "CN310") (pin "10") (pinfunction "GND_10") (pintype "unspecified"))
      (node (ref "CN310") (pin "11") (pinfunction "GND_11") (pintype "unspecified"))
      (node (ref "CN310") (pin "15") (pinfunction "GND_15") (pintype "unspecified"))
      (node (ref "CN310") (pin "16") (pinfunction "GND_16") (pintype "unspecified"))
      (node (ref "CN310") (pin "17") (pinfunction "GND_17") (pintype "unspecified"))
      (node (ref "CN310") (pin "18") (pinfunction "GND_18") (pintype "unspecified"))
      (node (ref "CN310") (pin "19") (pinfunction "GND_19") (pintype "unspecified"))
      (node (ref "CN310") (pin "2") (pinfunction "GND_2") (pintype "unspecified"))
      (node (ref "CN310") (pin "20") (pinfunction "GND_20") (pintype "unspecified"))
      (node (ref "CN310") (pin "21") (pinfunction "GND_21") (pintype "unspecified"))
      (node (ref "CN310") (pin "22") (pinfunction "GND_22") (pintype "unspecified"))
      (node (ref "CN310") (pin "23") (pinfunction "GND_23") (pintype "unspecified"))
      (node (ref "CN310") (pin "24") (pinfunction "GND_24") (pintype "unspecified"))
      (node (ref "CN310") (pin "25") (pinfunction "GND_25") (pintype "unspecified"))
      (node (ref "CN310") (pin "3") (pinfunction "GND_3") (pintype "unspecified"))
      (node (ref "CN310") (pin "35") (pinfunction "GND_35") (pintype "unspecified"))
      (node (ref "CN310") (pin "36") (pinfunction "GND_36") (pintype "unspecified"))
      (node (ref "CN310") (pin "4") (pinfunction "GND_4") (pintype "unspecified"))
      (node (ref "CN310") (pin "40") (pinfunction "GND_40") (pintype "unspecified"))
      (node (ref "CN310") (pin "42") (pinfunction "GND_42") (pintype "unspecified"))
      (node (ref "CN310") (pin "5") (pinfunction "GND_5") (pintype "unspecified"))
      (node (ref "CN310") (pin "6") (pinfunction "GND_6") (pintype "unspecified"))
      (node (ref "CN310") (pin "7") (pinfunction "GND_7") (pintype "unspecified"))
      (node (ref "CN310") (pin "8") (pinfunction "GND_8") (pintype "unspecified"))
      (node (ref "CN310") (pin "9") (pinfunction "GND_9") (pintype "unspecified"))
      (node (ref "CN4") (pin "3") (pinfunction "3_3") (pintype "unspecified"))
      (node (ref "MH1") (pin "1") (pinfunction "1_1") (pintype "unspecified"))
      (node (ref "MH2") (pin "1") (pinfunction "1_1") (pintype "unspecified"))
      (node (ref "MH3") (pin "1") (pinfunction "1_1") (pintype "unspecified"))
      (node (ref "MH4") (pin "1") (pinfunction "1_1") (pintype "unspecified"))
      (node (ref "R109H") (pin "1") (pinfunction "1_1") (pintype "input"))
      (node (ref "RP300A") (pin "1") (pinfunction "COM1_1") (pintype "unspecified"))
      (node (ref "RP300B") (pin "1") (pinfunction "COM1_1") (pintype "unspecified"))
      (node (ref "RP300C") (pin "1") (pinfunction "COM1_1") (pintype "unspecified"))
      (node (ref "SW1") (pin "10") (pinfunction "PIN10_10") (pintype "unspecified"))
      (node (ref "SW1") (pin "11") (pinfunction "PIN11_11") (pintype "unspecified"))
      (node (ref "SW1") (pin "12") (pinfunction "PIN12_12") (pintype "unspecified"))
      (node (ref "SW1") (pin "13") (pinfunction "PIN13_13") (pintype "unspecified"))
      (node (ref "SW1") (pin "14") (pinfunction "PIN14_14") (pintype "unspecified"))
      (node (ref "SW1") (pin "15") (pinfunction "PIN15_15") (pintype "unspecified"))
      (node (ref "SW1") (pin "16") (pinfunction "PIN16_16") (pintype "unspecified"))
      (node (ref "SW1") (pin "9") (pinfunction "PIN9_9") (pintype "unspecified"))
      (node (ref "U100") (pin "12") (pinfunction "GND_12") (pintype "passive"))
      (node (ref "U100") (pin "14") (pinfunction "LEAB_14") (pintype "unspecified"))
      (node (ref "U101") (pin "12") (pinfunction "GND_12") (pintype "passive"))
      (node (ref "U101") (pin "14") (pinfunction "LEAB_14") (pintype "unspecified"))
      (node (ref "U102") (pin "12") (pinfunction "GND_12") (pintype "passive"))
      (node (ref "U102") (pin "14") (pinfunction "LEAB_14") (pintype "unspecified"))
      (node (ref "U103") (pin "10") (pinfunction "GND_10") (pintype "unspecified"))
      (node (ref "U105") (pin "12") (pinfunction "GND_12") (pintype "passive"))
      (node (ref "U106") (pin "12") (pinfunction "GND_12") (pintype "passive"))
      (node (ref "U107") (pin "12") (pinfunction "GND_12") (pintype "passive"))
      (node (ref "U108") (pin "12") (pinfunction "GND_12") (pintype "passive"))
      (node (ref "U109") (pin "10") (pinfunction "GND_10") (pintype "unspecified"))
      (node (ref "U200") (pin "10") (pinfunction "GND_10") (pintype "unspecified"))
      (node (ref "U201") (pin "1") (pinfunction "IA=B_1") (pintype "unspecified"))
      (node (ref "U201") (pin "10") (pinfunction "GND_10") (pintype "unspecified"))
      (node (ref "U202") (pin "14") (pinfunction "GND_14") (pintype "unspecified"))
      (node (ref "U203") (pin "14") (pinfunction "GND_14") (pintype "unspecified"))
      (node (ref "U204") (pin "10") (pinfunction "GND_10") (pintype "unspecified"))
      (node (ref "U205") (pin "14") (pinfunction "GND_14") (pintype "unspecified"))
      (node (ref "U206") (pin "14") (pinfunction "GND_14") (pintype "output"))
      (node (ref "U206") (pin "20") (pinfunction "CE#_20") (pintype "output"))
      (node (ref "U207") (pin "14") (pinfunction "GND_14") (pintype "unspecified"))
      (node (ref "U213") (pin "10") (pinfunction "GND_10") (pintype "unspecified"))
      (node (ref "U300") (pin "109") (pinfunction "Vss_109") (pintype "unspecified"))
      (node (ref "U300") (pin "113") (pinfunction "Vss_113") (pintype "unspecified"))
      (node (ref "U300") (pin "118") (pinfunction "Vss_118") (pintype "unspecified"))
      (node (ref "U300") (pin "123") (pinfunction "Vss_123") (pintype "unspecified"))
      (node (ref "U300") (pin "128") (pinfunction "Vss_128") (pintype "unspecified"))
      (node (ref "U300") (pin "136") (pinfunction "Vss_136") (pintype "unspecified"))
      (node (ref "U300") (pin "143") (pinfunction "Vss_143") (pintype "unspecified"))
      (node (ref "U300") (pin "149") (pinfunction "Vss_149") (pintype "unspecified"))
      (node (ref "U300") (pin "15") (pinfunction "Vss_15") (pintype "unspecified"))
      (node (ref "U300") (pin "156") (pinfunction "Vss_156") (pintype "unspecified"))
      (node (ref "U300") (pin "2") (pinfunction "Vss_2") (pintype "unspecified"))
      (node (ref "U300") (pin "22") (pinfunction "Vss_22") (pintype "unspecified"))
      (node (ref "U300") (pin "31") (pinfunction "Vss_31") (pintype "unspecified"))
      (node (ref "U300") (pin "46") (pinfunction "Vss_46") (pintype "unspecified"))
      (node (ref "U300") (pin "54") (pinfunction "Vss_54") (pintype "unspecified"))
      (node (ref "U300") (pin "61") (pinfunction "Vss_61") (pintype "unspecified"))
      (node (ref "U300") (pin "69") (pinfunction "Vss_69") (pintype "unspecified"))
      (node (ref "U300") (pin "75") (pinfunction "Vss_75") (pintype "unspecified"))
      (node (ref "U300") (pin "82") (pinfunction "Vss_82") (pintype "unspecified"))
      (node (ref "U300") (pin "9") (pinfunction "Vss_9") (pintype "unspecified"))
      (node (ref "U300") (pin "96") (pinfunction "Vss_96") (pintype "unspecified"))
      (node (ref "U301") (pin "7") (pinfunction "Gnd_7") (pintype "unspecified"))
      (node (ref "U302") (pin "7") (pinfunction "GND_7") (pintype "unspecified"))
      (node (ref "U303") (pin "14") (pinfunction "GND_14") (pintype "unspecified"))
      (node (ref "U304") (pin "14") (pinfunction "GND_14") (pintype "unspecified"))
      (node (ref "U305") (pin "14") (pinfunction "GND_14") (pintype "unspecified"))
      (node (ref "U306") (pin "14") (pinfunction "GND_14") (pintype "unspecified"))
      (node (ref "U307") (pin "11") (pinfunction "5A_11") (pintype "unspecified"))
      (node (ref "U307") (pin "13") (pinfunction "6A_13") (pintype "unspecified"))
      (node (ref "U307") (pin "7") (pinfunction "GND_7") (pintype "unspecified"))
      (node (ref "U310") (pin "8") (pinfunction "GND_8") (pintype "passive"))
      (node (ref "U311") (pin "8") (pinfunction "GND_8") (pintype "passive"))
    )
    (net (code "88") (name "IORST") (class "Default")
      (node (ref "R307A") (pin "1") (pinfunction "1_1") (pintype "input"))
      (node (ref "U202") (pin "19") (pinfunction "IOQ_19") (pintype "unspecified"))
      (node (ref "U203") (pin "27") (pinfunction "IOQ_27") (pintype "unspecified"))
      (node (ref "U207") (pin "9") (pinfunction "I_9") (pintype "unspecified"))
      (node (ref "U300") (pin "94") (pinfunction "RESET/_94") (pintype "unspecified"))
      (node (ref "U303") (pin "11") (pinfunction "I_11") (pintype "unspecified"))
      (node (ref "U306") (pin "12") (pinfunction "I_12") (pintype "unspecified"))
      (node (ref "U307") (pin "8") (pinfunction "4Y_8") (pintype "unspecified"))
    )
    (net (code "89") (name "LED") (class "Default")
      (node (ref "R398") (pin "2") (pinfunction "2_2") (pintype "unspecified"))
      (node (ref "U307") (pin "2") (pinfunction "1Y_2") (pintype "unspecified"))
      (node (ref "U307") (pin "4") (pinfunction "2Y_4") (pintype "unspecified"))
    )
    (net (code "90") (name "LEDR") (class "Default")
      (node (ref "CN308") (pin "1") (pinfunction "1_1") (pintype "input"))
      (node (ref "CN308") (pin "3") (pinfunction "3_3") (pintype "input"))
      (node (ref "CN351") (pin "1") (pinfunction "1_1") (pintype "input"))
      (node (ref "CN351") (pin "3") (pinfunction "3_3") (pintype "input"))
      (node (ref "R398") (pin "1") (pinfunction "1_1") (pintype "unspecified"))
    )
    (net (code "91") (name "M24") (class "Default")
      (node (ref "R200H") (pin "1") (pinfunction "1_1") (pintype "input"))
      (node (ref "U200") (pin "19") (pinfunction "Q7_19") (pintype "unspecified"))
      (node (ref "U201") (pin "18") (pinfunction "B7_18") (pintype "unspecified"))
    )
    (net (code "92") (name "M25") (class "Default")
      (node (ref "R200G") (pin "1") (pinfunction "1_1") (pintype "input"))
      (node (ref "U200") (pin "16") (pinfunction "Q6_16") (pintype "unspecified"))
      (node (ref "U201") (pin "16") (pinfunction "B6_16") (pintype "unspecified"))
    )
    (net (code "93") (name "M26") (class "Default")
      (node (ref "R200F") (pin "1") (pinfunction "1_1") (pintype "input"))
      (node (ref "U200") (pin "15") (pinfunction "Q5_15") (pintype "unspecified"))
      (node (ref "U201") (pin "14") (pinfunction "B5_14") (pintype "unspecified"))
    )
    (net (code "94") (name "M27") (class "Default")
      (node (ref "R200E") (pin "1") (pinfunction "1_1") (pintype "input"))
      (node (ref "U200") (pin "12") (pinfunction "Q4_12") (pintype "unspecified"))
      (node (ref "U201") (pin "12") (pinfunction "B4_12") (pintype "unspecified"))
    )
    (net (code "95") (name "M28") (class "Default")
      (node (ref "R200D") (pin "1") (pinfunction "1_1") (pintype "input"))
      (node (ref "U200") (pin "9") (pinfunction "Q3_9") (pintype "unspecified"))
      (node (ref "U201") (pin "9") (pinfunction "B3_9") (pintype "unspecified"))
    )
    (net (code "96") (name "M29") (class "Default")
      (node (ref "R200C") (pin "1") (pinfunction "1_1") (pintype "input"))
      (node (ref "U200") (pin "6") (pinfunction "Q2_6") (pintype "unspecified"))
      (node (ref "U201") (pin "7") (pinfunction "B2_7") (pintype "unspecified"))
    )
    (net (code "97") (name "M30") (class "Default")
      (node (ref "R200B") (pin "1") (pinfunction "1_1") (pintype "input"))
      (node (ref "U200") (pin "5") (pinfunction "Q1_5") (pintype "unspecified"))
      (node (ref "U201") (pin "5") (pinfunction "B1_5") (pintype "unspecified"))
    )
    (net (code "98") (name "M31") (class "Default")
      (node (ref "R200A") (pin "1") (pinfunction "1_1") (pintype "input"))
      (node (ref "U200") (pin "2") (pinfunction "Q0_2") (pintype "unspecified"))
      (node (ref "U201") (pin "3") (pinfunction "B0_3") (pintype "unspecified"))
    )
    (net (code "99") (name "MASTER") (class "Default")
      (node (ref "FB502") (pin "1") (pinfunction "1_1") (pintype "unspecified"))
      (node (ref "U100") (pin "11") (pinfunction "CEAB_11") (pintype "unspecified"))
      (node (ref "U101") (pin "11") (pinfunction "CEAB_11") (pintype "unspecified"))
      (node (ref "U102") (pin "11") (pinfunction "CEAB_11") (pintype "unspecified"))
      (node (ref "U205") (pin "18") (pinfunction "IOQ_18") (pintype "unspecified"))
      (node (ref "U303") (pin "3") (pinfunction "I_3") (pintype "unspecified"))
    )
    (net (code "100") (name "MATCH") (class "Default")
      (node (ref "U201") (pin "19") (pinfunction "OA=B_19") (pintype "unspecified"))
      (node (ref "U202") (pin "2") (pinfunction "CLK/I_2") (pintype "unspecified"))
    )
    (net (code "101") (name "NCR_INT") (class "Default")
      (node (ref "U207") (pin "10") (pinfunction "I_10") (pintype "unspecified"))
      (node (ref "U300") (pin "105") (pinfunction "IRQ/_105") (pintype "unspecified"))
    )
    (net (code "102") (name "Net-(CN309-Pad2)") (class "Default")
      (node (ref "CN309") (pin "2") (pinfunction "2_2") (pintype "unspecified"))
      (node (ref "FB311A") (pin "1") (pinfunction "1_1") (pintype "unspecified"))
    )
    (net (code "103") (name "Net-(CN309-Pad4)") (class "Default")
      (node (ref "CN309") (pin "4") (pinfunction "4_4") (pintype "unspecified"))
      (node (ref "FB311B") (pin "1") (pinfunction "1_1") (pintype "unspecified"))
    )
    (net (code "104") (name "Net-(CN309-Pad6)") (class "Default")
      (node (ref "CN309") (pin "6") (pinfunction "6_6") (pintype "unspecified"))
      (node (ref "FB311C") (pin "1") (pinfunction "1_1") (pintype "unspecified"))
    )
    (net (code "105") (name "Net-(CN309-Pad8)") (class "Default")
      (node (ref "CN309") (pin "8") (pinfunction "8_8") (pintype "unspecified"))
      (node (ref "FB311D") (pin "1") (pinfunction "1_1") (pintype "unspecified"))
    )
    (net (code "106") (name "Net-(CN309-Pad10)") (class "Default")
      (node (ref "CN309") (pin "10") (pinfunction "10_10") (pintype "unspecified"))
      (node (ref "FB311E") (pin "1") (pinfunction "1_1") (pintype "unspecified"))
    )
    (net (code "107") (name "Net-(CN309-Pad12)") (class "Default")
      (node (ref "CN309") (pin "12") (pinfunction "12_12") (pintype "unspecified"))
      (node (ref "FB311F") (pin "1") (pinfunction "1_1") (pintype "unspecified"))
    )
    (net (code "108") (name "Net-(CN309-Pad14)") (class "Default")
      (node (ref "CN309") (pin "14") (pinfunction "14_14") (pintype "unspecified"))
      (node (ref "FB311G") (pin "1") (pinfunction "1_1") (pintype "unspecified"))
    )
    (net (code "109") (name "Net-(CN309-Pad16)") (class "Default")
      (node (ref "CN309") (pin "16") (pinfunction "16_16") (pintype "unspecified"))
      (node (ref "FB311H") (pin "1") (pinfunction "1_1") (pintype "unspecified"))
    )
    (net (code "110") (name "Net-(CN309-Pad18)") (class "Default")
      (node (ref "CN309") (pin "18") (pinfunction "18_18") (pintype "unspecified"))
      (node (ref "FB311I") (pin "1") (pinfunction "1_1") (pintype "unspecified"))
    )
    (net (code "111") (name "Net-(CN309-Pad32)") (class "Default")
      (node (ref "CN309") (pin "32") (pinfunction "32_32") (pintype "unspecified"))
      (node (ref "FB311J") (pin "1") (pinfunction "1_1") (pintype "unspecified"))
    )
    (net (code "112") (name "Net-(CN309-Pad38)") (class "Default")
      (node (ref "CN309") (pin "38") (pinfunction "38_38") (pintype "unspecified"))
      (node (ref "FB311Q") (pin "1") (pinfunction "1_1") (pintype "unspecified"))
    )
    (net (code "113") (name "Net-(CN309-Pad40)") (class "Default")
      (node (ref "CN309") (pin "40") (pinfunction "40_40") (pintype "unspecified"))
      (node (ref "FB311P") (pin "1") (pinfunction "1_1") (pintype "unspecified"))
    )
    (net (code "114") (name "Net-(CN309-Pad42)") (class "Default")
      (node (ref "CN309") (pin "42") (pinfunction "42_42") (pintype "unspecified"))
      (node (ref "FB311O") (pin "1") (pinfunction "1_1") (pintype "unspecified"))
    )
    (net (code "115") (name "Net-(CN309-Pad44)") (class "Default")
      (node (ref "CN309") (pin "44") (pinfunction "44_44") (pintype "unspecified"))
      (node (ref "FB311N") (pin "1") (pinfunction "1_1") (pintype "unspecified"))
    )
    (net (code "116") (name "Net-(CN309-Pad46)") (class "Default")
      (node (ref "CN309") (pin "46") (pinfunction "46_46") (pintype "unspecified"))
      (node (ref "FB311M") (pin "1") (pinfunction "1_1") (pintype "unspecified"))
    )
    (net (code "117") (name "Net-(CN309-Pad48)") (class "Default")
      (node (ref "CN309") (pin "48") (pinfunction "48_48") (pintype "unspecified"))
      (node (ref "FB311L") (pin "1") (pinfunction "1_1") (pintype "unspecified"))
    )
    (net (code "118") (name "Net-(CN309-Pad50)") (class "Default")
      (node (ref "CN309") (pin "50") (pinfunction "50_50") (pintype "unspecified"))
      (node (ref "FB311K") (pin "1") (pinfunction "1_1") (pintype "unspecified"))
    )
    (net (code "119") (name "Net-(CN310-ACK)") (class "Default")
      (node (ref "C310G") (pin "2") (pinfunction "2_2") (pintype "unspecified"))
      (node (ref "CN310") (pin "44") (pinfunction "ACK_44") (pintype "unspecified"))
      (node (ref "FB310G") (pin "2") (pinfunction "2_2") (pintype "unspecified"))
    )
    (net (code "120") (name "Net-(CN310-ATN)") (class "Default")
      (node (ref "C310I") (pin "2") (pinfunction "2_2") (pintype "unspecified"))
      (node (ref "CN310") (pin "41") (pinfunction "ATN_41") (pintype "unspecified"))
      (node (ref "FB310I") (pin "2") (pinfunction "2_2") (pintype "unspecified"))
    )
    (net (code "121") (name "Net-(CN310-BSY)") (class "Default")
      (node (ref "C310H") (pin "2") (pinfunction "2_2") (pintype "unspecified"))
      (node (ref "CN310") (pin "43") (pinfunction "BSY_43") (pintype "unspecified"))
      (node (ref "FB310H") (pin "2") (pinfunction "2_2") (pintype "unspecified"))
    )
    (net (code "122") (name "Net-(CN310-CD)") (class "Default")
      (node (ref "C310C") (pin "2") (pinfunction "2_2") (pintype "unspecified"))
      (node (ref "CN310") (pin "48") (pinfunction "CD_48") (pintype "unspecified"))
      (node (ref "FB310C") (pin "2") (pinfunction "2_2") (pintype "unspecified"))
    )
    (net (code "123") (name "Net-(CN310-D0)") (class "Default")
      (node (ref "C310K") (pin "1") (pinfunction "1_1") (pintype "unspecified"))
      (node (ref "CN310") (pin "26") (pinfunction "D0_26") (pintype "unspecified"))
      (node (ref "FB310K") (pin "2") (pinfunction "2_2") (pintype "unspecified"))
    )
    (net (code "124") (name "Net-(CN310-D1)") (class "Default")
      (node (ref "C310L") (pin "1") (pinfunction "1_1") (pintype "unspecified"))
      (node (ref "CN310") (pin "27") (pinfunction "D1_27") (pintype "unspecified"))
      (node (ref "FB310L") (pin "2") (pinfunction "2_2") (pintype "unspecified"))
    )
    (net (code "125") (name "Net-(CN310-D2)") (class "Default")
      (node (ref "C310M") (pin "1") (pinfunction "1_1") (pintype "unspecified"))
      (node (ref "CN310") (pin "28") (pinfunction "D2_28") (pintype "unspecified"))
      (node (ref "FB310M") (pin "2") (pinfunction "2_2") (pintype "unspecified"))
    )
    (net (code "126") (name "Net-(CN310-D3)") (class "Default")
      (node (ref "C310N") (pin "1") (pinfunction "1_1") (pintype "unspecified"))
      (node (ref "CN310") (pin "29") (pinfunction "D3_29") (pintype "unspecified"))
      (node (ref "FB310N") (pin "2") (pinfunction "2_2") (pintype "unspecified"))
    )
    (net (code "127") (name "Net-(CN310-D4)") (class "Default")
      (node (ref "C310O") (pin "1") (pinfunction "1_1") (pintype "unspecified"))
      (node (ref "CN310") (pin "30") (pinfunction "D4_30") (pintype "unspecified"))
      (node (ref "FB310O") (pin "2") (pinfunction "2_2") (pintype "unspecified"))
    )
    (net (code "128") (name "Net-(CN310-D5)") (class "Default")
      (node (ref "C310P") (pin "1") (pinfunction "1_1") (pintype "unspecified"))
      (node (ref "CN310") (pin "31") (pinfunction "D5_31") (pintype "unspecified"))
      (node (ref "FB310P") (pin "2") (pinfunction "2_2") (pintype "unspecified"))
    )
    (net (code "129") (name "Net-(CN310-D6)") (class "Default")
      (node (ref "C310Q") (pin "1") (pinfunction "1_1") (pintype "unspecified"))
      (node (ref "CN310") (pin "32") (pinfunction "D6_32") (pintype "unspecified"))
      (node (ref "FB310Q") (pin "2") (pinfunction "2_2") (pintype "unspecified"))
    )
    (net (code "130") (name "Net-(CN310-D7)") (class "Default")
      (node (ref "C310R") (pin "1") (pinfunction "1_1") (pintype "unspecified"))
      (node (ref "CN310") (pin "33") (pinfunction "D7_33") (pintype "unspecified"))
      (node (ref "FB310R") (pin "2") (pinfunction "2_2") (pintype "unspecified"))
    )
    (net (code "131") (name "Net-(CN310-DP)") (class "Default")
      (node (ref "C310J") (pin "1") (pinfunction "1_1") (pintype "unspecified"))
      (node (ref "CN310") (pin "34") (pinfunction "DP_34") (pintype "unspecified"))
      (node (ref "FB310J") (pin "2") (pinfunction "2_2") (pintype "unspecified"))
    )
    (net (code "132") (name "Net-(CN310-IO)") (class "Default")
      (node (ref "C310A") (pin "2") (pinfunction "2_2") (pintype "unspecified"))
      (node (ref "CN310") (pin "50") (pinfunction "IO_50") (pintype "unspecified"))
      (node (ref "FB310A") (pin "2") (pinfunction "2_2") (pintype "unspecified"))
    )
    (net (code "133") (name "Net-(CN310-MSG)") (class "Default")
      (node (ref "C310E") (pin "2") (pinfunction "2_2") (pintype "unspecified"))
      (node (ref "CN310") (pin "46") (pinfunction "MSG_46") (pintype "unspecified"))
      (node (ref "FB310E") (pin "2") (pinfunction "2_2") (pintype "unspecified"))
    )
    (net (code "134") (name "Net-(CN310-REQ)") (class "Default")
      (node (ref "C310B") (pin "2") (pinfunction "2_2") (pintype "unspecified"))
      (node (ref "CN310") (pin "49") (pinfunction "REQ_49") (pintype "unspecified"))
      (node (ref "FB310B") (pin "2") (pinfunction "2_2") (pintype "unspecified"))
    )
    (net (code "135") (name "Net-(CN310-RST)") (class "Default")
      (node (ref "C310F") (pin "2") (pinfunction "2_2") (pintype "unspecified"))
      (node (ref "CN310") (pin "45") (pinfunction "RST_45") (pintype "unspecified"))
      (node (ref "FB310F") (pin "2") (pinfunction "2_2") (pintype "unspecified"))
    )
    (net (code "136") (name "Net-(CN310-SEL)") (class "Default")
      (node (ref "C310D") (pin "2") (pinfunction "2_2") (pintype "unspecified"))
      (node (ref "CN310") (pin "47") (pinfunction "SEL_47") (pintype "unspecified"))
      (node (ref "FB310D") (pin "2") (pinfunction "2_2") (pintype "unspecified"))
    )
    (net (code "137") (name "Net-(D309A-C)") (class "Default")
      (node (ref "D309A") (pin "1") (pinfunction "C_1") (pintype "unspecified"))
      (node (ref "F309A") (pin "1") (pinfunction "1_1") (pintype "unspecified"))
      (node (ref "F309B") (pin "1") (pinfunction "1_1") (pintype "unspecified"))
    )
    (net (code "138") (name "Net-(FB500-Pad1)") (class "Default")
      (node (ref "FB500") (pin "1") (pinfunction "1_1") (pintype "unspecified"))
      (node (ref "U305") (pin "19") (pinfunction "IOQ_19") (pintype "unspecified"))
    )
    (net (code "139") (name "Net-(FB501-Pad1)") (class "Default")
      (node (ref "FB501") (pin "1") (pinfunction "1_1") (pintype "unspecified"))
      (node (ref "U306") (pin "21") (pinfunction "IOQ_21") (pintype "unspecified"))
    )
    (net (code "140") (name "Net-(FB504-Pad1)") (class "Default")
      (node (ref "FB504") (pin "1") (pinfunction "1_1") (pintype "unspecified"))
      (node (ref "U205") (pin "23") (pinfunction "IOQ_23") (pintype "unspecified"))
    )
    (net (code "141") (name "Net-(FB505-Pad1)") (class "Default")
      (node (ref "FB505") (pin "1") (pinfunction "1_1") (pintype "unspecified"))
      (node (ref "U205") (pin "25") (pinfunction "IOQ_25") (pintype "unspecified"))
    )
    (net (code "142") (name "Net-(U109-B4)") (class "Default")
      (node (ref "FB507") (pin "1") (pinfunction "1_1") (pintype "unspecified"))
      (node (ref "U109") (pin "14") (pinfunction "B4_14") (pintype "unspecified"))
    )
    (net (code "143") (name "Net-(U109-B5)") (class "Default")
      (node (ref "FB508") (pin "1") (pinfunction "1_1") (pintype "unspecified"))
      (node (ref "U109") (pin "13") (pinfunction "B5_13") (pintype "unspecified"))
    )
    (net (code "144") (name "Net-(U300-BR{slash})") (class "Default")
      (node (ref "FB503") (pin "1") (pinfunction "1_1") (pintype "unspecified"))
      (node (ref "U300") (pin "101") (pinfunction "BR/_101") (pintype "unspecified"))
    )
    (net (code "145") (name "Net-(U300-DP0)") (class "Default")
      (node (ref "R300M") (pin "2") (pinfunction "2_2") (pintype "input"))
      (node (ref "U300") (pin "86") (pinfunction "DP0_86") (pintype "unspecified"))
    )
    (net (code "146") (name "Net-(U300-DP1)") (class "Default")
      (node (ref "R300N") (pin "1") (pinfunction "1_1") (pintype "input"))
      (node (ref "U300") (pin "74") (pinfunction "DP1_74") (pintype "unspecified"))
    )
    (net (code "147") (name "Net-(U300-DP2)") (class "Default")
      (node (ref "R300O") (pin "1") (pinfunction "1_1") (pintype "input"))
      (node (ref "U300") (pin "63") (pinfunction "DP2_63") (pintype "unspecified"))
    )
    (net (code "148") (name "Net-(U300-MASTER{slash})") (class "Default")
      (node (ref "FB502") (pin "2") (pinfunction "2_2") (pintype "unspecified"))
      (node (ref "U300") (pin "38") (pinfunction "MASTER/_38") (pintype "unspecified"))
    )
    (net (code "149") (name "Net-(U300-R_W{slash})") (class "Default")
      (node (ref "FB506") (pin "2") (pinfunction "2_2") (pintype "unspecified"))
      (node (ref "U300") (pin "32") (pinfunction "R_W/_32") (pintype "unspecified"))
    )
    (net (code "150") (name "Net-(U301-Out)") (class "Default")
      (node (ref "R301A") (pin "2") (pinfunction "2_2") (pintype "input"))
      (node (ref "U301") (pin "8") (pinfunction "Out_8") (pintype "unspecified"))
    )
    (net (code "151") (name "Net-(U302-Q0#)") (class "Default")
      (node (ref "R302A") (pin "2") (pinfunction "2_2") (pintype "input"))
      (node (ref "U302") (pin "6") (pinfunction "Q0#_6") (pintype "unspecified"))
    )
    (net (code "152") (name "Net-(U302-Q0)") (class "Default")
      (node (ref "R302B") (pin "2") (pinfunction "2_2") (pintype "input"))
      (node (ref "U302") (pin "5") (pinfunction "Q0_5") (pintype "unspecified"))
    )
    (net (code "153") (name "Net-(U310-VREF1)") (class "Default")
      (node (ref "C350A") (pin "1") (pinfunction "1_1") (pintype "unspecified"))
      (node (ref "C350B") (pin "2") (pinfunction "2_2") (pintype "input"))
      (node (ref "U310") (pin "15") (pinfunction "VREF2_15") (pintype "passive"))
      (node (ref "U310") (pin "7") (pinfunction "VREF1_7") (pintype "passive"))
    )
    (net (code "154") (name "Net-(U311-VREF1)") (class "Default")
      (node (ref "C351A") (pin "1") (pinfunction "1_1") (pintype "unspecified"))
      (node (ref "C351B") (pin "1") (pinfunction "1_1") (pintype "input"))
      (node (ref "U311") (pin "15") (pinfunction "VREF2_15") (pintype "passive"))
      (node (ref "U311") (pin "7") (pinfunction "VREF1_7") (pintype "passive"))
    )
    (net (code "155") (name "Net-(U400-VREF1)") (class "Default")
      (node (ref "C400A") (pin "1") (pinfunction "1_1") (pintype "unspecified"))
      (node (ref "C400B") (pin "2") (pinfunction "2_2") (pintype "input"))
      (node (ref "U400") (pin "15") (pinfunction "VREF2_15") (pintype "passive"))
      (node (ref "U400") (pin "7") (pinfunction "VREF1_7") (pintype "passive"))
    )
    (net (code "156") (name "Net-(U401-VREF1)") (class "Default")
      (node (ref "C401A") (pin "1") (pinfunction "1_1") (pintype "unspecified"))
      (node (ref "C401B") (pin "2") (pinfunction "2_2") (pintype "input"))
      (node (ref "U401") (pin "15") (pinfunction "VREF2_15") (pintype "passive"))
      (node (ref "U401") (pin "7") (pinfunction "VREF1_7") (pintype "passive"))
    )
    (net (code "157") (name "PLD_AS") (class "Default")
      (node (ref "R300H") (pin "1") (pinfunction "1_1") (pintype "input"))
      (node (ref "U300") (pin "25") (pinfunction "AS/-TS/_25") (pintype "unspecified"))
      (node (ref "U304") (pin "21") (pinfunction "IOQ_21") (pintype "unspecified"))
      (node (ref "U305") (pin "4") (pinfunction "I_4") (pintype "unspecified"))
    )
    (net (code "158") (name "PLD_ASQ") (class "Default")
      (node (ref "U305") (pin "20") (pinfunction "IOQ_20") (pintype "unspecified"))
      (node (ref "U306") (pin "13") (pinfunction "I_13") (pintype "unspecified"))
    )
    (net (code "159") (name "PLD_CFGLT") (class "Default")
      (node (ref "U200") (pin "11") (pinfunction "CP_11") (pintype "unspecified"))
      (node (ref "U202") (pin "23") (pinfunction "IOQ_23") (pintype "unspecified"))
    )
    (net (code "160") (name "PLD_DOE") (class "Default")
      (node (ref "R109H") (pin "2") (pinfunction "2_2") (pintype "input"))
      (node (ref "U109") (pin "4") (pinfunction "A2_4") (pintype "unspecified"))
      (node (ref "U205") (pin "5") (pinfunction "I_5") (pintype "unspecified"))
      (node (ref "U304") (pin "10") (pinfunction "I_10") (pintype "unspecified"))
      (node (ref "U305") (pin "27") (pinfunction "IOQ_27") (pintype "unspecified"))
      (node (ref "U306") (pin "23") (pinfunction "IOQ_23") (pintype "unspecified"))
    )
    (net (code "161") (name "PLD_DS") (class "Default")
      (node (ref "R300G") (pin "1") (pinfunction "1_1") (pintype "input"))
      (node (ref "U300") (pin "87") (pinfunction "DS/-DLE_87") (pintype "unspecified"))
      (node (ref "U304") (pin "20") (pinfunction "IOQ_20") (pintype "unspecified"))
    )
    (net (code "162") (name "PLD_DS0") (class "Default")
      (node (ref "R109A") (pin "1") (pinfunction "1_1") (pintype "input"))
      (node (ref "U109") (pin "9") (pinfunction "A7_9") (pintype "unspecified"))
      (node (ref "U203") (pin "10") (pinfunction "I_10") (pintype "unspecified"))
      (node (ref "U207") (pin "6") (pinfunction "I_6") (pintype "unspecified"))
      (node (ref "U304") (pin "9") (pinfunction "I_9") (pintype "unspecified"))
      (node (ref "U305") (pin "23") (pinfunction "IOQ_23") (pintype "unspecified"))
    )
    (net (code "163") (name "PLD_DS1") (class "Default")
      (node (ref "R109B") (pin "1") (pinfunction "1_1") (pintype "input"))
      (node (ref "U109") (pin "8") (pinfunction "A6_8") (pintype "unspecified"))
      (node (ref "U304") (pin "7") (pinfunction "I_7") (pintype "unspecified"))
      (node (ref "U305") (pin "24") (pinfunction "IOQ_24") (pintype "unspecified"))
    )
    (net (code "164") (name "PLD_DS2") (class "Default")
      (node (ref "R109C") (pin "1") (pinfunction "1_1") (pintype "input"))
      (node (ref "U109") (pin "7") (pinfunction "A5_7") (pintype "unspecified"))
      (node (ref "U304") (pin "6") (pinfunction "I_6") (pintype "unspecified"))
      (node (ref "U305") (pin "25") (pinfunction "IOQ_25") (pintype "unspecified"))
    )
    (net (code "165") (name "PLD_DS3") (class "Default")
      (node (ref "R109D") (pin "1") (pinfunction "1_1") (pintype "input"))
      (node (ref "U109") (pin "6") (pinfunction "A4_6") (pintype "unspecified"))
      (node (ref "U202") (pin "11") (pinfunction "I_11") (pintype "unspecified"))
      (node (ref "U304") (pin "5") (pinfunction "I_5") (pintype "unspecified"))
      (node (ref "U305") (pin "26") (pinfunction "IOQ_26") (pintype "unspecified"))
    )
    (net (code "166") (name "PLD_DTACK") (class "Default")
      (node (ref "U303") (pin "9") (pinfunction "I_9") (pintype "unspecified"))
      (node (ref "U304") (pin "11") (pinfunction "I_11") (pintype "unspecified"))
      (node (ref "U306") (pin "17") (pinfunction "IOQ_17") (pintype "unspecified"))
    )
    (net (code "167") (name "PLD_FC0") (class "Default")
      (node (ref "R109F") (pin "1") (pinfunction "1_1") (pintype "input"))
      (node (ref "U109") (pin "3") (pinfunction "A1_3") (pintype "unspecified"))
      (node (ref "U202") (pin "16") (pinfunction "I_16") (pintype "unspecified"))
      (node (ref "U300") (pin "30") (pinfunction "FC0-TM0_30") (pintype "unspecified"))
    )
    (net (code "168") (name "PLD_FC1") (class "Default")
      (node (ref "R109G") (pin "1") (pinfunction "1_1") (pintype "input"))
      (node (ref "U109") (pin "2") (pinfunction "A0_2") (pintype "unspecified"))
      (node (ref "U202") (pin "13") (pinfunction "I_13") (pintype "unspecified"))
      (node (ref "U300") (pin "29") (pinfunction "FC1-TM1_29") (pintype "unspecified"))
    )
    (net (code "169") (name "PLD_FC2") (class "Default")
      (node (ref "R103A") (pin "1") (pinfunction "1_1") (pintype "input"))
      (node (ref "U103") (pin "8") (pinfunction "A6_8") (pintype "unspecified"))
      (node (ref "U203") (pin "11") (pinfunction "I_11") (pintype "unspecified"))
      (node (ref "U300") (pin "28") (pinfunction "FC2-TM2_28") (pintype "unspecified"))
    )
    (net (code "170") (name "PLD_FCS") (class "Default")
      (node (ref "FB500") (pin "2") (pinfunction "2_2") (pintype "unspecified"))
      (node (ref "U100") (pin "1") (pinfunction "LEBA_1") (pintype "unspecified"))
      (node (ref "U101") (pin "1") (pinfunction "LEBA_1") (pintype "unspecified"))
      (node (ref "U102") (pin "1") (pinfunction "LEBA_1") (pintype "unspecified"))
      (node (ref "U202") (pin "12") (pinfunction "I_12") (pintype "unspecified"))
      (node (ref "U203") (pin "12") (pinfunction "I_12") (pintype "unspecified"))
      (node (ref "U205") (pin "6") (pinfunction "I_6") (pintype "unspecified"))
      (node (ref "U207") (pin "12") (pinfunction "I_12") (pintype "unspecified"))
      (node (ref "U303") (pin "6") (pinfunction "I_6") (pintype "unspecified"))
      (node (ref "U306") (pin "4") (pinfunction "I_4") (pintype "unspecified"))
    )
    (net (code "171") (name "PLD_INT") (class "Default")
      (node (ref "U203") (pin "7") (pinfunction "I_7") (pintype "unspecified"))
      (node (ref "U207") (pin "26") (pinfunction "IOQ_26") (pintype "unspecified"))
    )
    (net (code "172") (name "PLD_INTREG") (class "Default")
      (node (ref "U203") (pin "24") (pinfunction "IOQ_24") (pintype "unspecified"))
      (node (ref "U204") (pin "11") (pinfunction "CP_11") (pintype "unspecified"))
      (node (ref "U205") (pin "11") (pinfunction "I_11") (pintype "unspecified"))
    )
    (net (code "173") (name "PLD_INTSPC") (class "Default")
      (node (ref "U202") (pin "27") (pinfunction "IOQ_27") (pintype "unspecified"))
      (node (ref "U203") (pin "16") (pinfunction "I_16") (pintype "unspecified"))
    )
    (net (code "174") (name "PLD_INTVEC") (class "Default")
      (node (ref "U203") (pin "23") (pinfunction "IOQ_23") (pintype "unspecified"))
      (node (ref "U204") (pin "1") (pinfunction "OE#_1") (pintype "unspecified"))
      (node (ref "U205") (pin "12") (pinfunction "I_12") (pintype "unspecified"))
      (node (ref "U207") (pin "11") (pinfunction "I_11") (pintype "unspecified"))
    )
    (net (code "175") (name "PLD_MTCR") (class "Default")
      (node (ref "R109E") (pin "1") (pinfunction "1_1") (pintype "input"))
      (node (ref "U109") (pin "5") (pinfunction "A3_5") (pintype "unspecified"))
      (node (ref "U203") (pin "13") (pinfunction "I_13") (pintype "unspecified"))
      (node (ref "U205") (pin "17") (pinfunction "IOQ_17") (pintype "unspecified"))
      (node (ref "U305") (pin "10") (pinfunction "I_10") (pintype "unspecified"))
      (node (ref "U306") (pin "25") (pinfunction "IOQ_25") (pintype "unspecified"))
    )
    (net (code "176") (name "PLD_MYBUS") (class "Default")
      (node (ref "U205") (pin "4") (pinfunction "I_4") (pintype "unspecified"))
      (node (ref "U303") (pin "20") (pinfunction "IOQ_20") (pintype "unspecified"))
      (node (ref "U304") (pin "13") (pinfunction "I_13") (pintype "unspecified"))
      (node (ref "U305") (pin "3") (pinfunction "I_3") (pintype "unspecified"))
      (node (ref "U306") (pin "3") (pinfunction "I_3") (pintype "unspecified"))
    )
    (net (code "177") (name "PLD_NACK") (class "Default")
      (node (ref "U205") (pin "16") (pinfunction "I_16") (pintype "unspecified"))
      (node (ref "U207") (pin "24") (pinfunction "IOQ_24") (pintype "unspecified"))
    )
    (net (code "178") (name "PLD_NOZ3") (class "Default")
      (node (ref "U205") (pin "10") (pinfunction "I_10") (pintype "unspecified"))
      (node (ref "U305") (pin "9") (pinfunction "I_9") (pintype "unspecified"))
      (node (ref "U306") (pin "20") (pinfunction "IOQ_20") (pintype "unspecified"))
    )
    (net (code "179") (name "PLD_READ") (class "Default")
      (node (ref "FB506") (pin "1") (pinfunction "1_1") (pintype "unspecified"))
      (node (ref "R103B") (pin "1") (pinfunction "1_1") (pintype "input"))
      (node (ref "U103") (pin "9") (pinfunction "A7_9") (pintype "unspecified"))
      (node (ref "U202") (pin "10") (pinfunction "I_10") (pintype "unspecified"))
      (node (ref "U203") (pin "9") (pinfunction "I_9") (pintype "unspecified"))
      (node (ref "U205") (pin "7") (pinfunction "I_7") (pintype "unspecified"))
      (node (ref "U207") (pin "7") (pinfunction "I_7") (pintype "unspecified"))
      (node (ref "U304") (pin "4") (pinfunction "I_4") (pintype "unspecified"))
      (node (ref "U305") (pin "5") (pinfunction "I_5") (pintype "unspecified"))
    )
    (net (code "180") (name "PLD_SCSI") (class "Default")
      (node (ref "U203") (pin "26") (pinfunction "IOQ_26") (pintype "unspecified"))
      (node (ref "U304") (pin "3") (pinfunction "I_3") (pintype "unspecified"))
      (node (ref "U306") (pin "7") (pinfunction "I_7") (pintype "unspecified"))
    )
    (net (code "181") (name "PLD_SID") (class "Default")
      (node (ref "U203") (pin "17") (pinfunction "IOQ_17") (pintype "unspecified"))
      (node (ref "U205") (pin "19") (pinfunction "IOQ_19") (pintype "unspecified"))
      (node (ref "U213") (pin "1") (pinfunction "OE1#_1") (pintype "unspecified"))
      (node (ref "U213") (pin "19") (pinfunction "OE2#_19") (pintype "unspecified"))
    )
    (net (code "182") (name "PLD_SIZ0") (class "Default")
      (node (ref "R300E") (pin "1") (pinfunction "1_1") (pintype "input"))
      (node (ref "U300") (pin "27") (pinfunction "SIZ0_27") (pintype "unspecified"))
      (node (ref "U304") (pin "24") (pinfunction "IOQ_24") (pintype "unspecified"))
      (node (ref "U305") (pin "7") (pinfunction "I_7") (pintype "unspecified"))
    )
    (net (code "183") (name "PLD_SIZ1") (class "Default")
      (node (ref "R300F") (pin "1") (pinfunction "1_1") (pintype "input"))
      (node (ref "U300") (pin "26") (pinfunction "SIZ1_26") (pintype "unspecified"))
      (node (ref "U304") (pin "25") (pinfunction "IOQ_25") (pintype "unspecified"))
      (node (ref "U305") (pin "6") (pinfunction "I_6") (pintype "unspecified"))
    )
    (net (code "184") (name "ROM_A15") (class "Default")
      (node (ref "J100") (pin "2") (pinfunction "2_2") (pintype "input"))
      (node (ref "U206") (pin "1") (pinfunction "VPP_1") (pintype "input"))
    )
    (net (code "185") (name "ROM_OE") (class "Default")
      (node (ref "U203") (pin "25") (pinfunction "IOQ_25") (pintype "unspecified"))
      (node (ref "U206") (pin "22") (pinfunction "OE#_22") (pintype "passive"))
      (node (ref "U207") (pin "19") (pinfunction "IOQ_19") (pintype "unspecified"))
    )
    (net (code "186") (name "SBG") (class "Default")
      (node (ref "U300") (pin "100") (pinfunction "BG/_100") (pintype "unspecified"))
      (node (ref "U303") (pin "21") (pinfunction "IOQ_21") (pintype "unspecified"))
    )
    (net (code "187") (name "SBR") (class "Default")
      (node (ref "FB503") (pin "2") (pinfunction "2_2") (pintype "unspecified"))
      (node (ref "U303") (pin "4") (pinfunction "I_4") (pintype "unspecified"))
    )
    (net (code "188") (name "SCDAT0") (class "Default")
      (node (ref "FB310K") (pin "1") (pinfunction "1_1") (pintype "unspecified"))
      (node (ref "FB311A") (pin "2") (pinfunction "2_2") (pintype "unspecified"))
      (node (ref "RP300B") (pin "5") (pinfunction "R4_5") (pintype "unspecified"))
      (node (ref "U300") (pin "131") (pinfunction "SD0/_131") (pintype "unspecified"))
      (node (ref "U311") (pin "3") (pinfunction "R2_3") (pintype "unspecified"))
    )
    (net (code "189") (name "SCDAT1") (class "Default")
      (node (ref "FB310L") (pin "1") (pinfunction "1_1") (pintype "unspecified"))
      (node (ref "FB311B") (pin "2") (pinfunction "2_2") (pintype "unspecified"))
      (node (ref "RP300B") (pin "6") (pinfunction "R5_6") (pintype "unspecified"))
      (node (ref "U300") (pin "130") (pinfunction "SD1/_130") (pintype "unspecified"))
      (node (ref "U311") (pin "4") (pinfunction "R3_4") (pintype "unspecified"))
    )
    (net (code "190") (name "SCDAT2") (class "Default")
      (node (ref "FB310M") (pin "1") (pinfunction "1_1") (pintype "unspecified"))
      (node (ref "FB311C") (pin "2") (pinfunction "2_2") (pintype "unspecified"))
      (node (ref "RP300B") (pin "7") (pinfunction "R6_7") (pintype "unspecified"))
      (node (ref "U300") (pin "129") (pinfunction "SD2/_129") (pintype "unspecified"))
      (node (ref "U311") (pin "5") (pinfunction "R4_5") (pintype "unspecified"))
    )
    (net (code "191") (name "SCDAT3") (class "Default")
      (node (ref "FB310N") (pin "1") (pinfunction "1_1") (pintype "unspecified"))
      (node (ref "FB311D") (pin "2") (pinfunction "2_2") (pintype "unspecified"))
      (node (ref "RP300A") (pin "7") (pinfunction "R6_7") (pintype "unspecified"))
      (node (ref "U300") (pin "127") (pinfunction "SD3/_127") (pintype "unspecified"))
      (node (ref "U311") (pin "6") (pinfunction "R5_6") (pintype "unspecified"))
    )
    (net (code "192") (name "SCDAT4") (class "Default")
      (node (ref "FB310O") (pin "1") (pinfunction "1_1") (pintype "unspecified"))
      (node (ref "FB311E") (pin "2") (pinfunction "2_2") (pintype "unspecified"))
      (node (ref "RP300A") (pin "6") (pinfunction "R5_6") (pintype "unspecified"))
      (node (ref "U300") (pin "126") (pinfunction "SD4/_126") (pintype "unspecified"))
      (node (ref "U310") (pin "5") (pinfunction "R4_5") (pintype "unspecified"))
    )
    (net (code "193") (name "SCDAT5") (class "Default")
      (node (ref "FB310P") (pin "1") (pinfunction "1_1") (pintype "unspecified"))
      (node (ref "FB311F") (pin "2") (pinfunction "2_2") (pintype "unspecified"))
      (node (ref "RP300A") (pin "5") (pinfunction "R4_5") (pintype "unspecified"))
      (node (ref "U300") (pin "125") (pinfunction "SD5/_125") (pintype "unspecified"))
      (node (ref "U311") (pin "10") (pinfunction "R6_10") (pintype "unspecified"))
    )
    (net (code "194") (name "SCDAT6") (class "Default")
      (node (ref "FB310Q") (pin "1") (pinfunction "1_1") (pintype "unspecified"))
      (node (ref "FB311G") (pin "2") (pinfunction "2_2") (pintype "unspecified"))
      (node (ref "RP300A") (pin "4") (pinfunction "R3_4") (pintype "unspecified"))
      (node (ref "U300") (pin "124") (pinfunction "SD6/_124") (pintype "unspecified"))
      (node (ref "U311") (pin "11") (pinfunction "R7_11") (pintype "unspecified"))
    )
    (net (code "195") (name "SCDAT7") (class "Default")
      (node (ref "FB310R") (pin "1") (pinfunction "1_1") (pintype "unspecified"))
      (node (ref "FB311H") (pin "2") (pinfunction "2_2") (pintype "unspecified"))
      (node (ref "RP300A") (pin "3") (pinfunction "R2_3") (pintype "unspecified"))
      (node (ref "U300") (pin "122") (pinfunction "SD7/_122") (pintype "unspecified"))
      (node (ref "U311") (pin "12") (pinfunction "R8_12") (pintype "unspecified"))
    )
    (net (code "196") (name "SCDATP") (class "Default")
      (node (ref "FB310J") (pin "1") (pinfunction "1_1") (pintype "unspecified"))
      (node (ref "FB311I") (pin "2") (pinfunction "2_2") (pintype "unspecified"))
      (node (ref "RP300A") (pin "2") (pinfunction "R1_2") (pintype "unspecified"))
      (node (ref "U300") (pin "121") (pinfunction "SDP/_121") (pintype "unspecified"))
      (node (ref "U311") (pin "13") (pinfunction "R9_13") (pintype "unspecified"))
    )
    (net (code "197") (name "SCSI_BUSY") (class "Default")
      (node (ref "CN309") (pin "36") (pinfunction "36_36") (pintype "unspecified"))
      (node (ref "FB311R") (pin "1") (pinfunction "1_1") (pintype "unspecified"))
      (node (ref "U307") (pin "1") (pinfunction "1A_1") (pintype "unspecified"))
      (node (ref "U307") (pin "3") (pinfunction "2A_3") (pintype "unspecified"))
    )
    (net (code "198") (name "SCSI_TERMPWR") (class "Default")
      (node (ref "CN309") (pin "26") (pinfunction "26_26") (pintype "unspecified"))
      (node (ref "CN310") (pin "38") (pinfunction "TERM_38") (pintype "unspecified"))
      (node (ref "F309A") (pin "2") (pinfunction "2_2") (pintype "unspecified"))
      (node (ref "F309B") (pin "2") (pinfunction "2_2") (pintype "unspecified"))
      (node (ref "U310") (pin "1") (pinfunction "TPWR1_1") (pintype "passive"))
      (node (ref "U310") (pin "9") (pinfunction "TPWR2_9") (pintype "passive"))
      (node (ref "U311") (pin "1") (pinfunction "TPWR1_1") (pintype "passive"))
      (node (ref "U311") (pin "9") (pinfunction "TPWR2_9") (pintype "passive"))
    )
    (net (code "199") (name "SCTRL_ACK") (class "Default")
      (node (ref "FB310G") (pin "1") (pinfunction "1_1") (pintype "unspecified"))
      (node (ref "FB311Q") (pin "2") (pinfunction "2_2") (pintype "unspecified"))
      (node (ref "RP300C") (pin "7") (pinfunction "R6_7") (pintype "unspecified"))
      (node (ref "U300") (pin "117") (pinfunction "ACK/_117") (pintype "unspecified"))
      (node (ref "U310") (pin "10") (pinfunction "R6_10") (pintype "unspecified"))
    )
    (net (code "200") (name "SCTRL_ATN") (class "Default")
      (node (ref "FB310I") (pin "1") (pinfunction "1_1") (pintype "unspecified"))
      (node (ref "FB311J") (pin "2") (pinfunction "2_2") (pintype "unspecified"))
      (node (ref "RP300C") (pin "6") (pinfunction "R5_6") (pintype "unspecified"))
      (node (ref "U300") (pin "120") (pinfunction "ATN/_120") (pintype "unspecified"))
      (node (ref "U310") (pin "6") (pinfunction "R5_6") (pintype "unspecified"))
    )
    (net (code "201") (name "SCTRL_BSY") (class "Default")
      (node (ref "FB310H") (pin "1") (pinfunction "1_1") (pintype "unspecified"))
      (node (ref "FB311R") (pin "2") (pinfunction "2_2") (pintype "unspecified"))
      (node (ref "RP300C") (pin "3") (pinfunction "R2_3") (pintype "unspecified"))
      (node (ref "U300") (pin "119") (pinfunction "BSY/_119") (pintype "unspecified"))
      (node (ref "U310") (pin "2") (pinfunction "R1_2") (pintype "unspecified"))
    )
    (net (code "202") (name "SCTRL_CD") (class "Default")
      (node (ref "FB310C") (pin "1") (pinfunction "1_1") (pintype "unspecified"))
      (node (ref "FB311M") (pin "2") (pinfunction "2_2") (pintype "unspecified"))
      (node (ref "RP300B") (pin "2") (pinfunction "R1_2") (pintype "unspecified"))
      (node (ref "U300") (pin "112") (pinfunction "C/D_112") (pintype "unspecified"))
      (node (ref "U311") (pin "2") (pinfunction "R1_2") (pintype "unspecified"))
    )
    (net (code "203") (name "SCTRL_IO") (class "Default")
      (node (ref "FB310A") (pin "1") (pinfunction "1_1") (pintype "unspecified"))
      (node (ref "FB311K") (pin "2") (pinfunction "2_2") (pintype "unspecified"))
      (node (ref "RP300B") (pin "3") (pinfunction "R2_3") (pintype "unspecified"))
      (node (ref "U300") (pin "110") (pinfunction "I/O_110") (pintype "unspecified"))
      (node (ref "U310") (pin "13") (pinfunction "R9_13") (pintype "unspecified"))
    )
    (net (code "204") (name "SCTRL_MSG") (class "Default")
      (node (ref "FB310E") (pin "1") (pinfunction "1_1") (pintype "unspecified"))
      (node (ref "FB311O") (pin "2") (pinfunction "2_2") (pintype "unspecified"))
      (node (ref "RP300B") (pin "4") (pinfunction "R3_4") (pintype "unspecified"))
      (node (ref "U300") (pin "115") (pinfunction "MSG/_115") (pintype "unspecified"))
      (node (ref "U310") (pin "12") (pinfunction "R8_12") (pintype "unspecified"))
    )
    (net (code "205") (name "SCTRL_REQ") (class "Default")
      (node (ref "FB310B") (pin "1") (pinfunction "1_1") (pintype "unspecified"))
      (node (ref "FB311L") (pin "2") (pinfunction "2_2") (pintype "unspecified"))
      (node (ref "RP300C") (pin "2") (pinfunction "R1_2") (pintype "unspecified"))
      (node (ref "U300") (pin "111") (pinfunction "REQ/_111") (pintype "unspecified"))
      (node (ref "U310") (pin "11") (pinfunction "R7_11") (pintype "unspecified"))
    )
    (net (code "206") (name "SCTRL_RST") (class "Default")
      (node (ref "FB310F") (pin "1") (pinfunction "1_1") (pintype "unspecified"))
      (node (ref "FB311P") (pin "2") (pinfunction "2_2") (pintype "unspecified"))
      (node (ref "RP300C") (pin "5") (pinfunction "R4_5") (pintype "unspecified"))
      (node (ref "U300") (pin "116") (pinfunction "RST/_116") (pintype "unspecified"))
      (node (ref "U310") (pin "4") (pinfunction "R3_4") (pintype "unspecified"))
    )
    (net (code "207") (name "SCTRL_SEL") (class "Default")
      (node (ref "FB310D") (pin "1") (pinfunction "1_1") (pintype "unspecified"))
      (node (ref "FB311N") (pin "2") (pinfunction "2_2") (pintype "unspecified"))
      (node (ref "RP300C") (pin "4") (pinfunction "R3_4") (pintype "unspecified"))
      (node (ref "U300") (pin "114") (pinfunction "SEL/_114") (pintype "unspecified"))
      (node (ref "U310") (pin "3") (pinfunction "R2_3") (pintype "unspecified"))
    )
    (net (code "208") (name "SLACK") (class "Default")
      (node (ref "U205") (pin "9") (pinfunction "I_9") (pintype "unspecified"))
      (node (ref "U300") (pin "92") (pinfunction "SLACK/_92") (pintype "unspecified"))
    )
    (net (code "209") (name "SREG") (class "Default")
      (node (ref "U300") (pin "93") (pinfunction "CS/_93") (pintype "unspecified"))
      (node (ref "U304") (pin "19") (pinfunction "IOQ_19") (pintype "unspecified"))
    )
    (net (code "210") (name "STERM") (class "Default")
      (node (ref "R300D") (pin "2") (pinfunction "2_2") (pintype "input"))
      (node (ref "U300") (pin "36") (pinfunction "STERM/-TA/_36") (pintype "unspecified"))
      (node (ref "U304") (pin "12") (pinfunction "I_12") (pintype "unspecified"))
      (node (ref "U306") (pin "19") (pinfunction "IOQ_19") (pintype "unspecified"))
    )
    (net (code "211") (name "T_GND") (class "Default")
      (node (ref "C400A") (pin "2") (pinfunction "2_2") (pintype "unspecified"))
      (node (ref "C400B") (pin "1") (pinfunction "1_1") (pintype "input"))
      (node (ref "C401A") (pin "2") (pinfunction "2_2") (pintype "unspecified"))
      (node (ref "C401B") (pin "1") (pinfunction "1_1") (pintype "input"))
      (node (ref "C402") (pin "1") (pinfunction "1_1") (pintype "input"))
      (node (ref "C403") (pin "2") (pinfunction "2_2") (pintype "unspecified"))
      (node (ref "CN400") (pin "1") (pinfunction "1_1") (pintype "unspecified"))
      (node (ref "CN400") (pin "11") (pinfunction "11_11") (pintype "unspecified"))
      (node (ref "CN400") (pin "13") (pinfunction "13_13") (pintype "unspecified"))
      (node (ref "CN400") (pin "15") (pinfunction "15_15") (pintype "unspecified"))
      (node (ref "CN400") (pin "17") (pinfunction "17_17") (pintype "unspecified"))
      (node (ref "CN400") (pin "19") (pinfunction "19_19") (pintype "unspecified"))
      (node (ref "CN400") (pin "20") (pinfunction "20_20") (pintype "unspecified"))
      (node (ref "CN400") (pin "21") (pinfunction "21_21") (pintype "unspecified"))
      (node (ref "CN400") (pin "22") (pinfunction "22_22") (pintype "unspecified"))
      (node (ref "CN400") (pin "23") (pinfunction "23_23") (pintype "unspecified"))
      (node (ref "CN400") (pin "24") (pinfunction "24_24") (pintype "unspecified"))
      (node (ref "CN400") (pin "27") (pinfunction "27_27") (pintype "unspecified"))
      (node (ref "CN400") (pin "28") (pinfunction "28_28") (pintype "unspecified"))
      (node (ref "CN400") (pin "29") (pinfunction "29_29") (pintype "unspecified"))
      (node (ref "CN400") (pin "3") (pinfunction "3_3") (pintype "unspecified"))
      (node (ref "CN400") (pin "30") (pinfunction "30_30") (pintype "unspecified"))
      (node (ref "CN400") (pin "31") (pinfunction "31_31") (pintype "unspecified"))
      (node (ref "CN400") (pin "33") (pinfunction "33_33") (pintype "unspecified"))
      (node (ref "CN400") (pin "34") (pinfunction "34_34") (pintype "unspecified"))
      (node (ref "CN400") (pin "35") (pinfunction "35_35") (pintype "unspecified"))
      (node (ref "CN400") (pin "37") (pinfunction "37_37") (pintype "unspecified"))
      (node (ref "CN400") (pin "39") (pinfunction "39_39") (pintype "unspecified"))
      (node (ref "CN400") (pin "41") (pinfunction "41_41") (pintype "unspecified"))
      (node (ref "CN400") (pin "43") (pinfunction "43_43") (pintype "unspecified"))
      (node (ref "CN400") (pin "45") (pinfunction "45_45") (pintype "unspecified"))
      (node (ref "CN400") (pin "47") (pinfunction "47_47") (pintype "unspecified"))
      (node (ref "CN400") (pin "49") (pinfunction "49_49") (pintype "unspecified"))
      (node (ref "CN400") (pin "5") (pinfunction "5_5") (pintype "unspecified"))
      (node (ref "CN400") (pin "7") (pinfunction "7_7") (pintype "unspecified"))
      (node (ref "CN400") (pin "9") (pinfunction "9_9") (pintype "unspecified"))
      (node (ref "U400") (pin "8") (pinfunction "GND_8") (pintype "passive"))
      (node (ref "U401") (pin "8") (pinfunction "GND_8") (pintype "passive"))
    )
    (net (code "212") (name "T_SCDAT0") (class "Default")
      (node (ref "CN400") (pin "2") (pinfunction "2_2") (pintype "unspecified"))
      (node (ref "U401") (pin "13") (pinfunction "R9_13") (pintype "unspecified"))
    )
    (net (code "213") (name "T_SCDAT1") (class "Default")
      (node (ref "CN400") (pin "4") (pinfunction "4_4") (pintype "unspecified"))
      (node (ref "U401") (pin "12") (pinfunction "R8_12") (pintype "unspecified"))
    )
    (net (code "214") (name "T_SCDAT2") (class "Default")
      (node (ref "CN400") (pin "6") (pinfunction "6_6") (pintype "unspecified"))
      (node (ref "U401") (pin "11") (pinfunction "R7_11") (pintype "unspecified"))
    )
    (net (code "215") (name "T_SCDAT3") (class "Default")
      (node (ref "CN400") (pin "8") (pinfunction "8_8") (pintype "unspecified"))
      (node (ref "U401") (pin "10") (pinfunction "R6_10") (pintype "unspecified"))
    )
    (net (code "216") (name "T_SCDAT4") (class "Default")
      (node (ref "CN400") (pin "10") (pinfunction "10_10") (pintype "unspecified"))
      (node (ref "U401") (pin "6") (pinfunction "R5_6") (pintype "unspecified"))
    )
    (net (code "217") (name "T_SCDAT5") (class "Default")
      (node (ref "CN400") (pin "12") (pinfunction "12_12") (pintype "unspecified"))
      (node (ref "U401") (pin "5") (pinfunction "R4_5") (pintype "unspecified"))
    )
    (net (code "218") (name "T_SCDAT6") (class "Default")
      (node (ref "CN400") (pin "14") (pinfunction "14_14") (pintype "unspecified"))
      (node (ref "U401") (pin "4") (pinfunction "R3_4") (pintype "unspecified"))
    )
    (net (code "219") (name "T_SCDAT7") (class "Default")
      (node (ref "CN400") (pin "16") (pinfunction "16_16") (pintype "unspecified"))
      (node (ref "U401") (pin "3") (pinfunction "R2_3") (pintype "unspecified"))
    )
    (net (code "220") (name "T_SCDATP") (class "Default")
      (node (ref "CN400") (pin "18") (pinfunction "18_18") (pintype "unspecified"))
      (node (ref "U401") (pin "2") (pinfunction "R1_2") (pintype "unspecified"))
    )
    (net (code "221") (name "T_SCSI_TERMPWR") (class "Default")
      (node (ref "C402") (pin "2") (pinfunction "2_2") (pintype "input"))
      (node (ref "C403") (pin "1") (pinfunction "1_1") (pintype "unspecified"))
      (node (ref "CN400") (pin "26") (pinfunction "26_26") (pintype "unspecified"))
      (node (ref "U400") (pin "1") (pinfunction "TPWR1_1") (pintype "passive"))
      (node (ref "U400") (pin "9") (pinfunction "TPWR2_9") (pintype "passive"))
      (node (ref "U401") (pin "1") (pinfunction "TPWR1_1") (pintype "passive"))
      (node (ref "U401") (pin "9") (pinfunction "TPWR2_9") (pintype "passive"))
    )
    (net (code "222") (name "T_SCTRL_ACK") (class "Default")
      (node (ref "CN400") (pin "38") (pinfunction "38_38") (pintype "unspecified"))
      (node (ref "U400") (pin "11") (pinfunction "R7_11") (pintype "unspecified"))
    )
    (net (code "223") (name "T_SCTRL_ATN") (class "Default")
      (node (ref "CN400") (pin "32") (pinfunction "32_32") (pintype "unspecified"))
      (node (ref "U400") (pin "13") (pinfunction "R9_13") (pintype "unspecified"))
    )
    (net (code "224") (name "T_SCTRL_BSY") (class "Default")
      (node (ref "CN400") (pin "36") (pinfunction "36_36") (pintype "unspecified"))
      (node (ref "U400") (pin "12") (pinfunction "R8_12") (pintype "unspecified"))
    )
    (net (code "225") (name "T_SCTRL_CD") (class "Default")
      (node (ref "CN400") (pin "46") (pinfunction "46_46") (pintype "unspecified"))
      (node (ref "U400") (pin "4") (pinfunction "R3_4") (pintype "unspecified"))
    )
    (net (code "226") (name "T_SCTRL_IO") (class "Default")
      (node (ref "CN400") (pin "50") (pinfunction "50_50") (pintype "unspecified"))
      (node (ref "U400") (pin "2") (pinfunction "R1_2") (pintype "unspecified"))
    )
    (net (code "227") (name "T_SCTRL_MSG") (class "Default")
      (node (ref "CN400") (pin "42") (pinfunction "42_42") (pintype "unspecified"))
      (node (ref "U400") (pin "6") (pinfunction "R5_6") (pintype "unspecified"))
    )
    (net (code "228") (name "T_SCTRL_REQ") (class "Default")
      (node (ref "CN400") (pin "48") (pinfunction "48_48") (pintype "unspecified"))
      (node (ref "U400") (pin "3") (pinfunction "R2_3") (pintype "unspecified"))
    )
    (net (code "229") (name "T_SCTRL_RST") (class "Default")
      (node (ref "CN400") (pin "40") (pinfunction "40_40") (pintype "unspecified"))
      (node (ref "U400") (pin "10") (pinfunction "R6_10") (pintype "unspecified"))
    )
    (net (code "230") (name "T_SCTRL_SEL") (class "Default")
      (node (ref "CN400") (pin "44") (pinfunction "44_44") (pintype "unspecified"))
      (node (ref "U400") (pin "5") (pinfunction "R4_5") (pintype "unspecified"))
    )
    (net (code "231") (name "V5") (class "Default")
      (node (ref "C1") (pin "05") (pinfunction "+5V_05") (pintype "bidirectional"))
      (node (ref "C1") (pin "06") (pinfunction "+5V_06") (pintype "bidirectional"))
      (node (ref "C10") (pin "1") (pinfunction "1_1") (pintype "input"))
      (node (ref "C100A") (pin "1") (pinfunction "1_1") (pintype "input"))
      (node (ref "C101A") (pin "1") (pinfunction "1_1") (pintype "input"))
      (node (ref "C102A") (pin "1") (pinfunction "1_1") (pintype "input"))
      (node (ref "C103A") (pin "1") (pinfunction "1_1") (pintype "input"))
      (node (ref "C105A") (pin "1") (pinfunction "1_1") (pintype "input"))
      (node (ref "C106A") (pin "2") (pinfunction "2_2") (pintype "input"))
      (node (ref "C107A") (pin "1") (pinfunction "1_1") (pintype "input"))
      (node (ref "C108A") (pin "1") (pinfunction "1_1") (pintype "input"))
      (node (ref "C109A") (pin "1") (pinfunction "1_1") (pintype "input"))
      (node (ref "C11") (pin "1") (pinfunction "1_1") (pintype "input"))
      (node (ref "C12") (pin "1") (pinfunction "1_1") (pintype "input"))
      (node (ref "C13") (pin "1") (pinfunction "1_1") (pintype "input"))
      (node (ref "C1A") (pin "2") (pinfunction "2_2") (pintype "input"))
      (node (ref "C1B") (pin "1") (pinfunction "1_1") (pintype "input"))
      (node (ref "C200A") (pin "2") (pinfunction "2_2") (pintype "input"))
      (node (ref "C201A") (pin "1") (pinfunction "1_1") (pintype "input"))
      (node (ref "C202A") (pin "1") (pinfunction "1_1") (pintype "input"))
      (node (ref "C203A") (pin "1") (pinfunction "1_1") (pintype "input"))
      (node (ref "C204A") (pin "2") (pinfunction "2_2") (pintype "input"))
      (node (ref "C205A") (pin "1") (pinfunction "1_1") (pintype "input"))
      (node (ref "C206A") (pin "2") (pinfunction "2_2") (pintype "input"))
      (node (ref "C207A") (pin "1") (pinfunction "1_1") (pintype "input"))
      (node (ref "C212A") (pin "1") (pinfunction "1_1") (pintype "input"))
      (node (ref "C300A") (pin "1") (pinfunction "1_1") (pintype "input"))
      (node (ref "C300B") (pin "1") (pinfunction "1_1") (pintype "input"))
      (node (ref "C300C") (pin "1") (pinfunction "1_1") (pintype "input"))
      (node (ref "C300D") (pin "2") (pinfunction "2_2") (pintype "input"))
      (node (ref "C300E") (pin "1") (pinfunction "1_1") (pintype "input"))
      (node (ref "C300F") (pin "1") (pinfunction "1_1") (pintype "input"))
      (node (ref "C300G") (pin "1") (pinfunction "1_1") (pintype "input"))
      (node (ref "C300H") (pin "2") (pinfunction "2_2") (pintype "input"))
      (node (ref "C300I") (pin "1") (pinfunction "1_1") (pintype "input"))
      (node (ref "C301A") (pin "2") (pinfunction "2_2") (pintype "input"))
      (node (ref "C302A") (pin "1") (pinfunction "1_1") (pintype "input"))
      (node (ref "C303A") (pin "2") (pinfunction "2_2") (pintype "input"))
      (node (ref "C304A") (pin "1") (pinfunction "1_1") (pintype "input"))
      (node (ref "C305A") (pin "1") (pinfunction "1_1") (pintype "input"))
      (node (ref "C306A") (pin "1") (pinfunction "1_1") (pintype "input"))
      (node (ref "C307A") (pin "2") (pinfunction "2_2") (pintype "input"))
      (node (ref "CN2") (pin "4") (pinfunction "4_4") (pintype "unspecified"))
      (node (ref "CN3") (pin "1") (pinfunction "5V_1") (pintype "unspecified"))
      (node (ref "CN308") (pin "2") (pinfunction "2_2") (pintype "input"))
      (node (ref "CN351") (pin "2") (pinfunction "2_2") (pintype "input"))
      (node (ref "D309A") (pin "2") (pinfunction "A_2") (pintype "unspecified"))
      (node (ref "J100") (pin "1") (pinfunction "1_1") (pintype "input"))
      (node (ref "R100A") (pin "2") (pinfunction "2_2") (pintype "input"))
      (node (ref "R103A") (pin "2") (pinfunction "2_2") (pintype "input"))
      (node (ref "R103B") (pin "2") (pinfunction "2_2") (pintype "input"))
      (node (ref "R109A") (pin "2") (pinfunction "2_2") (pintype "input"))
      (node (ref "R109B") (pin "2") (pinfunction "2_2") (pintype "input"))
      (node (ref "R109C") (pin "2") (pinfunction "2_2") (pintype "input"))
      (node (ref "R109D") (pin "2") (pinfunction "2_2") (pintype "input"))
      (node (ref "R109E") (pin "2") (pinfunction "2_2") (pintype "input"))
      (node (ref "R109F") (pin "2") (pinfunction "2_2") (pintype "input"))
      (node (ref "R109G") (pin "2") (pinfunction "2_2") (pintype "input"))
      (node (ref "R200A") (pin "2") (pinfunction "2_2") (pintype "input"))
      (node (ref "R200B") (pin "2") (pinfunction "2_2") (pintype "input"))
      (node (ref "R200C") (pin "2") (pinfunction "2_2") (pintype "input"))
      (node (ref "R200D") (pin "2") (pinfunction "2_2") (pintype "input"))
      (node (ref "R200E") (pin "2") (pinfunction "2_2") (pintype "input"))
      (node (ref "R200F") (pin "2") (pinfunction "2_2") (pintype "input"))
      (node (ref "R200G") (pin "2") (pinfunction "2_2") (pintype "input"))
      (node (ref "R200H") (pin "2") (pinfunction "2_2") (pintype "input"))
      (node (ref "R212A") (pin "1") (pinfunction "1_1") (pintype "input"))
      (node (ref "R212B") (pin "2") (pinfunction "2_2") (pintype "input"))
      (node (ref "R212C") (pin "2") (pinfunction "2_2") (pintype "input"))
      (node (ref "R212D") (pin "2") (pinfunction "2_2") (pintype "input"))
      (node (ref "R212E") (pin "1") (pinfunction "1_1") (pintype "input"))
      (node (ref "R212F") (pin "1") (pinfunction "1_1") (pintype "input"))
      (node (ref "R212G") (pin "1") (pinfunction "1_1") (pintype "input"))
      (node (ref "R212H") (pin "1") (pinfunction "1_1") (pintype "input"))
      (node (ref "R300A") (pin "2") (pinfunction "2_2") (pintype "input"))
      (node (ref "R300B") (pin "1") (pinfunction "1_1") (pintype "input"))
      (node (ref "R300C") (pin "2") (pinfunction "2_2") (pintype "input"))
      (node (ref "R300D") (pin "1") (pinfunction "1_1") (pintype "input"))
      (node (ref "R300E") (pin "2") (pinfunction "2_2") (pintype "input"))
      (node (ref "R300F") (pin "2") (pinfunction "2_2") (pintype "input"))
      (node (ref "R300G") (pin "2") (pinfunction "2_2") (pintype "input"))
      (node (ref "R300H") (pin "2") (pinfunction "2_2") (pintype "input"))
      (node (ref "R300I") (pin "2") (pinfunction "2_2") (pintype "input"))
      (node (ref "R300J") (pin "2") (pinfunction "2_2") (pintype "input"))
      (node (ref "R300K") (pin "2") (pinfunction "2_2") (pintype "input"))
      (node (ref "R300L") (pin "2") (pinfunction "2_2") (pintype "input"))
      (node (ref "R300M") (pin "1") (pinfunction "1_1") (pintype "input"))
      (node (ref "R300N") (pin "2") (pinfunction "2_2") (pintype "input"))
      (node (ref "R300O") (pin "2") (pinfunction "2_2") (pintype "input"))
      (node (ref "R300P") (pin "2") (pinfunction "2_2") (pintype "input"))
      (node (ref "R307A") (pin "2") (pinfunction "2_2") (pintype "input"))
      (node (ref "R307B") (pin "1") (pinfunction "1_1") (pintype "input"))
      (node (ref "RP300A") (pin "8") (pinfunction "COM2_8") (pintype "unspecified"))
      (node (ref "RP300B") (pin "8") (pinfunction "COM2_8") (pintype "unspecified"))
      (node (ref "RP300C") (pin "8") (pinfunction "COM2_8") (pintype "unspecified"))
      (node (ref "U100") (pin "24") (pinfunction "VCC_24") (pintype "passive"))
      (node (ref "U101") (pin "24") (pinfunction "VCC_24") (pintype "passive"))
      (node (ref "U102") (pin "24") (pinfunction "VCC_24") (pintype "passive"))
      (node (ref "U103") (pin "20") (pinfunction "VCC_20") (pintype "unspecified"))
      (node (ref "U105") (pin "24") (pinfunction "VCC_24") (pintype "passive"))
      (node (ref "U106") (pin "24") (pinfunction "VCC_24") (pintype "passive"))
      (node (ref "U107") (pin "24") (pinfunction "VCC_24") (pintype "passive"))
      (node (ref "U108") (pin "24") (pinfunction "VCC_24") (pintype "passive"))
      (node (ref "U109") (pin "20") (pinfunction "VCC_20") (pintype "unspecified"))
      (node (ref "U200") (pin "20") (pinfunction "VCC_20") (pintype "unspecified"))
      (node (ref "U201") (pin "20") (pinfunction "VCC_20") (pintype "unspecified"))
      (node (ref "U202") (pin "28") (pinfunction "VCC_28") (pintype "unspecified"))
      (node (ref "U203") (pin "28") (pinfunction "VCC_28") (pintype "unspecified"))
      (node (ref "U204") (pin "20") (pinfunction "VCC_20") (pintype "unspecified"))
      (node (ref "U205") (pin "28") (pinfunction "VCC_28") (pintype "unspecified"))
      (node (ref "U206") (pin "28") (pinfunction "VCC_28") (pintype "output"))
      (node (ref "U207") (pin "28") (pinfunction "VCC_28") (pintype "unspecified"))
      (node (ref "U213") (pin "20") (pinfunction "VCC_20") (pintype "unspecified"))
      (node (ref "U300") (pin "139") (pinfunction "Vdd_139") (pintype "unspecified"))
      (node (ref "U300") (pin "153") (pinfunction "Vdd_153") (pintype "unspecified"))
      (node (ref "U300") (pin "19") (pinfunction "Vdd_19") (pintype "unspecified"))
      (node (ref "U300") (pin "39") (pinfunction "Vdd_39") (pintype "unspecified"))
      (node (ref "U300") (pin "40") (pinfunction "HALT/-TIP/_40") (pintype "unspecified"))
      (node (ref "U300") (pin "49") (pinfunction "Vdd_49") (pintype "unspecified"))
      (node (ref "U300") (pin "6") (pinfunction "Vdd_6") (pintype "unspecified"))
      (node (ref "U300") (pin "64") (pinfunction "Vdd_64") (pintype "unspecified"))
      (node (ref "U300") (pin "79") (pinfunction "Vdd_79") (pintype "unspecified"))
      (node (ref "U300") (pin "90") (pinfunction "BIG_LIT/_90") (pintype "unspecified"))
      (node (ref "U300") (pin "91") (pinfunction "BS_91") (pintype "unspecified"))
      (node (ref "U300") (pin "95") (pinfunction "BOFF/_95") (pintype "unspecified"))
      (node (ref "U300") (pin "99") (pinfunction "Vdd_99") (pintype "unspecified"))
      (node (ref "U301") (pin "14") (pinfunction "Vcc_14") (pintype "unspecified"))
      (node (ref "U302") (pin "1") (pinfunction "RD0#_1") (pintype "unspecified"))
      (node (ref "U302") (pin "10") (pinfunction "SD1#_10") (pintype "unspecified"))
      (node (ref "U302") (pin "11") (pinfunction "CP1_11") (pintype "unspecified"))
      (node (ref "U302") (pin "12") (pinfunction "D1_12") (pintype "unspecified"))
      (node (ref "U302") (pin "13") (pinfunction "RD1#_13") (pintype "unspecified"))
      (node (ref "U302") (pin "14") (pinfunction "VCC_14") (pintype "unspecified"))
      (node (ref "U302") (pin "4") (pinfunction "SD0#_4") (pintype "unspecified"))
      (node (ref "U303") (pin "28") (pinfunction "VCC_28") (pintype "unspecified"))
      (node (ref "U304") (pin "28") (pinfunction "VCC_28") (pintype "unspecified"))
      (node (ref "U305") (pin "28") (pinfunction "VCC_28") (pintype "unspecified"))
      (node (ref "U306") (pin "28") (pinfunction "VCC_28") (pintype "unspecified"))
      (node (ref "U307") (pin "14") (pinfunction "VCC_14") (pintype "unspecified"))
    )
    (net (code "232") (name "V12") (class "Default")
      (node (ref "C1") (pin "10") (pinfunction "+12V_10") (pintype "bidirectional"))
      (node (ref "C1C") (pin "1") (pinfunction "1_1") (pintype "input"))
      (node (ref "CN2") (pin "1") (pinfunction "1_1") (pintype "unspecified"))
      (node (ref "CN3") (pin "4") (pinfunction "12V_4") (pintype "unspecified"))
      (node (ref "CN4") (pin "2") (pinfunction "2_2") (pintype "unspecified"))
    )
    (net (code "233") (name "Z2D") (class "Default")
      (node (ref "FB504") (pin "2") (pinfunction "2_2") (pintype "unspecified"))
      (node (ref "U105") (pin "23") (pinfunction "CEBA_23") (pintype "unspecified"))
      (node (ref "U106") (pin "23") (pinfunction "CEBA_23") (pintype "unspecified"))
      (node (ref "U107") (pin "23") (pinfunction "CEBA_23") (pintype "unspecified"))
      (node (ref "U108") (pin "23") (pinfunction "CEBA_23") (pintype "unspecified"))
    )
    (net (code "234") (name "Z_7M") (class "Default")
      (node (ref "C1") (pin "92") (pinfunction "7M_Clock_92") (pintype "bidirectional"))
      (node (ref "U303") (pin "2") (pinfunction "CLK/I_2") (pintype "unspecified"))
    )
    (net (code "235") (name "Z_A2") (class "Default")
      (node (ref "C1") (pin "27") (pinfunction "A2_27") (pintype "output"))
      (node (ref "U103") (pin "13") (pinfunction "B5_13") (pintype "unspecified"))
    )
    (net (code "236") (name "Z_A3") (class "Default")
      (node (ref "C1") (pin "26") (pinfunction "A3_26") (pintype "bidirectional"))
      (node (ref "U103") (pin "14") (pinfunction "B4_14") (pintype "unspecified"))
    )
    (net (code "237") (name "Z_A4") (class "Default")
      (node (ref "C1") (pin "24") (pinfunction "A4_24") (pintype "bidirectional"))
      (node (ref "U103") (pin "15") (pinfunction "B3_15") (pintype "unspecified"))
    )
    (net (code "238") (name "Z_A5") (class "Default")
      (node (ref "C1") (pin "21") (pinfunction "A5_21") (pintype "output"))
      (node (ref "U103") (pin "16") (pinfunction "B2_16") (pintype "unspecified"))
    )
    (net (code "239") (name "Z_A6") (class "Default")
      (node (ref "C1") (pin "23") (pinfunction "A6_23") (pintype "output"))
      (node (ref "U103") (pin "17") (pinfunction "B1_17") (pintype "unspecified"))
    )
    (net (code "240") (name "Z_A7") (class "Default")
      (node (ref "C1") (pin "28") (pinfunction "A7_28") (pintype "bidirectional"))
      (node (ref "U103") (pin "18") (pinfunction "B0_18") (pintype "unspecified"))
    )
    (net (code "241") (name "Z_A8D0") (class "Default")
      (node (ref "C1") (pin "30") (pinfunction "A8+D0,A8_30") (pintype "bidirectional"))
      (node (ref "U102") (pin "15") (pinfunction "B7_15") (pintype "bidirectional"))
      (node (ref "U107") (pin "15") (pinfunction "B7_15") (pintype "bidirectional"))
    )
    (net (code "242") (name "Z_A9D1") (class "Default")
      (node (ref "C1") (pin "32") (pinfunction "A9+D1,A9_32") (pintype "bidirectional"))
      (node (ref "U102") (pin "16") (pinfunction "B6_16") (pintype "bidirectional"))
      (node (ref "U107") (pin "16") (pinfunction "B6_16") (pintype "bidirectional"))
    )
    (net (code "243") (name "Z_A10D2") (class "Default")
      (node (ref "C1") (pin "34") (pinfunction "A10+D2,A10_34") (pintype "bidirectional"))
      (node (ref "U102") (pin "17") (pinfunction "B5_17") (pintype "bidirectional"))
      (node (ref "U107") (pin "17") (pinfunction "B5_17") (pintype "bidirectional"))
    )
    (net (code "244") (name "Z_A11D3") (class "Default")
      (node (ref "C1") (pin "36") (pinfunction "A11+D3,A11_36") (pintype "bidirectional"))
      (node (ref "U102") (pin "18") (pinfunction "B4_18") (pintype "bidirectional"))
      (node (ref "U107") (pin "18") (pinfunction "B4_18") (pintype "bidirectional"))
    )
    (net (code "245") (name "Z_A12D4") (class "Default")
      (node (ref "C1") (pin "38") (pinfunction "A12+D4,A12_38") (pintype "bidirectional"))
      (node (ref "U102") (pin "19") (pinfunction "B3_19") (pintype "bidirectional"))
      (node (ref "U107") (pin "19") (pinfunction "B3_19") (pintype "bidirectional"))
    )
    (net (code "246") (name "Z_A13D5") (class "Default")
      (node (ref "C1") (pin "39") (pinfunction "A13+D5,A13_39") (pintype "unspecified"))
      (node (ref "U102") (pin "20") (pinfunction "B2_20") (pintype "bidirectional"))
      (node (ref "U107") (pin "20") (pinfunction "B2_20") (pintype "bidirectional"))
    )
    (net (code "247") (name "Z_A14D6") (class "Default")
      (node (ref "C1") (pin "41") (pinfunction "A14+D6,A14_41") (pintype "unspecified"))
      (node (ref "U102") (pin "21") (pinfunction "B1_21") (pintype "bidirectional"))
      (node (ref "U107") (pin "21") (pinfunction "B1_21") (pintype "bidirectional"))
    )
    (net (code "248") (name "Z_A15D7") (class "Default")
      (node (ref "C1") (pin "43") (pinfunction "A15+D7,A15_43") (pintype "unspecified"))
      (node (ref "U102") (pin "22") (pinfunction "B0_22") (pintype "bidirectional"))
      (node (ref "U107") (pin "22") (pinfunction "B0_22") (pintype "bidirectional"))
    )
    (net (code "249") (name "Z_A16D8") (class "Default")
      (node (ref "C1") (pin "45") (pinfunction "A16+D8,A16_45") (pintype "unspecified"))
      (node (ref "U101") (pin "15") (pinfunction "B7_15") (pintype "bidirectional"))
      (node (ref "U106") (pin "15") (pinfunction "B7_15") (pintype "bidirectional"))
    )
    (net (code "250") (name "Z_A17D9") (class "Default")
      (node (ref "C1") (pin "47") (pinfunction "A17+D9,A17_47") (pintype "unspecified"))
      (node (ref "U101") (pin "16") (pinfunction "B6_16") (pintype "bidirectional"))
      (node (ref "U106") (pin "16") (pinfunction "B6_16") (pintype "bidirectional"))
    )
    (net (code "251") (name "Z_A18D10") (class "Default")
      (node (ref "C1") (pin "52") (pinfunction "A18+D10,A18_52") (pintype "bidirectional"))
      (node (ref "U101") (pin "17") (pinfunction "B5_17") (pintype "bidirectional"))
      (node (ref "U106") (pin "17") (pinfunction "B5_17") (pintype "bidirectional"))
    )
    (net (code "252") (name "Z_A19D11") (class "Default")
      (node (ref "C1") (pin "54") (pinfunction "A19+D11,A19_54") (pintype "bidirectional"))
      (node (ref "U101") (pin "18") (pinfunction "B4_18") (pintype "bidirectional"))
      (node (ref "U106") (pin "18") (pinfunction "B4_18") (pintype "bidirectional"))
    )
    (net (code "253") (name "Z_A20D12") (class "Default")
      (node (ref "C1") (pin "56") (pinfunction "A20+D12,A20_56") (pintype "bidirectional"))
      (node (ref "U101") (pin "19") (pinfunction "B3_19") (pintype "bidirectional"))
      (node (ref "U106") (pin "19") (pinfunction "B3_19") (pintype "bidirectional"))
    )
    (net (code "254") (name "Z_A21D13") (class "Default")
      (node (ref "C1") (pin "58") (pinfunction "A21+D13,A21_58") (pintype "bidirectional"))
      (node (ref "U101") (pin "20") (pinfunction "B2_20") (pintype "bidirectional"))
      (node (ref "U106") (pin "20") (pinfunction "B2_20") (pintype "bidirectional"))
    )
    (net (code "255") (name "Z_A22D14") (class "Default")
      (node (ref "C1") (pin "57") (pinfunction "A22+D14,A22_57") (pintype "bidirectional"))
      (node (ref "U101") (pin "21") (pinfunction "B1_21") (pintype "bidirectional"))
      (node (ref "U106") (pin "21") (pinfunction "B1_21") (pintype "bidirectional"))
    )
    (net (code "256") (name "Z_A23D15") (class "Default")
      (node (ref "C1") (pin "59") (pinfunction "A23+D15,A23_59") (pintype "output"))
      (node (ref "U101") (pin "22") (pinfunction "B0_22") (pintype "bidirectional"))
      (node (ref "U106") (pin "22") (pinfunction "B0_22") (pintype "bidirectional"))
    )
    (net (code "257") (name "Z_A24D24") (class "Default")
      (node (ref "C1") (pin "80") (pinfunction "A24+D24,D8_80") (pintype "unspecified"))
      (node (ref "U100") (pin "15") (pinfunction "B7_15") (pintype "bidirectional"))
      (node (ref "U105") (pin "22") (pinfunction "B0_22") (pintype "bidirectional"))
    )
    (net (code "258") (name "Z_A25D25") (class "Default")
      (node (ref "C1") (pin "78") (pinfunction "A25+D25,D9_78") (pintype "unspecified"))
      (node (ref "U100") (pin "16") (pinfunction "B6_16") (pintype "bidirectional"))
      (node (ref "U105") (pin "21") (pinfunction "B1_21") (pintype "bidirectional"))
    )
    (net (code "259") (name "Z_A26D26") (class "Default")
      (node (ref "C1") (pin "76") (pinfunction "A26+D26,D10_76") (pintype "unspecified"))
      (node (ref "U100") (pin "17") (pinfunction "B5_17") (pintype "bidirectional"))
      (node (ref "U105") (pin "20") (pinfunction "B2_20") (pintype "bidirectional"))
    )
    (net (code "260") (name "Z_A27D27") (class "Default")
      (node (ref "C1") (pin "71") (pinfunction "A27+D27,D11_71") (pintype "unspecified"))
      (node (ref "U100") (pin "18") (pinfunction "B4_18") (pintype "bidirectional"))
      (node (ref "U105") (pin "19") (pinfunction "B3_19") (pintype "bidirectional"))
    )
    (net (code "261") (name "Z_A28D28") (class "Default")
      (node (ref "C1") (pin "69") (pinfunction "A28+D28,D12_69") (pintype "unspecified"))
      (node (ref "U100") (pin "19") (pinfunction "B3_19") (pintype "bidirectional"))
      (node (ref "U105") (pin "18") (pinfunction "B4_18") (pintype "bidirectional"))
    )
    (net (code "262") (name "Z_A29D29") (class "Default")
      (node (ref "C1") (pin "67") (pinfunction "A29+D29,D13_67") (pintype "unspecified"))
      (node (ref "U100") (pin "20") (pinfunction "B2_20") (pintype "bidirectional"))
      (node (ref "U105") (pin "17") (pinfunction "B5_17") (pintype "bidirectional"))
    )
    (net (code "263") (name "Z_A30D30") (class "Default")
      (node (ref "C1") (pin "65") (pinfunction "A30+D30,D14_65") (pintype "unspecified"))
      (node (ref "U100") (pin "21") (pinfunction "B1_21") (pintype "bidirectional"))
      (node (ref "U105") (pin "16") (pinfunction "B6_16") (pintype "bidirectional"))
    )
    (net (code "264") (name "Z_A31D31") (class "Default")
      (node (ref "C1") (pin "63") (pinfunction "A31+D31,D15_63") (pintype "bidirectional"))
      (node (ref "U100") (pin "22") (pinfunction "B0_22") (pintype "bidirectional"))
      (node (ref "U105") (pin "15") (pinfunction "B7_15") (pintype "bidirectional"))
    )
    (net (code "265") (name "Z_BERR") (class "Default")
      (node (ref "C1") (pin "46") (pinfunction "/BERR_46") (pintype "bidirectional"))
      (node (ref "U307") (pin "5") (pinfunction "3A_5") (pintype "unspecified"))
    )
    (net (code "266") (name "Z_BGn") (class "Default")
      (node (ref "C1") (pin "64") (pinfunction "/BGn_64") (pintype "bidirectional"))
      (node (ref "U303") (pin "5") (pinfunction "I_5") (pintype "unspecified"))
    )
    (net (code "267") (name "Z_BRn") (class "Default")
      (node (ref "C1") (pin "60") (pinfunction "/BRn_60") (pintype "bidirectional"))
      (node (ref "U303") (pin "25") (pinfunction "IOQ_25") (pintype "unspecified"))
    )
    (net (code "268") (name "Z_CFGIN") (class "Default")
      (node (ref "C1") (pin "12") (pinfunction "/CFGINn_12") (pintype "bidirectional"))
      (node (ref "U202") (pin "18") (pinfunction "IOQ_18") (pintype "unspecified"))
    )
    (net (code "269") (name "Z_CFGOUT") (class "Default")
      (node (ref "C1") (pin "11") (pinfunction "/CFGOUTn_11") (pintype "unspecified"))
      (node (ref "U200") (pin "1") (pinfunction "OE#_1") (pintype "unspecified"))
      (node (ref "U202") (pin "21") (pinfunction "IOQ_21") (pintype "unspecified"))
      (node (ref "U205") (pin "13") (pinfunction "I_13") (pintype "unspecified"))
      (node (ref "U207") (pin "16") (pinfunction "I_16") (pintype "unspecified"))
    )
    (net (code "270") (name "Z_CINH") (class "Default")
      (node (ref "C1") (pin "17") (pinfunction "/CINH,/OVR_17") (pintype "bidirectional"))
      (node (ref "U202") (pin "24") (pinfunction "IOQ_24") (pintype "unspecified"))
    )
    (net (code "271") (name "Z_D16") (class "Default")
      (node (ref "C1") (pin "75") (pinfunction "RSVD+D16,D0_75") (pintype "unspecified"))
      (node (ref "U108") (pin "22") (pinfunction "B0_22") (pintype "bidirectional"))
    )
    (net (code "272") (name "Z_D17") (class "Default")
      (node (ref "C1") (pin "77") (pinfunction "RSVD+D17,D1_77") (pintype "unspecified"))
      (node (ref "U108") (pin "21") (pinfunction "B1_21") (pintype "bidirectional"))
    )
    (net (code "273") (name "Z_D18") (class "Default")
      (node (ref "C1") (pin "79") (pinfunction "RSVD+D18,D2_79") (pintype "output"))
      (node (ref "U108") (pin "20") (pinfunction "B2_20") (pintype "bidirectional"))
    )
    (net (code "274") (name "Z_D19") (class "Default")
      (node (ref "C1") (pin "81") (pinfunction "RSVD+D19,D3_81") (pintype "unspecified"))
      (node (ref "U108") (pin "19") (pinfunction "B3_19") (pintype "bidirectional"))
    )
    (net (code "275") (name "Z_D20") (class "Default")
      (node (ref "C1") (pin "83") (pinfunction "RSVD+D20,D4_83") (pintype "output"))
      (node (ref "U108") (pin "18") (pinfunction "B4_18") (pintype "bidirectional"))
    )
    (net (code "276") (name "Z_D21") (class "Default")
      (node (ref "C1") (pin "86") (pinfunction "RSVD+D21,D5_86") (pintype "bidirectional"))
      (node (ref "U108") (pin "17") (pinfunction "B5_17") (pintype "bidirectional"))
    )
    (net (code "277") (name "Z_D22") (class "Default")
      (node (ref "C1") (pin "84") (pinfunction "RSVD+D22,D6_84") (pintype "output"))
      (node (ref "U108") (pin "16") (pinfunction "B6_16") (pintype "bidirectional"))
    )
    (net (code "278") (name "Z_D23") (class "Default")
      (node (ref "C1") (pin "82") (pinfunction "RSVD+D23,D7_82") (pintype "bidirectional"))
      (node (ref "U108") (pin "15") (pinfunction "B7_15") (pintype "bidirectional"))
    )
    (net (code "279") (name "Z_DOE") (class "Default")
      (node (ref "C1") (pin "93") (pinfunction "DOE_93") (pintype "unspecified"))
      (node (ref "U109") (pin "16") (pinfunction "B2_16") (pintype "unspecified"))
    )
    (net (code "280") (name "Z_DS0") (class "Default")
      (node (ref "C1") (pin "51") (pinfunction "/DS0,/VMA_51") (pintype "unspecified"))
      (node (ref "U109") (pin "11") (pinfunction "B7_11") (pintype "unspecified"))
    )
    (net (code "281") (name "Z_DS1") (class "Default")
      (node (ref "C1") (pin "98") (pinfunction "/DS1,NC_98") (pintype "bidirectional"))
      (node (ref "U109") (pin "12") (pinfunction "B6_12") (pintype "unspecified"))
    )
    (net (code "282") (name "Z_DS2") (class "Default")
      (node (ref "C1") (pin "70") (pinfunction "/DS2,/LDS_70") (pintype "unspecified"))
      (node (ref "FB508") (pin "2") (pinfunction "2_2") (pintype "unspecified"))
    )
    (net (code "283") (name "Z_DS3") (class "Default")
      (node (ref "C1") (pin "72") (pinfunction "/DS3,/UDS_72") (pintype "unspecified"))
      (node (ref "FB507") (pin "2") (pinfunction "2_2") (pintype "unspecified"))
    )
    (net (code "284") (name "Z_DTACK") (class "Default")
      (node (ref "C1") (pin "66") (pinfunction "/DTACK_66") (pintype "unspecified"))
      (node (ref "C306B") (pin "1") (pinfunction "1_1") (pintype "input"))
      (node (ref "U205") (pin "20") (pinfunction "IOQ_20") (pintype "unspecified"))
      (node (ref "U306") (pin "9") (pinfunction "I_9") (pintype "unspecified"))
    )
    (net (code "285") (name "Z_FC0") (class "Default")
      (node (ref "C1") (pin "31") (pinfunction "FC0_31") (pintype "unspecified"))
      (node (ref "U109") (pin "17") (pinfunction "B1_17") (pintype "unspecified"))
    )
    (net (code "286") (name "Z_FC1") (class "Default")
      (node (ref "C1") (pin "33") (pinfunction "FC1_33") (pintype "unspecified"))
      (node (ref "U109") (pin "18") (pinfunction "B0_18") (pintype "unspecified"))
    )
    (net (code "287") (name "Z_FC2") (class "Default")
      (node (ref "C1") (pin "35") (pinfunction "FC2_35") (pintype "unspecified"))
      (node (ref "U103") (pin "12") (pinfunction "B6_12") (pintype "unspecified"))
    )
    (net (code "288") (name "Z_FCS") (class "Default")
      (node (ref "C1") (pin "97") (pinfunction "/FCS,NC_97") (pintype "unspecified"))
      (node (ref "FB501") (pin "2") (pinfunction "2_2") (pintype "unspecified"))
      (node (ref "U305") (pin "21") (pinfunction "IOQ_21") (pintype "unspecified"))
    )
    (net (code "289") (name "Z_INT2") (class "Default")
      (node (ref "C1") (pin "19") (pinfunction "/INT2_19") (pintype "bidirectional"))
      (node (ref "U207") (pin "27") (pinfunction "IOQ_27") (pintype "unspecified"))
    )
    (net (code "290") (name "Z_IORST") (class "Default")
      (node (ref "C1") (pin "94") (pinfunction "/IORST,/BUSRST_94") (pintype "bidirectional"))
      (node (ref "U307") (pin "9") (pinfunction "4A_9") (pintype "unspecified"))
    )
    (net (code "291") (name "Z_LOCK") (class "Default")
      (node (ref "C1") (pin "29") (pinfunction "/LOCK,A1_29") (pintype "unspecified"))
      (node (ref "U203") (pin "6") (pinfunction "I_6") (pintype "unspecified"))
    )
    (net (code "292") (name "Z_MTACK") (class "Default")
      (node (ref "C1") (pin "48") (pinfunction "/MTACK,/VPA_48") (pintype "bidirectional"))
      (node (ref "U306") (pin "5") (pinfunction "I_5") (pintype "unspecified"))
    )
    (net (code "293") (name "Z_MTCR") (class "Default")
      (node (ref "C1") (pin "18") (pinfunction "/MTCR,XRDY_18") (pintype "bidirectional"))
      (node (ref "U109") (pin "15") (pinfunction "B3_15") (pintype "unspecified"))
    )
    (net (code "294") (name "Z_READ") (class "Default")
      (node (ref "C1") (pin "68") (pinfunction "READ_68") (pintype "unspecified"))
      (node (ref "U103") (pin "11") (pinfunction "B7_11") (pintype "unspecified"))
    )
    (net (code "295") (name "Z_SENSEZ3") (class "Default")
      (node (ref "C1") (pin "91") (pinfunction "SenseZ3,GND_91") (pintype "output"))
      (node (ref "R100A") (pin "1") (pinfunction "1_1") (pintype "input"))
      (node (ref "U202") (pin "20") (pinfunction "IOQ_20") (pintype "unspecified"))
    )
    (net (code "296") (name "Z_SLAVE") (class "Default")
      (node (ref "C1") (pin "09") (pinfunction "/SLAVEn_09") (pintype "bidirectional"))
      (node (ref "U202") (pin "26") (pinfunction "IOQ_26") (pintype "unspecified"))
      (node (ref "U203") (pin "20") (pinfunction "IOQ_20") (pintype "unspecified"))
      (node (ref "U205") (pin "3") (pinfunction "I_3") (pintype "unspecified"))
      (node (ref "U207") (pin "13") (pinfunction "I_13") (pintype "unspecified"))
      (node (ref "U303") (pin "7") (pinfunction "I_7") (pintype "unspecified"))
    )
    (net (code "297") (name "unconnected-(C1--5V-Pad08)") (class "Default")
      (node (ref "C1") (pin "08") (pinfunction "-5V_08") (pintype "bidirectional+no_connect"))
    )
    (net (code "298") (name "unconnected-(C1--12V-Pad20)") (class "Default")
      (node (ref "C1") (pin "20") (pinfunction "-12V_20") (pintype "unspecified+no_connect"))
    )
    (net (code "299") (name "unconnected-(C1-CDAC_Clock-Pad15)") (class "Default")
      (node (ref "C1") (pin "15") (pinfunction "CDAC_Clock_15") (pintype "unspecified+no_connect"))
    )
    (net (code "300") (name "unconnected-(C1-E_Clock-Pad50)") (class "Default")
      (node (ref "C1") (pin "50") (pinfunction "E_Clock_50") (pintype "bidirectional+no_connect"))
    )
    (net (code "301") (name "unconnected-(C1-RSVD,{slash}EINT1-Pad96)") (class "Default")
      (node (ref "C1") (pin "96") (pinfunction "RSVD,/EINT1_96") (pintype "bidirectional+no_connect"))
    )
    (net (code "302") (name "unconnected-(C1-RSVD,{slash}EINT4-Pad44)") (class "Default")
      (node (ref "C1") (pin "44") (pinfunction "RSVD,/EINT4_44") (pintype "bidirectional+no_connect"))
    )
    (net (code "303") (name "unconnected-(C1-RSVD,{slash}EINT5-Pad42)") (class "Default")
      (node (ref "C1") (pin "42") (pinfunction "RSVD,/EINT5_42") (pintype "bidirectional+no_connect"))
    )
    (net (code "304") (name "unconnected-(C1-RSVD,{slash}EINT7-Pad40)") (class "Default")
      (node (ref "C1") (pin "40") (pinfunction "RSVD,/EINT7_40") (pintype "bidirectional+no_connect"))
    )
    (net (code "305") (name "unconnected-(C1-{slash}BCLR,{slash}GBG-Pad95)") (class "Default")
      (node (ref "C1") (pin "95") (pinfunction "/BCLR,/GBG_95") (pintype "bidirectional+no_connect"))
    )
    (net (code "306") (name "unconnected-(C1-{slash}BGACK-Pad62)") (class "Default")
      (node (ref "C1") (pin "62") (pinfunction "/BGACK_62") (pintype "bidirectional+no_connect"))
    )
    (net (code "307") (name "unconnected-(C1-{slash}C1_Clock-Pad16)") (class "Default")
      (node (ref "C1") (pin "16") (pinfunction "/C1_Clock_16") (pintype "bidirectional+no_connect"))
    )
    (net (code "308") (name "unconnected-(C1-{slash}C3_Clock-Pad14)") (class "Default")
      (node (ref "C1") (pin "14") (pinfunction "/C3_Clock_14") (pintype "bidirectional+no_connect"))
    )
    (net (code "309") (name "unconnected-(C1-{slash}CCS,{slash}AS-Pad74)") (class "Default")
      (node (ref "C1") (pin "74") (pinfunction "/CCS,/AS_74") (pintype "unspecified+no_connect"))
    )
    (net (code "310") (name "unconnected-(C1-{slash}HLT-Pad55)") (class "Default")
      (node (ref "C1") (pin "55") (pinfunction "/HLT_55") (pintype "output+no_connect"))
    )
    (net (code "311") (name "unconnected-(C1-{slash}INT6-Pad22)") (class "Default")
      (node (ref "C1") (pin "22") (pinfunction "/INT6_22") (pintype "output+no_connect"))
    )
    (net (code "312") (name "unconnected-(C1-{slash}OWN-Pad07)") (class "Default")
      (node (ref "C1") (pin "07") (pinfunction "/OWN_07") (pintype "unspecified+no_connect"))
    )
    (net (code "313") (name "unconnected-(C1-{slash}RST-Pad53)") (class "Default")
      (node (ref "C1") (pin "53") (pinfunction "/RST_53") (pintype "unspecified+no_connect"))
    )
    (net (code "314") (name "unconnected-(CN4-Pad1)") (class "Default")
      (node (ref "CN4") (pin "1") (pinfunction "1_1") (pintype "unspecified+no_connect"))
    )
    (net (code "315") (name "unconnected-(CN309-Pad25)") (class "Default")
      (node (ref "CN309") (pin "25") (pinfunction "25_25") (pintype "unspecified+no_connect"))
    )
    (net (code "316") (name "unconnected-(CN309-Pad34)") (class "Default")
      (node (ref "CN309") (pin "34") (pinfunction "34_34") (pintype "unspecified+no_connect"))
    )
    (net (code "317") (name "unconnected-(CN310-NC-Pad12)") (class "Default")
      (node (ref "CN310") (pin "12") (pinfunction "NC_12") (pintype "unspecified+no_connect"))
    )
    (net (code "318") (name "unconnected-(CN310-NC-Pad13)") (class "Default")
      (node (ref "CN310") (pin "13") (pinfunction "NC_13") (pintype "unspecified+no_connect"))
    )
    (net (code "319") (name "unconnected-(CN310-NC-Pad14)") (class "Default")
      (node (ref "CN310") (pin "14") (pinfunction "NC_14") (pintype "unspecified+no_connect"))
    )
    (net (code "320") (name "unconnected-(CN310-RSVD-Pad37)") (class "Default")
      (node (ref "CN310") (pin "37") (pinfunction "RSVD_37") (pintype "unspecified+no_connect"))
    )
    (net (code "321") (name "unconnected-(CN310-RSVD-Pad39)") (class "Default")
      (node (ref "CN310") (pin "39") (pinfunction "RSVD_39") (pintype "unspecified+no_connect"))
    )
    (net (code "322") (name "unconnected-(CN400-Pad25)") (class "Default")
      (node (ref "CN400") (pin "25") (pinfunction "25_25") (pintype "unspecified+no_connect"))
    )
    (net (code "323") (name "unconnected-(U202-IOQ-Pad25)") (class "Default")
      (node (ref "U202") (pin "25") (pinfunction "IOQ_25") (pintype "unspecified+no_connect"))
    )
    (net (code "324") (name "unconnected-(U202-NC-Pad1)") (class "Default")
      (node (ref "U202") (pin "1") (pinfunction "NC_1") (pintype "unspecified+no_connect"))
    )
    (net (code "325") (name "unconnected-(U202-NC-Pad8)") (class "Default")
      (node (ref "U202") (pin "8") (pinfunction "NC_8") (pintype "unspecified+no_connect"))
    )
    (net (code "326") (name "unconnected-(U202-NC-Pad15)") (class "Default")
      (node (ref "U202") (pin "15") (pinfunction "NC_15") (pintype "unspecified+no_connect"))
    )
    (net (code "327") (name "unconnected-(U202-NC-Pad22)") (class "Default")
      (node (ref "U202") (pin "22") (pinfunction "NC_22") (pintype "unspecified+no_connect"))
    )
    (net (code "328") (name "unconnected-(U203-IOQ-Pad18)") (class "Default")
      (node (ref "U203") (pin "18") (pinfunction "IOQ_18") (pintype "unspecified+no_connect"))
    )
    (net (code "329") (name "unconnected-(U203-IOQ-Pad19)") (class "Default")
      (node (ref "U203") (pin "19") (pinfunction "IOQ_19") (pintype "unspecified+no_connect"))
    )
    (net (code "330") (name "unconnected-(U203-IOQ-Pad21)") (class "Default")
      (node (ref "U203") (pin "21") (pinfunction "IOQ_21") (pintype "unspecified+no_connect"))
    )
    (net (code "331") (name "unconnected-(U203-NC-Pad1)") (class "Default")
      (node (ref "U203") (pin "1") (pinfunction "NC_1") (pintype "unspecified+no_connect"))
    )
    (net (code "332") (name "unconnected-(U203-NC-Pad8)") (class "Default")
      (node (ref "U203") (pin "8") (pinfunction "NC_8") (pintype "unspecified+no_connect"))
    )
    (net (code "333") (name "unconnected-(U203-NC-Pad15)") (class "Default")
      (node (ref "U203") (pin "15") (pinfunction "NC_15") (pintype "unspecified+no_connect"))
    )
    (net (code "334") (name "unconnected-(U203-NC-Pad22)") (class "Default")
      (node (ref "U203") (pin "22") (pinfunction "NC_22") (pintype "unspecified+no_connect"))
    )
    (net (code "335") (name "unconnected-(U205-NC-Pad1)") (class "Default")
      (node (ref "U205") (pin "1") (pinfunction "NC_1") (pintype "unspecified+no_connect"))
    )
    (net (code "336") (name "unconnected-(U205-NC-Pad8)") (class "Default")
      (node (ref "U205") (pin "8") (pinfunction "NC_8") (pintype "unspecified+no_connect"))
    )
    (net (code "337") (name "unconnected-(U205-NC-Pad15)") (class "Default")
      (node (ref "U205") (pin "15") (pinfunction "NC_15") (pintype "unspecified+no_connect"))
    )
    (net (code "338") (name "unconnected-(U205-NC-Pad22)") (class "Default")
      (node (ref "U205") (pin "22") (pinfunction "NC_22") (pintype "unspecified+no_connect"))
    )
    (net (code "339") (name "unconnected-(U207-I-Pad3)") (class "Default")
      (node (ref "U207") (pin "3") (pinfunction "I_3") (pintype "unspecified+no_connect"))
    )
    (net (code "340") (name "unconnected-(U207-I-Pad4)") (class "Default")
      (node (ref "U207") (pin "4") (pinfunction "I_4") (pintype "unspecified+no_connect"))
    )
    (net (code "341") (name "unconnected-(U207-I-Pad5)") (class "Default")
      (node (ref "U207") (pin "5") (pinfunction "I_5") (pintype "unspecified+no_connect"))
    )
    (net (code "342") (name "unconnected-(U207-IOQ-Pad17)") (class "Default")
      (node (ref "U207") (pin "17") (pinfunction "IOQ_17") (pintype "unspecified+no_connect"))
    )
    (net (code "343") (name "unconnected-(U207-IOQ-Pad18)") (class "Default")
      (node (ref "U207") (pin "18") (pinfunction "IOQ_18") (pintype "unspecified+no_connect"))
    )
    (net (code "344") (name "unconnected-(U207-IOQ-Pad20)") (class "Default")
      (node (ref "U207") (pin "20") (pinfunction "IOQ_20") (pintype "unspecified+no_connect"))
    )
    (net (code "345") (name "unconnected-(U207-IOQ-Pad21)") (class "Default")
      (node (ref "U207") (pin "21") (pinfunction "IOQ_21") (pintype "unspecified+no_connect"))
    )
    (net (code "346") (name "unconnected-(U207-IOQ-Pad23)") (class "Default")
      (node (ref "U207") (pin "23") (pinfunction "IOQ_23") (pintype "unspecified+no_connect"))
    )
    (net (code "347") (name "unconnected-(U207-IOQ-Pad25)") (class "Default")
      (node (ref "U207") (pin "25") (pinfunction "IOQ_25") (pintype "unspecified+no_connect"))
    )
    (net (code "348") (name "unconnected-(U207-NC-Pad1)") (class "Default")
      (node (ref "U207") (pin "1") (pinfunction "NC_1") (pintype "unspecified+no_connect"))
    )
    (net (code "349") (name "unconnected-(U207-NC-Pad8)") (class "Default")
      (node (ref "U207") (pin "8") (pinfunction "NC_8") (pintype "unspecified+no_connect"))
    )
    (net (code "350") (name "unconnected-(U207-NC-Pad15)") (class "Default")
      (node (ref "U207") (pin "15") (pinfunction "NC_15") (pintype "unspecified+no_connect"))
    )
    (net (code "351") (name "unconnected-(U207-NC-Pad22)") (class "Default")
      (node (ref "U207") (pin "22") (pinfunction "NC_22") (pintype "unspecified+no_connect"))
    )
    (net (code "352") (name "unconnected-(U300-BSYDIR-Pad108)") (class "Default")
      (node (ref "U300") (pin "108") (pinfunction "BSYDIR_108") (pintype "unspecified+no_connect"))
    )
    (net (code "353") (name "unconnected-(U300-FETCH{slash}-Pad97)") (class "Default")
      (node (ref "U300") (pin "97") (pinfunction "FETCH/_97") (pintype "unspecified+no_connect"))
    )
    (net (code "354") (name "unconnected-(U300-IGS-Pad104)") (class "Default")
      (node (ref "U300") (pin "104") (pinfunction "IGS_104") (pintype "unspecified+no_connect"))
    )
    (net (code "355") (name "unconnected-(U300-RSTDIR-Pad107)") (class "Default")
      (node (ref "U300") (pin "107") (pinfunction "RSTDIR_107") (pintype "unspecified+no_connect"))
    )
    (net (code "356") (name "unconnected-(U300-SC0-Pad88)") (class "Default")
      (node (ref "U300") (pin "88") (pinfunction "SC0_88") (pintype "unspecified+no_connect"))
    )
    (net (code "357") (name "unconnected-(U300-SC1-Pad89)") (class "Default")
      (node (ref "U300") (pin "89") (pinfunction "SC1_89") (pintype "unspecified+no_connect"))
    )
    (net (code "358") (name "unconnected-(U300-SDIR0-Pad142)") (class "Default")
      (node (ref "U300") (pin "142") (pinfunction "SDIR0_142") (pintype "unspecified+no_connect"))
    )
    (net (code "359") (name "unconnected-(U300-SDIR1-Pad141)") (class "Default")
      (node (ref "U300") (pin "141") (pinfunction "SDIR1_141") (pintype "unspecified+no_connect"))
    )
    (net (code "360") (name "unconnected-(U300-SDIR2-Pad140)") (class "Default")
      (node (ref "U300") (pin "140") (pinfunction "SDIR2_140") (pintype "unspecified+no_connect"))
    )
    (net (code "361") (name "unconnected-(U300-SDIR3-Pad138)") (class "Default")
      (node (ref "U300") (pin "138") (pinfunction "SDIR3_138") (pintype "unspecified+no_connect"))
    )
    (net (code "362") (name "unconnected-(U300-SDIR4-Pad137)") (class "Default")
      (node (ref "U300") (pin "137") (pinfunction "SDIR4_137") (pintype "unspecified+no_connect"))
    )
    (net (code "363") (name "unconnected-(U300-SDIR5-Pad135)") (class "Default")
      (node (ref "U300") (pin "135") (pinfunction "SDIR5_135") (pintype "unspecified+no_connect"))
    )
    (net (code "364") (name "unconnected-(U300-SDIR6-Pad134)") (class "Default")
      (node (ref "U300") (pin "134") (pinfunction "SDIR6_134") (pintype "unspecified+no_connect"))
    )
    (net (code "365") (name "unconnected-(U300-SDIR7-Pad133)") (class "Default")
      (node (ref "U300") (pin "133") (pinfunction "SDIR7_133") (pintype "unspecified+no_connect"))
    )
    (net (code "366") (name "unconnected-(U300-SDIRP-Pad132)") (class "Default")
      (node (ref "U300") (pin "132") (pinfunction "SDIRP_132") (pintype "unspecified+no_connect"))
    )
    (net (code "367") (name "unconnected-(U300-SELDIR-Pad106)") (class "Default")
      (node (ref "U300") (pin "106") (pinfunction "SELDIR_106") (pintype "unspecified+no_connect"))
    )
    (net (code "368") (name "unconnected-(U300-TGS-Pad103)") (class "Default")
      (node (ref "U300") (pin "103") (pinfunction "TGS_103") (pintype "unspecified+no_connect"))
    )
    (net (code "369") (name "unconnected-(U300-UPS0-TT0{slash}-Pad34)") (class "Default")
      (node (ref "U300") (pin "34") (pinfunction "UPS0-TT0/_34") (pintype "unspecified+no_connect"))
    )
    (net (code "370") (name "unconnected-(U301-N.C-Pad1)") (class "Default")
      (node (ref "U301") (pin "1") (pinfunction "N.C_1") (pintype "unspecified+no_connect"))
    )
    (net (code "371") (name "unconnected-(U302-Q1#-Pad8)") (class "Default")
      (node (ref "U302") (pin "8") (pinfunction "Q1#_8") (pintype "unspecified+no_connect"))
    )
    (net (code "372") (name "unconnected-(U302-Q1-Pad9)") (class "Default")
      (node (ref "U302") (pin "9") (pinfunction "Q1_9") (pintype "unspecified+no_connect"))
    )
    (net (code "373") (name "unconnected-(U303-I-Pad13)") (class "Default")
      (node (ref "U303") (pin "13") (pinfunction "I_13") (pintype "unspecified+no_connect"))
    )
    (net (code "374") (name "unconnected-(U303-I-Pad16)") (class "Default")
      (node (ref "U303") (pin "16") (pinfunction "I_16") (pintype "unspecified+no_connect"))
    )
    (net (code "375") (name "unconnected-(U303-IOQ-Pad17)") (class "Default")
      (node (ref "U303") (pin "17") (pinfunction "IOQ_17") (pintype "unspecified+no_connect"))
    )
    (net (code "376") (name "unconnected-(U303-IOQ-Pad18)") (class "Default")
      (node (ref "U303") (pin "18") (pinfunction "IOQ_18") (pintype "unspecified+no_connect"))
    )
    (net (code "377") (name "unconnected-(U303-IOQ-Pad19)") (class "Default")
      (node (ref "U303") (pin "19") (pinfunction "IOQ_19") (pintype "unspecified+no_connect"))
    )
    (net (code "378") (name "unconnected-(U303-IOQ-Pad23)") (class "Default")
      (node (ref "U303") (pin "23") (pinfunction "IOQ_23") (pintype "unspecified+no_connect"))
    )
    (net (code "379") (name "unconnected-(U303-IOQ-Pad24)") (class "Default")
      (node (ref "U303") (pin "24") (pinfunction "IOQ_24") (pintype "unspecified+no_connect"))
    )
    (net (code "380") (name "unconnected-(U303-IOQ-Pad26)") (class "Default")
      (node (ref "U303") (pin "26") (pinfunction "IOQ_26") (pintype "unspecified+no_connect"))
    )
    (net (code "381") (name "unconnected-(U303-NC-Pad1)") (class "Default")
      (node (ref "U303") (pin "1") (pinfunction "NC_1") (pintype "unspecified+no_connect"))
    )
    (net (code "382") (name "unconnected-(U303-NC-Pad8)") (class "Default")
      (node (ref "U303") (pin "8") (pinfunction "NC_8") (pintype "unspecified+no_connect"))
    )
    (net (code "383") (name "unconnected-(U303-NC-Pad15)") (class "Default")
      (node (ref "U303") (pin "15") (pinfunction "NC_15") (pintype "unspecified+no_connect"))
    )
    (net (code "384") (name "unconnected-(U303-NC-Pad22)") (class "Default")
      (node (ref "U303") (pin "22") (pinfunction "NC_22") (pintype "unspecified+no_connect"))
    )
    (net (code "385") (name "unconnected-(U304-I-Pad16)") (class "Default")
      (node (ref "U304") (pin "16") (pinfunction "I_16") (pintype "unspecified+no_connect"))
    )
    (net (code "386") (name "unconnected-(U304-IOQ-Pad17)") (class "Default")
      (node (ref "U304") (pin "17") (pinfunction "IOQ_17") (pintype "unspecified+no_connect"))
    )
    (net (code "387") (name "unconnected-(U304-IOQ-Pad18)") (class "Default")
      (node (ref "U304") (pin "18") (pinfunction "IOQ_18") (pintype "unspecified+no_connect"))
    )
    (net (code "388") (name "unconnected-(U304-IOQ-Pad23)") (class "Default")
      (node (ref "U304") (pin "23") (pinfunction "IOQ_23") (pintype "unspecified+no_connect"))
    )
    (net (code "389") (name "unconnected-(U304-NC-Pad1)") (class "Default")
      (node (ref "U304") (pin "1") (pinfunction "NC_1") (pintype "unspecified+no_connect"))
    )
    (net (code "390") (name "unconnected-(U304-NC-Pad8)") (class "Default")
      (node (ref "U304") (pin "8") (pinfunction "NC_8") (pintype "unspecified+no_connect"))
    )
    (net (code "391") (name "unconnected-(U304-NC-Pad15)") (class "Default")
      (node (ref "U304") (pin "15") (pinfunction "NC_15") (pintype "unspecified+no_connect"))
    )
    (net (code "392") (name "unconnected-(U304-NC-Pad22)") (class "Default")
      (node (ref "U304") (pin "22") (pinfunction "NC_22") (pintype "unspecified+no_connect"))
    )
    (net (code "393") (name "unconnected-(U305-I-Pad11)") (class "Default")
      (node (ref "U305") (pin "11") (pinfunction "I_11") (pintype "unspecified+no_connect"))
    )
    (net (code "394") (name "unconnected-(U305-I-Pad12)") (class "Default")
      (node (ref "U305") (pin "12") (pinfunction "I_12") (pintype "unspecified+no_connect"))
    )
    (net (code "395") (name "unconnected-(U305-IOQ-Pad17)") (class "Default")
      (node (ref "U305") (pin "17") (pinfunction "IOQ_17") (pintype "unspecified+no_connect"))
    )
    (net (code "396") (name "unconnected-(U305-IOQ-Pad18)") (class "Default")
      (node (ref "U305") (pin "18") (pinfunction "IOQ_18") (pintype "unspecified+no_connect"))
    )
    (net (code "397") (name "unconnected-(U305-NC-Pad1)") (class "Default")
      (node (ref "U305") (pin "1") (pinfunction "NC_1") (pintype "unspecified+no_connect"))
    )
    (net (code "398") (name "unconnected-(U305-NC-Pad8)") (class "Default")
      (node (ref "U305") (pin "8") (pinfunction "NC_8") (pintype "unspecified+no_connect"))
    )
    (net (code "399") (name "unconnected-(U305-NC-Pad15)") (class "Default")
      (node (ref "U305") (pin "15") (pinfunction "NC_15") (pintype "unspecified+no_connect"))
    )
    (net (code "400") (name "unconnected-(U305-NC-Pad22)") (class "Default")
      (node (ref "U305") (pin "22") (pinfunction "NC_22") (pintype "unspecified+no_connect"))
    )
    (net (code "401") (name "unconnected-(U306-I-Pad16)") (class "Default")
      (node (ref "U306") (pin "16") (pinfunction "I_16") (pintype "unspecified+no_connect"))
    )
    (net (code "402") (name "unconnected-(U306-IOQ-Pad18)") (class "Default")
      (node (ref "U306") (pin "18") (pinfunction "IOQ_18") (pintype "unspecified+no_connect"))
    )
    (net (code "403") (name "unconnected-(U306-IOQ-Pad24)") (class "Default")
      (node (ref "U306") (pin "24") (pinfunction "IOQ_24") (pintype "unspecified+no_connect"))
    )
    (net (code "404") (name "unconnected-(U306-IOQ-Pad26)") (class "Default")
      (node (ref "U306") (pin "26") (pinfunction "IOQ_26") (pintype "unspecified+no_connect"))
    )
    (net (code "405") (name "unconnected-(U306-NC-Pad1)") (class "Default")
      (node (ref "U306") (pin "1") (pinfunction "NC_1") (pintype "unspecified+no_connect"))
    )
    (net (code "406") (name "unconnected-(U306-NC-Pad8)") (class "Default")
      (node (ref "U306") (pin "8") (pinfunction "NC_8") (pintype "unspecified+no_connect"))
    )
    (net (code "407") (name "unconnected-(U306-NC-Pad15)") (class "Default")
      (node (ref "U306") (pin "15") (pinfunction "NC_15") (pintype "unspecified+no_connect"))
    )
    (net (code "408") (name "unconnected-(U306-NC-Pad22)") (class "Default")
      (node (ref "U306") (pin "22") (pinfunction "NC_22") (pintype "unspecified+no_connect"))
    )
    (net (code "409") (name "unconnected-(U307-5Y-Pad10)") (class "Default")
      (node (ref "U307") (pin "10") (pinfunction "5Y_10") (pintype "unspecified+no_connect"))
    )
    (net (code "410") (name "unconnected-(U307-6Y-Pad12)") (class "Default")
      (node (ref "U307") (pin "12") (pinfunction "6Y_12") (pintype "unspecified+no_connect"))
    )
    (net (code "411") (name "unconnected-(U310-NC-Pad14)") (class "Default")
      (node (ref "U310") (pin "14") (pinfunction "NC_14") (pintype "unspecified+no_connect"))
    )
    (net (code "412") (name "unconnected-(U311-NC-Pad14)") (class "Default")
      (node (ref "U311") (pin "14") (pinfunction "NC_14") (pintype "unspecified+no_connect"))
    )
    (net (code "413") (name "unconnected-(U400-NC-Pad14)") (class "Default")
      (node (ref "U400") (pin "14") (pinfunction "NC_14") (pintype "unspecified+no_connect"))
    )
    (net (code "414") (name "unconnected-(U400-PD#-Pad16)") (class "Default")
      (node (ref "U400") (pin "16") (pinfunction "PD#_16") (pintype "unspecified+no_connect"))
    )
    (net (code "415") (name "unconnected-(U401-NC-Pad14)") (class "Default")
      (node (ref "U401") (pin "14") (pinfunction "NC_14") (pintype "unspecified+no_connect"))
    )
    (net (code "416") (name "unconnected-(U401-PD#-Pad16)") (class "Default")
      (node (ref "U401") (pin "16") (pinfunction "PD#_16") (pintype "unspecified+no_connect"))
    )
  )
)
